# BeagleBone_Blue.net
KiCad netlist of a schematic drawn in EAGLE
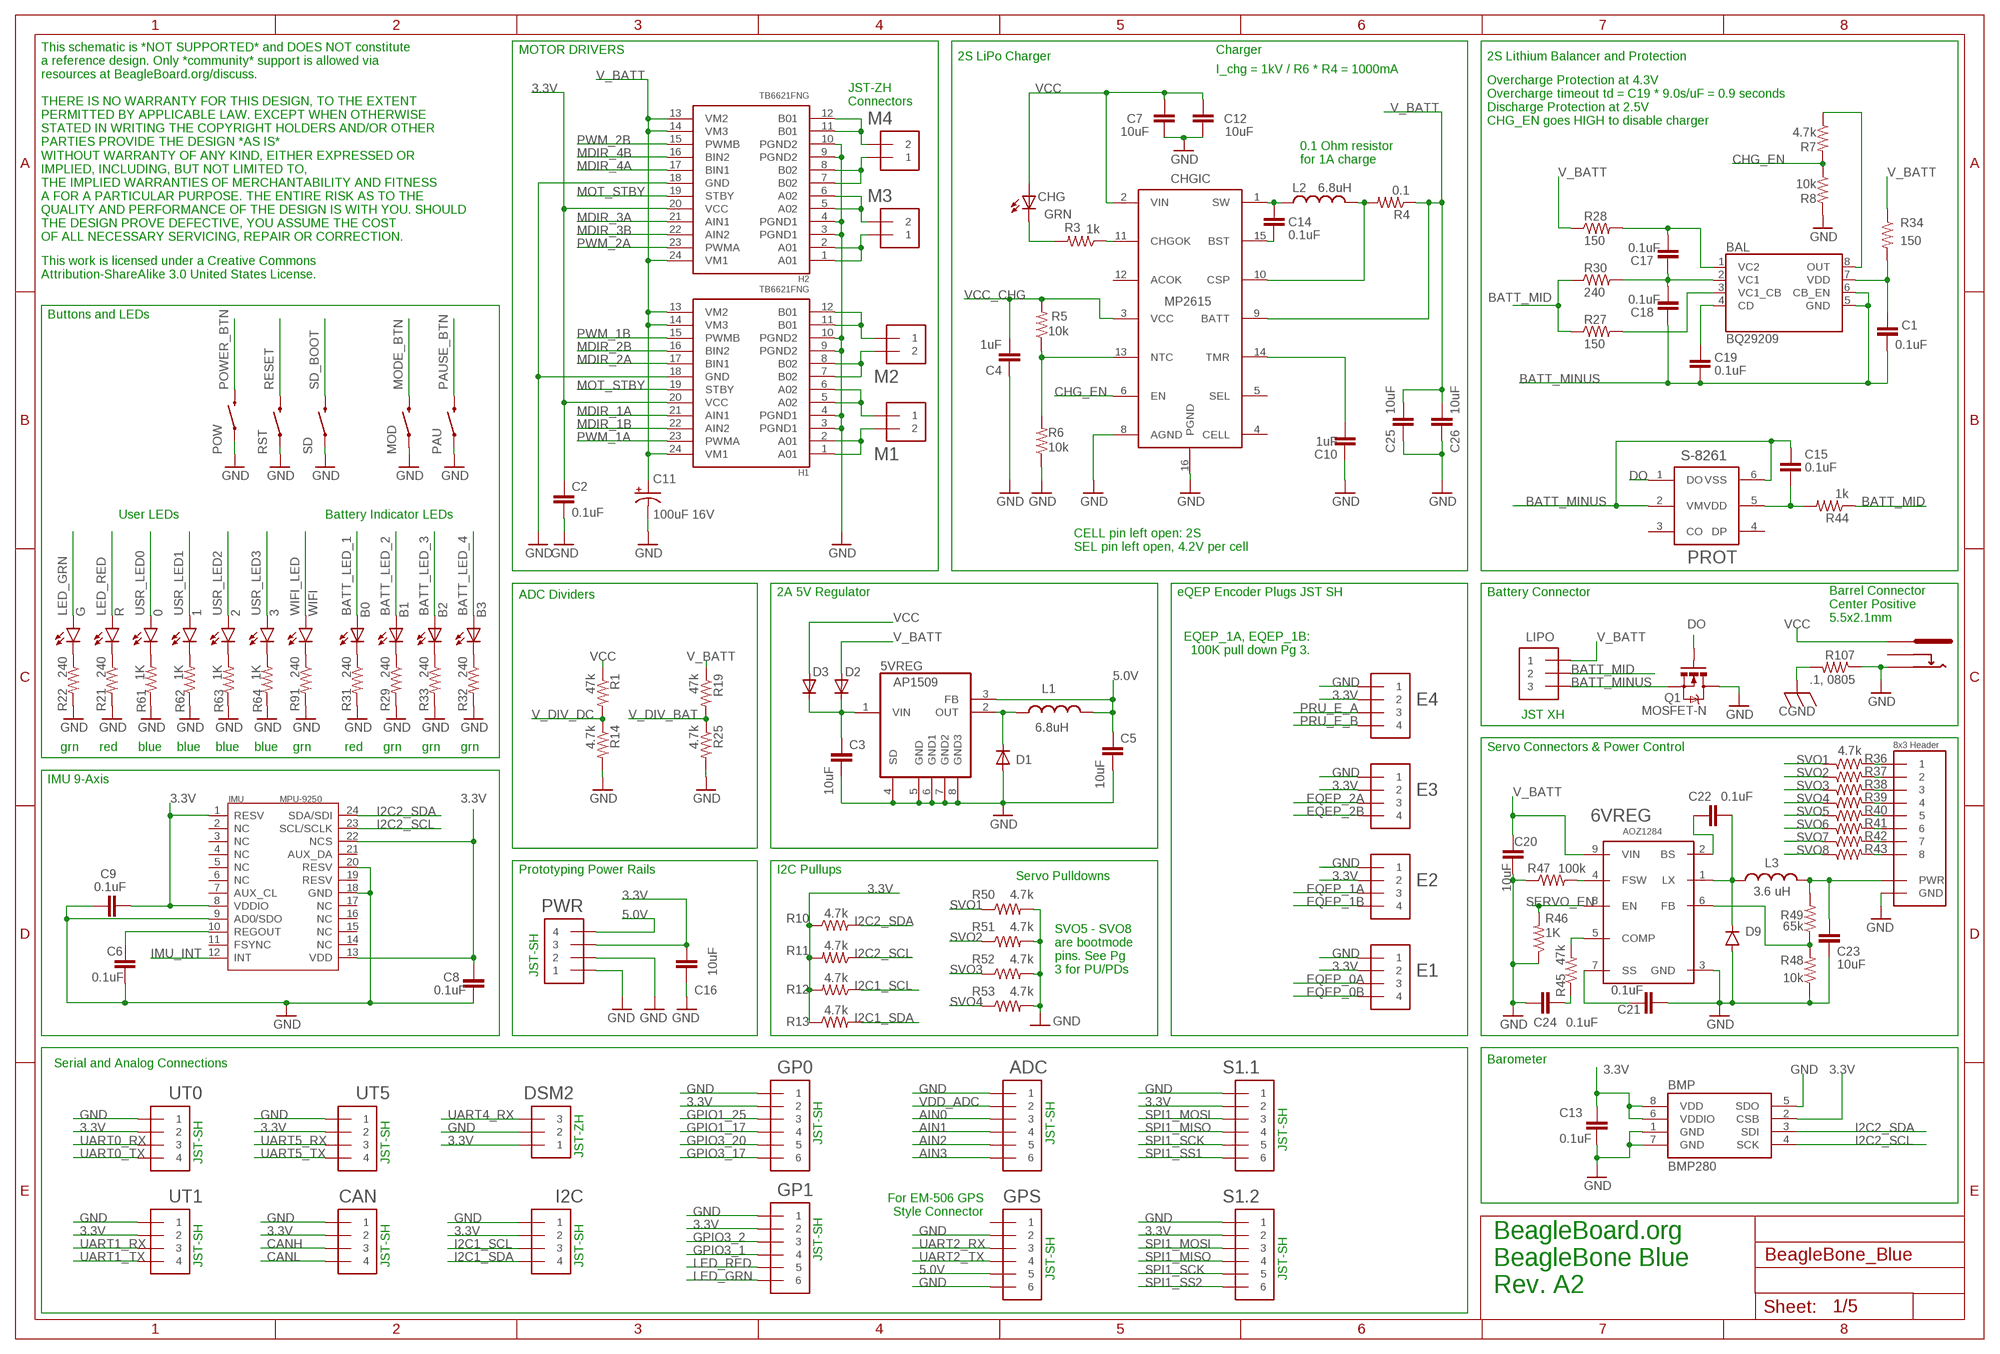
[diagram p0: schematic, sheet 1]
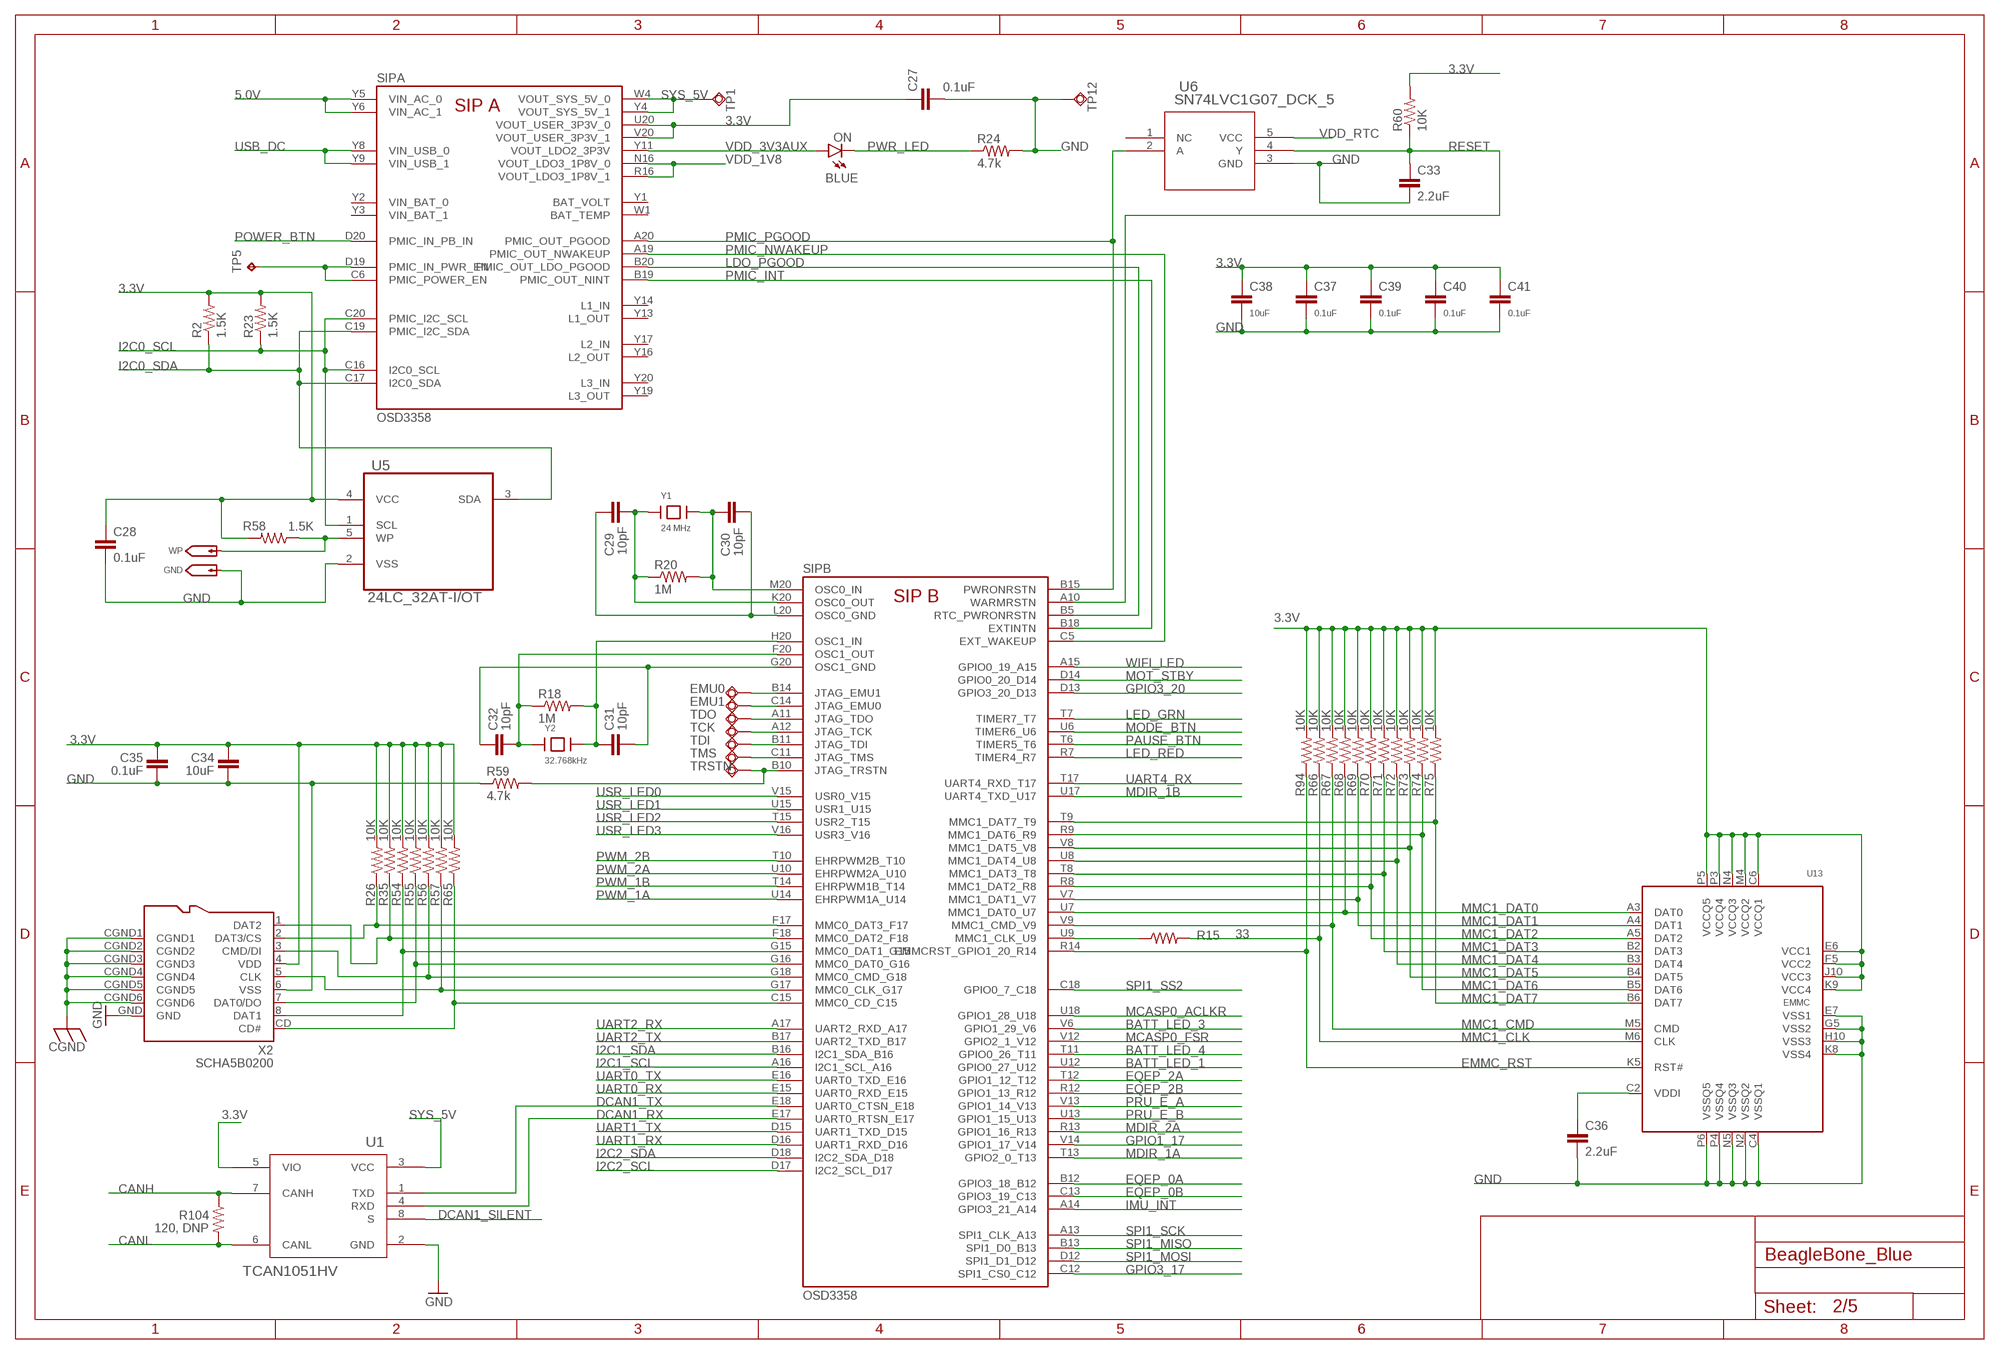
[diagram p1: schematic, sheet 2]
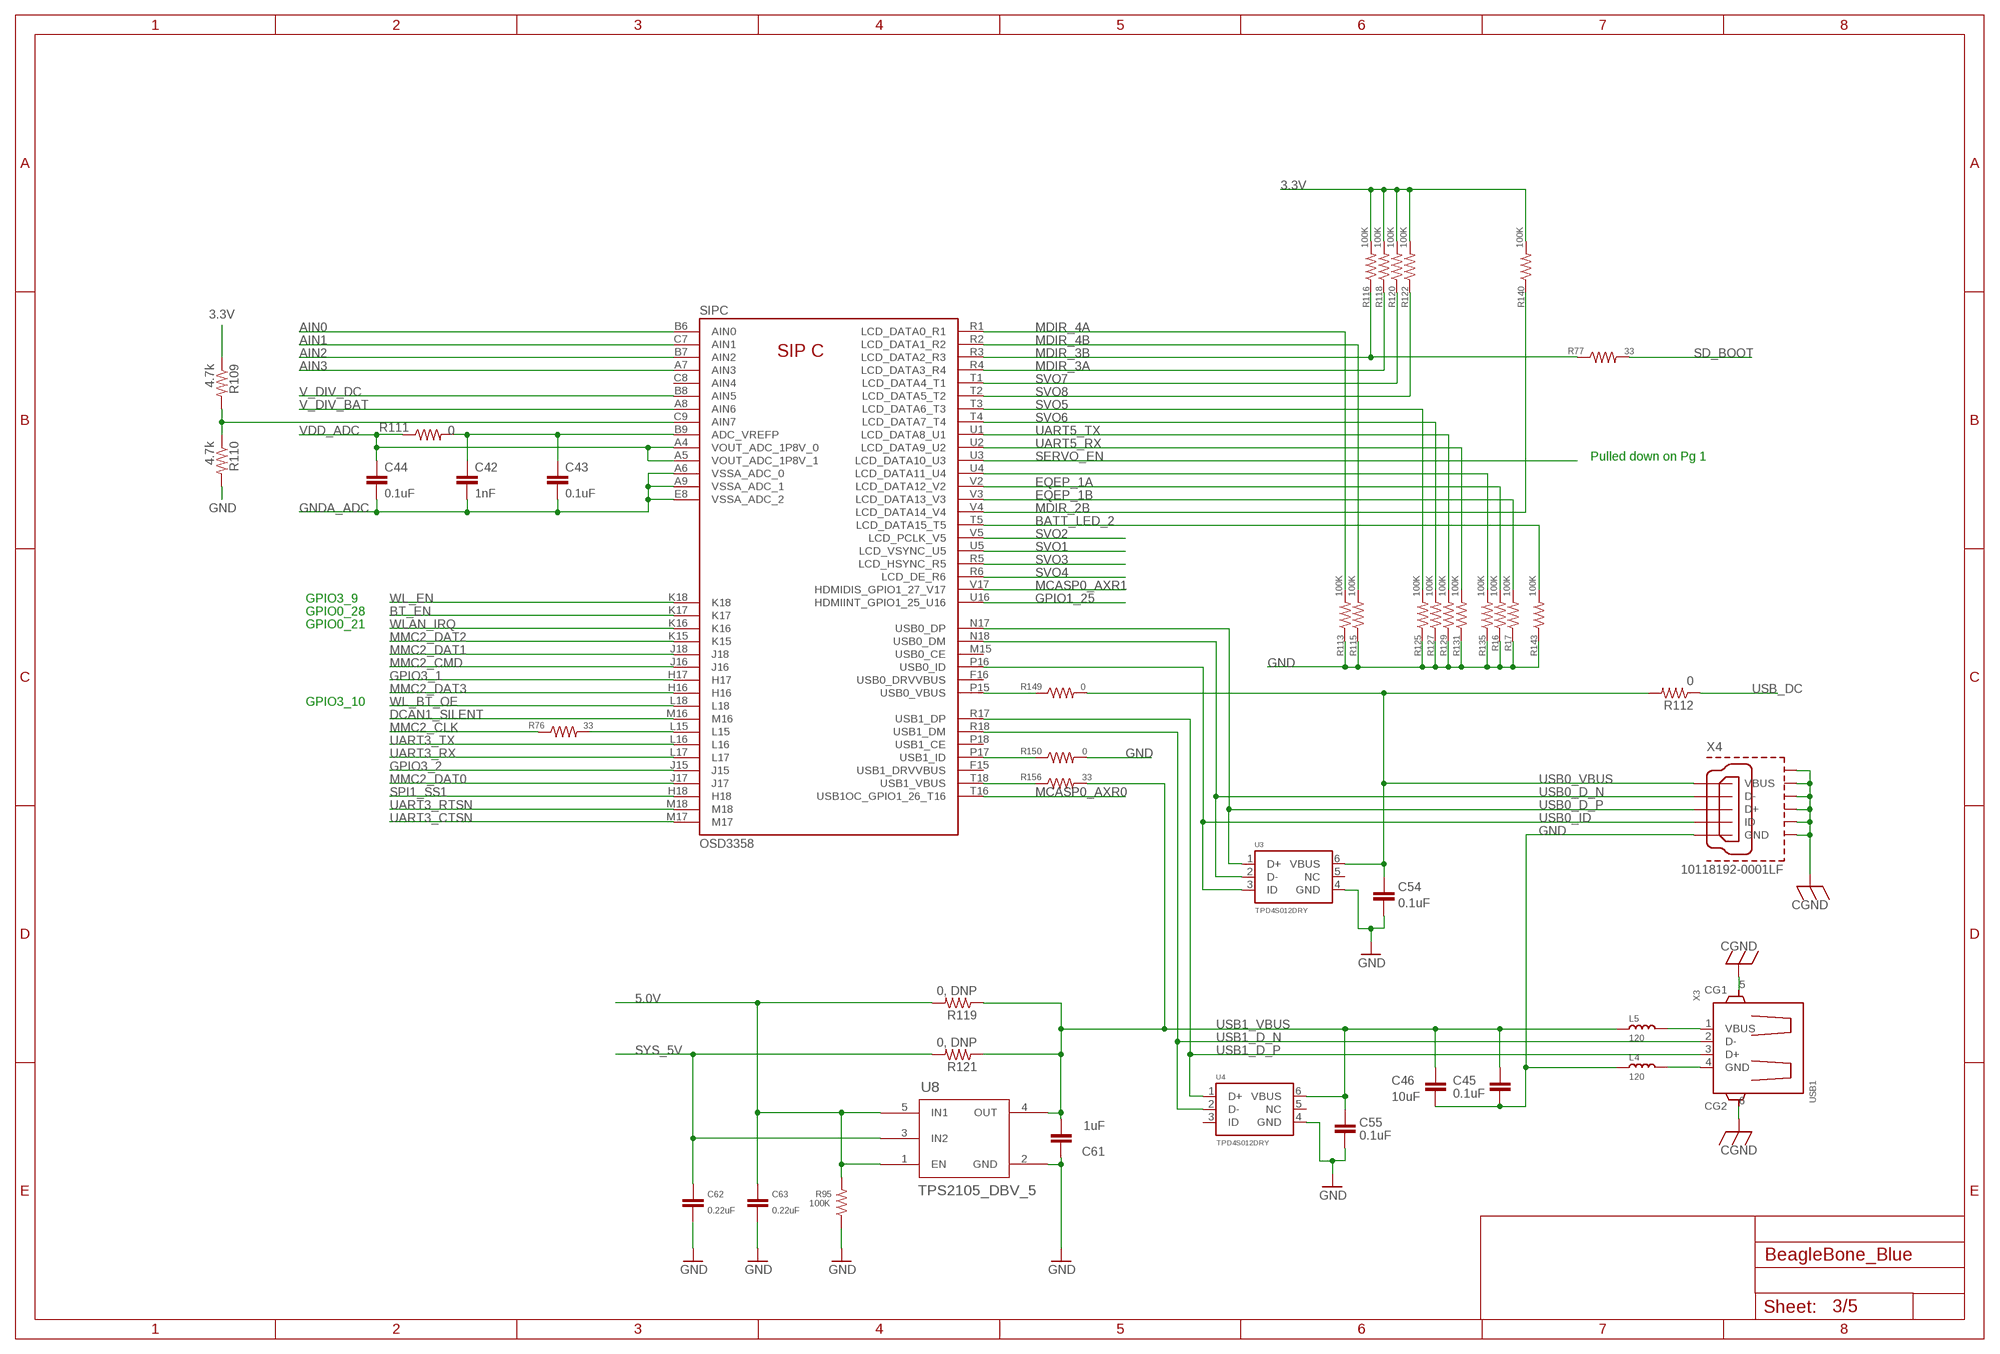
[diagram p2: schematic, sheet 3]
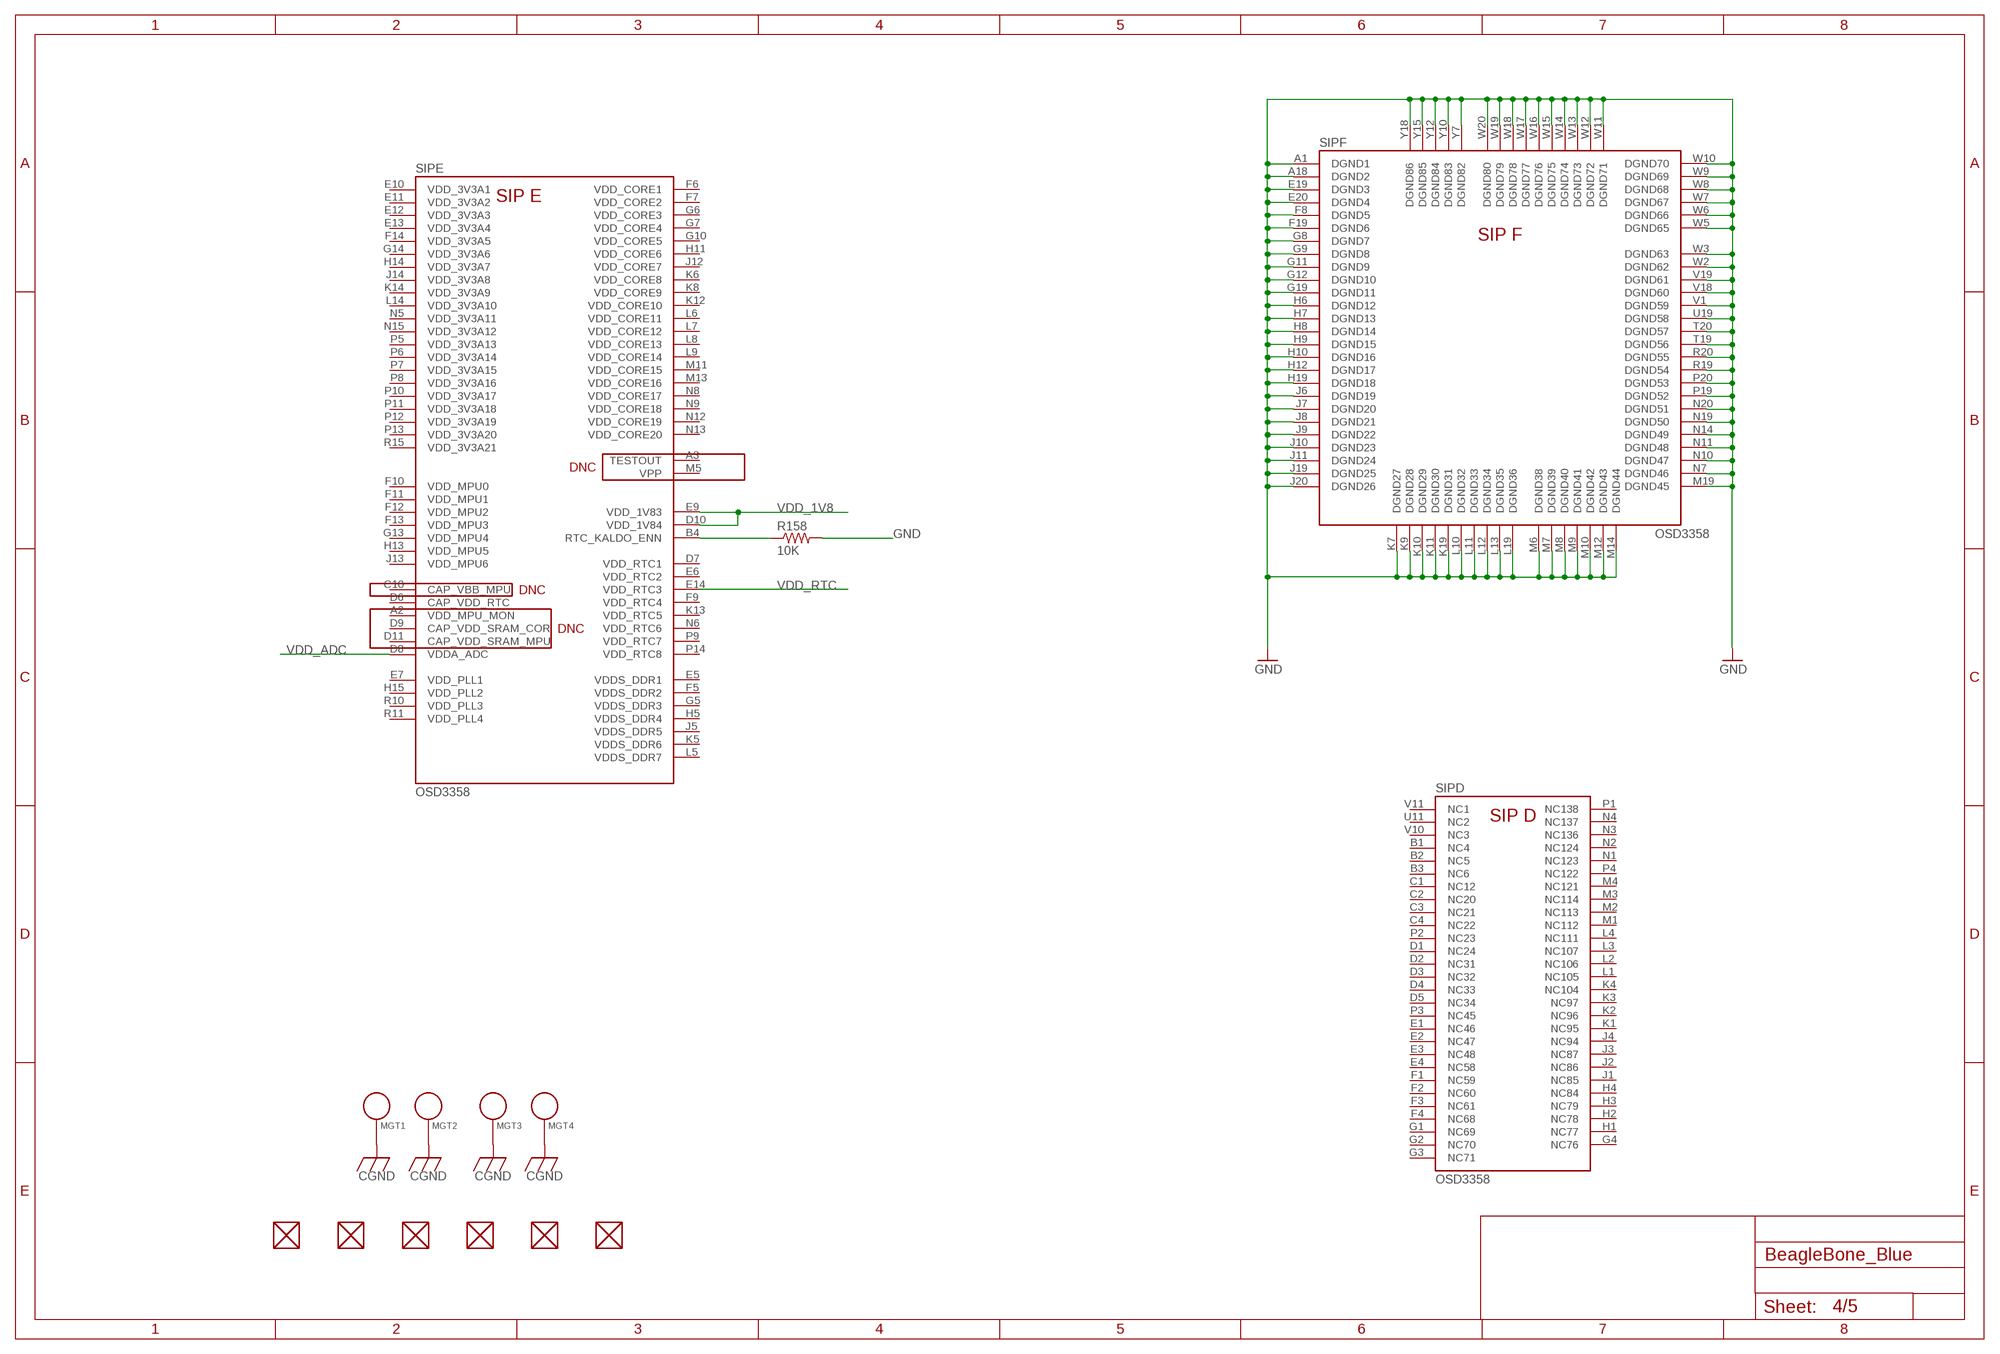
[diagram p3: schematic, sheet 4]
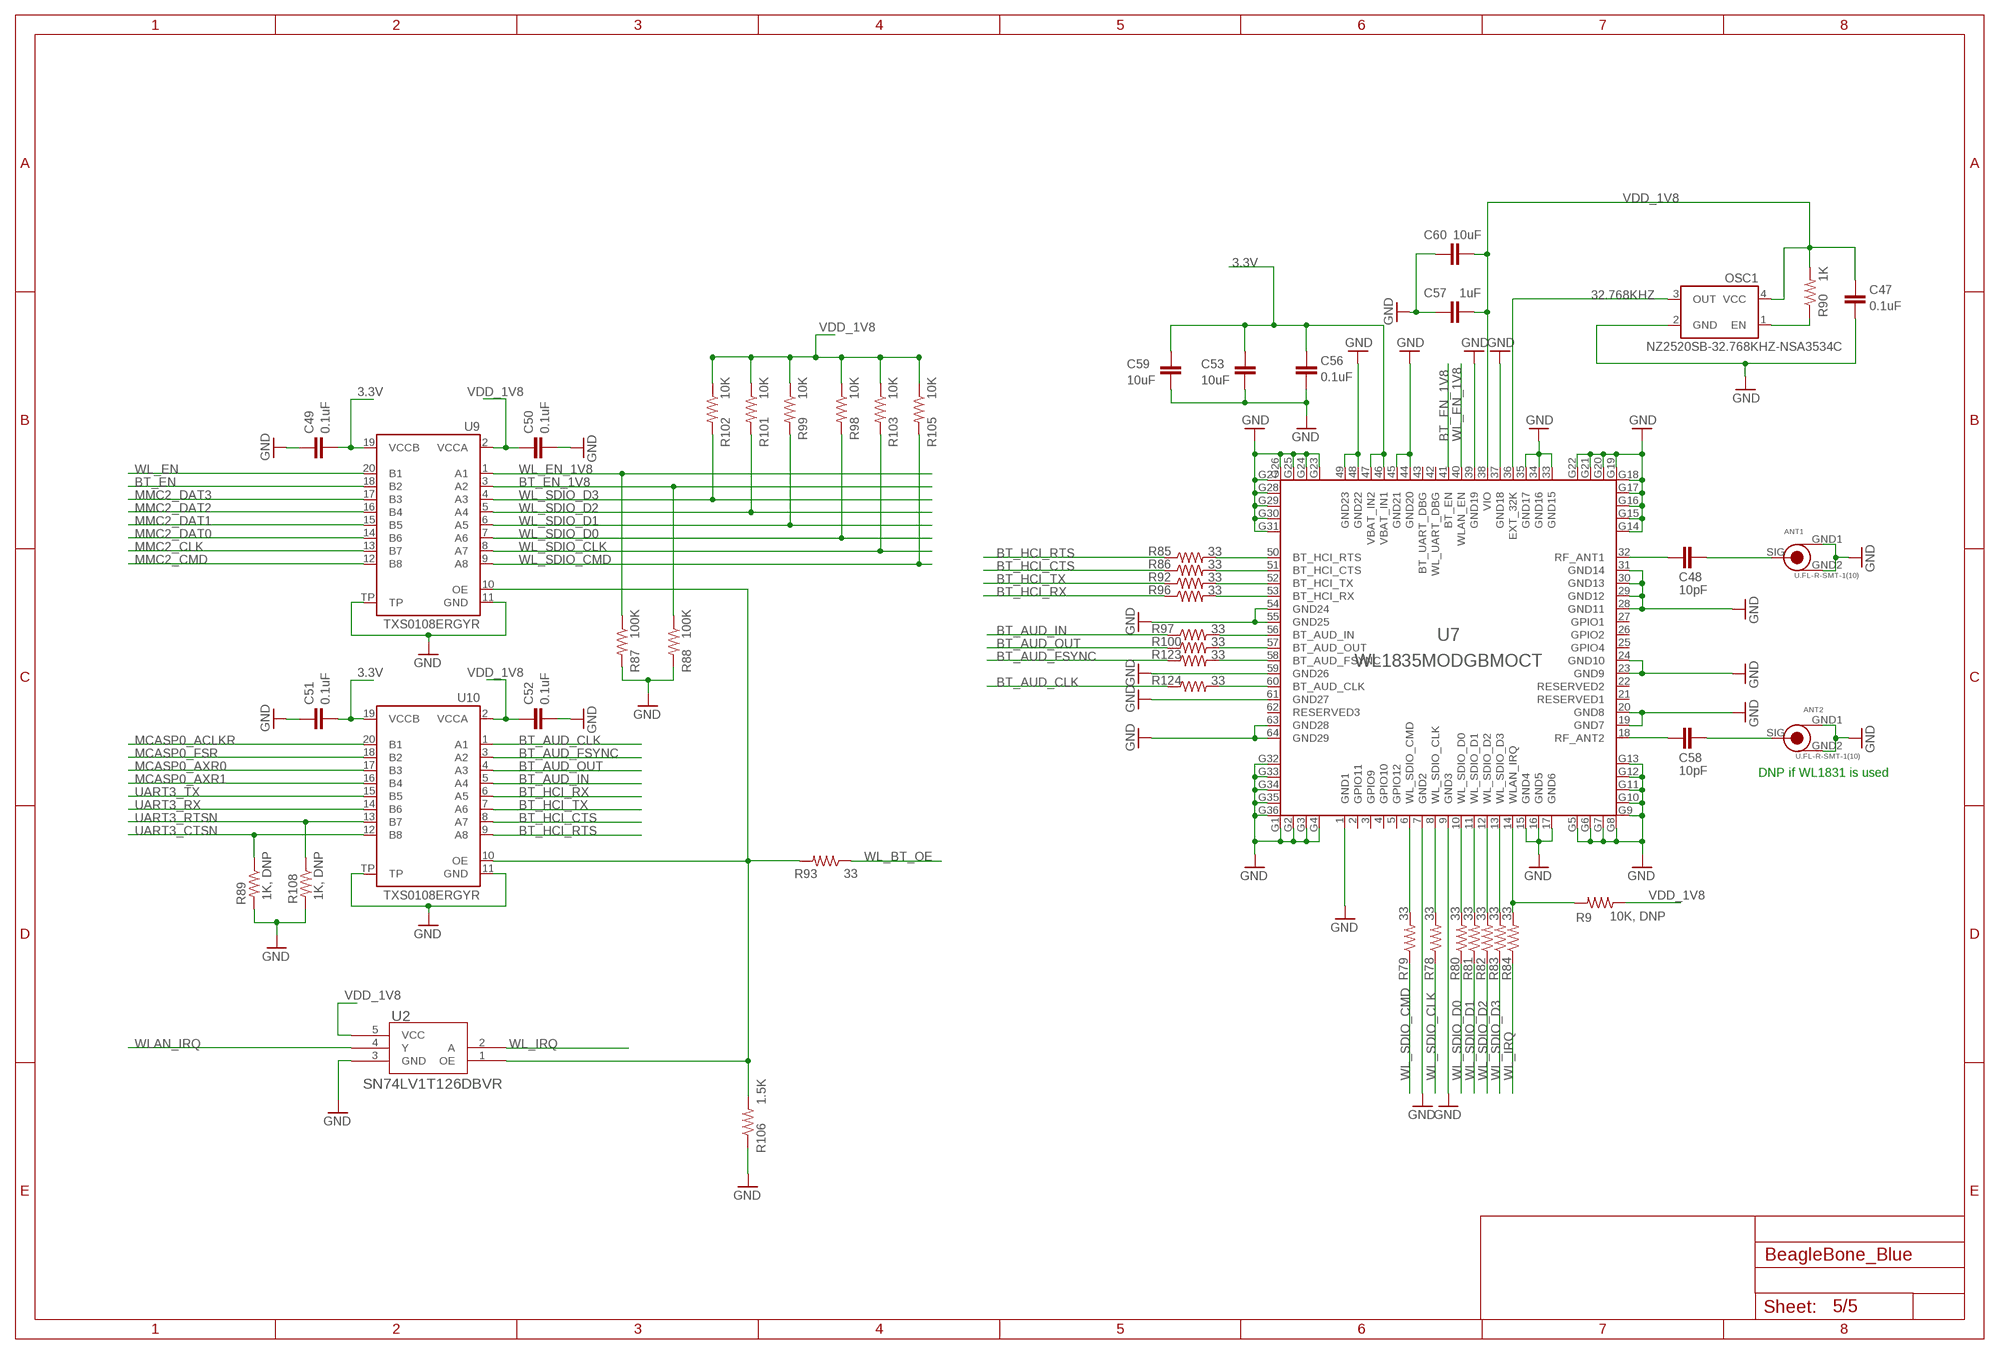
[diagram p4: schematic, sheet 5]

(export (version "E")
  (design (tool "Eeschema 10.0.6"))
  (components
    (comp (ref "0")
      (value "BLUE")
      (footprint "eagle-import:BEAGLEBONE_BLUE_LED-0603")
      (libsource (lib "eagle-import") (part "LED0603"))
    )
    (comp (ref "1")
      (value "BLUE")
      (footprint "eagle-import:BEAGLEBONE_BLUE_LED-0603")
      (libsource (lib "eagle-import") (part "LED0603"))
    )
    (comp (ref "2")
      (value "BLUE")
      (footprint "eagle-import:BEAGLEBONE_BLUE_LED-0603")
      (libsource (lib "eagle-import") (part "LED0603"))
    )
    (comp (ref "3")
      (value "BLUE")
      (footprint "eagle-import:BEAGLEBONE_BLUE_LED-0603")
      (libsource (lib "eagle-import") (part "LED0603"))
    )
    (comp (ref "5VREG")
      (value "AP1509SOIC-8-TIGHT")
      (footprint "eagle-import:BEAGLEBONE_BLUE_SO08-TIGHT")
      (libsource (lib "eagle-import") (part "AP1509SOIC-8-TIGHT"))
    )
    (comp (ref "6VREG")
      (value "AOZ1284")
      (footprint "eagle-import:SO08-EXPOSED")
      (libsource (lib "eagle-import") (part "AOZ1284"))
    )
    (comp (ref "12V")
      (value "PJ-102B_POWER_CON")
      (footprint "eagle-import:PJ-102B_POWER_CON")
      (libsource (lib "eagle-import") (part "PJ-102B_POWER_CON"))
    )
    (comp (ref "ADC")
      (value "JST_SH_6")
      (footprint "eagle-import:JST_SH_6")
      (libsource (lib "eagle-import") (part "JST_SH_6"))
    )
    (comp (ref "B0")
      (value "RED")
      (footprint "eagle-import:LED-0603")
      (libsource (lib "eagle-import") (part "SparkFun-LED_LED0603"))
    )
    (comp (ref "B1")
      (value "GREEN")
      (footprint "eagle-import:LED-0603")
      (libsource (lib "eagle-import") (part "SparkFun-LED_LED0603"))
    )
    (comp (ref "B2")
      (value "GREEN")
      (footprint "eagle-import:LED-0603")
      (libsource (lib "eagle-import") (part "SparkFun-LED_LED0603"))
    )
    (comp (ref "B3")
      (value "GREEN")
      (footprint "eagle-import:LED-0603")
      (libsource (lib "eagle-import") (part "SparkFun-LED_LED0603"))
    )
    (comp (ref "BAL")
      (value "BQ29209")
      (footprint "eagle-import:8-SON_3X3MM")
      (libsource (lib "eagle-import") (part "BQ29209"))
    )
    (comp (ref "BMP")
      (value "BMP280")
      (footprint "eagle-import:BMP280")
      (libsource (lib "eagle-import") (part "BMP280"))
    )
    (comp (ref "C1")
      (value "0.1uF")
      (footprint "eagle-import:0402-CAP")
      (libsource (lib "eagle-import") (part "Strawson_Eagle_Lib_CAP0402-CAP"))
    )
    (comp (ref "C2")
      (value "0.1uF")
      (footprint "eagle-import:0402-CAP")
      (libsource (lib "eagle-import") (part "Strawson_Eagle_Lib_CAP0402-CAP"))
    )
    (comp (ref "C3")
      (value "10uF")
      (footprint "eagle-import:0805")
      (libsource (lib "eagle-import") (part "CAP0805"))
    )
    (comp (ref "C4")
      (value "1uF")
      (footprint "eagle-import:0402-CAP")
      (libsource (lib "eagle-import") (part "Strawson_Eagle_Lib_CAP0402-CAP"))
    )
    (comp (ref "C5")
      (value "10uF")
      (footprint "eagle-import:0805")
      (libsource (lib "eagle-import") (part "CAP0805"))
    )
    (comp (ref "C6")
      (value "0.1uF")
      (footprint "eagle-import:0402-CAP")
      (libsource (lib "eagle-import") (part "Strawson_Eagle_Lib_CAP0402-CAP"))
    )
    (comp (ref "C7")
      (value "10uF")
      (footprint "eagle-import:0805")
      (libsource (lib "eagle-import") (part "CAP0805"))
    )
    (comp (ref "C8")
      (value "0.1uF")
      (footprint "eagle-import:0402-CAP")
      (libsource (lib "eagle-import") (part "Strawson_Eagle_Lib_CAP0402-CAP"))
    )
    (comp (ref "C9")
      (value "0.1uF")
      (footprint "eagle-import:0402-CAP")
      (libsource (lib "eagle-import") (part "Strawson_Eagle_Lib_CAP0402-CAP"))
    )
    (comp (ref "C10")
      (value "1uF")
      (footprint "eagle-import:0402-CAP")
      (libsource (lib "eagle-import") (part "Strawson_Eagle_Lib_CAP0402-CAP"))
    )
    (comp (ref "C11")
      (value "100uF 16V")
      (footprint "eagle-import:PANASONIC_D")
      (libsource (lib "eagle-import") (part "CPOL-USD"))
    )
    (comp (ref "C12")
      (value "10uF")
      (footprint "eagle-import:0805")
      (libsource (lib "eagle-import") (part "CAP0805"))
    )
    (comp (ref "C13")
      (value "0.1uF")
      (footprint "eagle-import:0402-CAP")
      (libsource (lib "eagle-import") (part "Strawson_Eagle_Lib_CAP0402-CAP"))
    )
    (comp (ref "C14")
      (value "0.1uF")
      (footprint "eagle-import:0402-CAP")
      (libsource (lib "eagle-import") (part "Strawson_Eagle_Lib_CAP0402-CAP"))
    )
    (comp (ref "C15")
      (value "0.1uF")
      (footprint "eagle-import:0402-CAP")
      (libsource (lib "eagle-import") (part "Strawson_Eagle_Lib_CAP0402-CAP"))
    )
    (comp (ref "C16")
      (value "10uF")
      (footprint "eagle-import:0805")
      (libsource (lib "eagle-import") (part "CAP0805"))
    )
    (comp (ref "C17")
      (value "0.1uF")
      (footprint "eagle-import:0402-CAP")
      (libsource (lib "eagle-import") (part "Strawson_Eagle_Lib_CAP0402-CAP"))
    )
    (comp (ref "C18")
      (value "0.1uF")
      (footprint "eagle-import:0402-CAP")
      (libsource (lib "eagle-import") (part "Strawson_Eagle_Lib_CAP0402-CAP"))
    )
    (comp (ref "C19")
      (value "0.1uF")
      (footprint "eagle-import:0402-CAP")
      (libsource (lib "eagle-import") (part "Strawson_Eagle_Lib_CAP0402-CAP"))
    )
    (comp (ref "C20")
      (value "10uF")
      (footprint "eagle-import:0805")
      (libsource (lib "eagle-import") (part "CAP0805"))
    )
    (comp (ref "C21")
      (value "0.1uF")
      (footprint "eagle-import:0402-CAP")
      (libsource (lib "eagle-import") (part "Strawson_Eagle_Lib_CAP0402-CAP"))
    )
    (comp (ref "C22")
      (value "0.1uF")
      (footprint "eagle-import:0402-CAP")
      (libsource (lib "eagle-import") (part "Strawson_Eagle_Lib_CAP0402-CAP"))
    )
    (comp (ref "C23")
      (value "10uF")
      (footprint "eagle-import:0805")
      (libsource (lib "eagle-import") (part "CAP0805"))
    )
    (comp (ref "C24")
      (value "0.1uF")
      (footprint "eagle-import:0402-CAP")
      (libsource (lib "eagle-import") (part "Strawson_Eagle_Lib_CAP0402-CAP"))
    )
    (comp (ref "C25")
      (value "10uF")
      (footprint "eagle-import:0805")
      (libsource (lib "eagle-import") (part "CAP0805"))
    )
    (comp (ref "C26")
      (value "10uF")
      (footprint "eagle-import:0805")
      (libsource (lib "eagle-import") (part "CAP0805"))
    )
    (comp (ref "CAN")
      (value "JST_SH_4")
      (footprint "eagle-import:JST_SH_4_SMD")
      (libsource (lib "eagle-import") (part "JST_SH_4"))
    )
    (comp (ref "CHG")
      (value "GRN")
      (footprint "eagle-import:LED-0603")
      (libsource (lib "eagle-import") (part "SparkFun-LED_LED0603"))
    )
    (comp (ref "CHGIC")
      (value "MP2615")
      (footprint "eagle-import:MP2615")
      (libsource (lib "eagle-import") (part "MP2615"))
    )
    (comp (ref "D1")
      (value "DIODE_SOD-123FL")
      (footprint "eagle-import:ADAFRUIT_SOD-123FL")
      (libsource (lib "eagle-import") (part "DIODE_SOD-123FL"))
    )
    (comp (ref "D2")
      (value "DIODE_SOD-123FL")
      (footprint "eagle-import:ADAFRUIT_SOD-123FL")
      (libsource (lib "eagle-import") (part "DIODE_SOD-123FL"))
    )
    (comp (ref "D3")
      (value "DIODE_SOD-123FL")
      (footprint "eagle-import:ADAFRUIT_SOD-123FL")
      (libsource (lib "eagle-import") (part "DIODE_SOD-123FL"))
    )
    (comp (ref "D9")
      (value "DIODEDO214AA")
      (footprint "eagle-import:DO-214AA")
      (libsource (lib "eagle-import") (part "DIODEDO214AA"))
    )
    (comp (ref "DSM2")
      (value "JST_ZH_3")
      (footprint "eagle-import:JST_ZH_3")
      (libsource (lib "eagle-import") (part "JST_ZH_3"))
    )
    (comp (ref "E1")
      (value "JST_SH_4")
      (footprint "eagle-import:JST_SH_4_SMD")
      (libsource (lib "eagle-import") (part "JST_SH_4"))
    )
    (comp (ref "E2")
      (value "JST_SH_4")
      (footprint "eagle-import:JST_SH_4_SMD")
      (libsource (lib "eagle-import") (part "JST_SH_4"))
    )
    (comp (ref "E3")
      (value "JST_SH_4")
      (footprint "eagle-import:JST_SH_4_SMD")
      (libsource (lib "eagle-import") (part "JST_SH_4"))
    )
    (comp (ref "E4")
      (value "JST_SH_4")
      (footprint "eagle-import:JST_SH_4_SMD")
      (libsource (lib "eagle-import") (part "JST_SH_4"))
    )
    (comp (ref "G")
      (value "GREEN")
      (footprint "eagle-import:BEAGLEBONE_BLUE_LED-0603")
      (libsource (lib "eagle-import") (part "LED0603"))
    )
    (comp (ref "GP0")
      (value "JST_SH_6")
      (footprint "eagle-import:JST_SH_6")
      (libsource (lib "eagle-import") (part "JST_SH_6"))
    )
    (comp (ref "GP1")
      (value "JST_SH_6")
      (footprint "eagle-import:JST_SH_6")
      (libsource (lib "eagle-import") (part "JST_SH_6"))
    )
    (comp (ref "GPS")
      (value "JST_SH_6")
      (footprint "eagle-import:JST_SH_6")
      (libsource (lib "eagle-import") (part "JST_SH_6"))
    )
    (comp (ref "H1")
      (value "TB6621FNG")
      (footprint "eagle-import:SSOP24")
      (libsource (lib "eagle-import") (part "TB6621FNG"))
    )
    (comp (ref "H2")
      (value "TB6621FNG")
      (footprint "eagle-import:SSOP24")
      (libsource (lib "eagle-import") (part "TB6621FNG"))
    )
    (comp (ref "I2C")
      (value "JST_SH_4")
      (footprint "eagle-import:JST_SH_4_SMD")
      (libsource (lib "eagle-import") (part "JST_SH_4"))
    )
    (comp (ref "IMU")
      (value "MPU-9250")
      (footprint "eagle-import:QFN24G-0.4-3X3MM")
      (libsource (lib "eagle-import") (part "MPU-9250"))
    )
    (comp (ref "J2")
      (value "STRAWSON_EAGLE_LIB_SERVO_HEADERS_8X")
      (footprint "eagle-import:STRAWSON_EAGLE_LIB_3X8_0.1__HEADER")
      (libsource (lib "eagle-import") (part "STRAWSON_EAGLE_LIB_SERVO_HEADERS_8X"))
    )
    (comp (ref "L1")
      (value "6.8uH")
      (footprint "eagle-import:SRN6045")
      (libsource (lib "eagle-import") (part "INDUCTORBOURNS_SRN6045"))
    )
    (comp (ref "L2")
      (value "6.8uH")
      (footprint "eagle-import:SRN6045")
      (libsource (lib "eagle-import") (part "INDUCTORBOURNS_SRN6045"))
    )
    (comp (ref "L3")
      (value "3.6 uH")
      (footprint "eagle-import:8X8MM_INDUCTOR")
      (libsource (lib "eagle-import") (part "INDUCTOR"))
    )
    (comp (ref "LIPO")
      (value "BATTERY")
      (footprint "eagle-import:JST_XH_3-PIN")
      (libsource (lib "eagle-import") (part "JST_XH_3-PIN"))
    )
    (comp (ref "M1")
      (value "JST_ZH_2")
      (footprint "eagle-import:JST_ZH_2")
      (libsource (lib "eagle-import") (part "JST_ZH_2"))
    )
    (comp (ref "M2")
      (value "JST_ZH_2")
      (footprint "eagle-import:JST_ZH_2")
      (libsource (lib "eagle-import") (part "JST_ZH_2"))
    )
    (comp (ref "M3")
      (value "JST_ZH_2")
      (footprint "eagle-import:JST_ZH_2")
      (libsource (lib "eagle-import") (part "JST_ZH_2"))
    )
    (comp (ref "M4")
      (value "JST_ZH_2")
      (footprint "eagle-import:JST_ZH_2")
      (libsource (lib "eagle-import") (part "JST_ZH_2"))
    )
    (comp (ref "MOD")
      (value "SWITCH-MOMENTARY-2SMD-1101NE")
      (footprint "eagle-import:TACTILE-SWITCH-1101NE")
      (libsource (lib "eagle-import") (part "SWITCH-MOMENTARY-2SMD-1101NE"))
    )
    (comp (ref "PAU")
      (value "SWITCH-MOMENTARY-2SMD-1101NE")
      (footprint "eagle-import:TACTILE-SWITCH-1101NE")
      (libsource (lib "eagle-import") (part "SWITCH-MOMENTARY-2SMD-1101NE"))
    )
    (comp (ref "POW")
      (value "SWITCH-MOMENTARY-2SMD-1101NE")
      (footprint "eagle-import:TACTILE-SWITCH-1101NE")
      (libsource (lib "eagle-import") (part "SWITCH-MOMENTARY-2SMD-1101NE"))
    )
    (comp (ref "PROT")
      (value "S-8261")
      (footprint "eagle-import:SOT-236")
      (libsource (lib "eagle-import") (part "S-8261"))
    )
    (comp (ref "PWR")
      (value "JST_SH_4")
      (footprint "eagle-import:JST_SH_4_SMD")
      (libsource (lib "eagle-import") (part "JST_SH_4"))
    )
    (comp (ref "Q1")
      (value "MOSFET-N")
      (footprint "eagle-import:SO08-TIGHT")
      (libsource (lib "eagle-import") (part "MOSFET-NCHANNEL"))
    )
    (comp (ref "R")
      (value "RED")
      (footprint "eagle-import:BEAGLEBONE_BLUE_LED-0603")
      (libsource (lib "eagle-import") (part "LED0603"))
    )
    (comp (ref "R1")
      (value "47k")
      (footprint "eagle-import:0402-RES")
      (libsource (lib "eagle-import") (part "RESISTOR0402-RES"))
    )
    (comp (ref "R3")
      (value "1k")
      (footprint "eagle-import:0402-RES")
      (libsource (lib "eagle-import") (part "RESISTOR0402-RES"))
    )
    (comp (ref "R4")
      (value "0.1")
      (footprint "eagle-import:0603-RES")
      (libsource (lib "eagle-import") (part "RESISTOR0603"))
    )
    (comp (ref "R5")
      (value "10k")
      (footprint "eagle-import:0402-RES")
      (libsource (lib "eagle-import") (part "RESISTOR0402-RES"))
    )
    (comp (ref "R6")
      (value "10k")
      (footprint "eagle-import:0402-RES")
      (libsource (lib "eagle-import") (part "RESISTOR0402-RES"))
    )
    (comp (ref "R7")
      (value "4.7k")
      (footprint "eagle-import:0402-RES")
      (libsource (lib "eagle-import") (part "RESISTOR0402-RES"))
    )
    (comp (ref "R8")
      (value "10k")
      (footprint "eagle-import:0402-RES")
      (libsource (lib "eagle-import") (part "RESISTOR0402-RES"))
    )
    (comp (ref "R10")
      (value "4.7k")
      (footprint "eagle-import:0402-RES")
      (libsource (lib "eagle-import") (part "RESISTOR0402-RES"))
    )
    (comp (ref "R11")
      (value "4.7k")
      (footprint "eagle-import:0402-RES")
      (libsource (lib "eagle-import") (part "RESISTOR0402-RES"))
    )
    (comp (ref "R12")
      (value "4.7k")
      (footprint "eagle-import:0402-RES")
      (libsource (lib "eagle-import") (part "RESISTOR0402-RES"))
    )
    (comp (ref "R13")
      (value "4.7k")
      (footprint "eagle-import:0402-RES")
      (libsource (lib "eagle-import") (part "RESISTOR0402-RES"))
    )
    (comp (ref "R14")
      (value "4.7k")
      (footprint "eagle-import:0402-RES")
      (libsource (lib "eagle-import") (part "RESISTOR0402-RES"))
    )
    (comp (ref "R19")
      (value "47k")
      (footprint "eagle-import:0402-RES")
      (libsource (lib "eagle-import") (part "RESISTOR0402-RES"))
    )
    (comp (ref "R21")
      (value "240")
      (footprint "eagle-import:0402-RES")
      (libsource (lib "eagle-import") (part "RESISTOR0402-RES"))
    )
    (comp (ref "R22")
      (value "240")
      (footprint "eagle-import:0402-RES")
      (libsource (lib "eagle-import") (part "RESISTOR0402-RES"))
    )
    (comp (ref "R25")
      (value "4.7k")
      (footprint "eagle-import:0402-RES")
      (libsource (lib "eagle-import") (part "RESISTOR0402-RES"))
    )
    (comp (ref "R27")
      (value "150")
      (footprint "eagle-import:0402-RES")
      (libsource (lib "eagle-import") (part "RESISTOR0402-RES"))
    )
    (comp (ref "R28")
      (value "150")
      (footprint "eagle-import:0402-RES")
      (libsource (lib "eagle-import") (part "RESISTOR0402-RES"))
    )
    (comp (ref "R29")
      (value "240")
      (footprint "eagle-import:0402-RES")
      (libsource (lib "eagle-import") (part "RESISTOR0402-RES"))
    )
    (comp (ref "R30")
      (value "240")
      (footprint "eagle-import:0402-RES")
      (libsource (lib "eagle-import") (part "RESISTOR0402-RES"))
    )
    (comp (ref "R31")
      (value "240")
      (footprint "eagle-import:0402-RES")
      (libsource (lib "eagle-import") (part "RESISTOR0402-RES"))
    )
    (comp (ref "R32")
      (value "240")
      (footprint "eagle-import:0402-RES")
      (libsource (lib "eagle-import") (part "RESISTOR0402-RES"))
    )
    (comp (ref "R33")
      (value "240")
      (footprint "eagle-import:0402-RES")
      (libsource (lib "eagle-import") (part "RESISTOR0402-RES"))
    )
    (comp (ref "R34")
      (value "150")
      (footprint "eagle-import:0402-RES")
      (libsource (lib "eagle-import") (part "RESISTOR0402-RES"))
    )
    (comp (ref "R36")
      (value "4.7k")
      (footprint "eagle-import:0402-RES")
      (libsource (lib "eagle-import") (part "RESISTOR0402-RES"))
    )
    (comp (ref "R37")
      (value "4.7k")
      (footprint "eagle-import:0402-RES")
      (libsource (lib "eagle-import") (part "RESISTOR0402-RES"))
    )
    (comp (ref "R38")
      (value "4.7k")
      (footprint "eagle-import:0402-RES")
      (libsource (lib "eagle-import") (part "RESISTOR0402-RES"))
    )
    (comp (ref "R39")
      (value "4.7k")
      (footprint "eagle-import:0402-RES")
      (libsource (lib "eagle-import") (part "RESISTOR0402-RES"))
    )
    (comp (ref "R40")
      (value "4.7k")
      (footprint "eagle-import:0402-RES")
      (libsource (lib "eagle-import") (part "RESISTOR0402-RES"))
    )
    (comp (ref "R41")
      (value "4.7k")
      (footprint "eagle-import:0402-RES")
      (libsource (lib "eagle-import") (part "RESISTOR0402-RES"))
    )
    (comp (ref "R42")
      (value "4.7k")
      (footprint "eagle-import:0402-RES")
      (libsource (lib "eagle-import") (part "RESISTOR0402-RES"))
    )
    (comp (ref "R43")
      (value "4.7k")
      (footprint "eagle-import:0402-RES")
      (libsource (lib "eagle-import") (part "RESISTOR0402-RES"))
    )
    (comp (ref "R44")
      (value "1k")
      (footprint "eagle-import:0402-RES")
      (libsource (lib "eagle-import") (part "RESISTOR0402-RES"))
    )
    (comp (ref "R45")
      (value "47k")
      (footprint "eagle-import:0402-RES")
      (libsource (lib "eagle-import") (part "RESISTOR0402-RES"))
    )
    (comp (ref "R46")
      (value "1K")
      (footprint "eagle-import:0402-RES")
      (libsource (lib "eagle-import") (part "RESISTOR0402-RES"))
    )
    (comp (ref "R47")
      (value "100k")
      (footprint "eagle-import:0402-RES")
      (libsource (lib "eagle-import") (part "RESISTOR0402-RES"))
    )
    (comp (ref "R48")
      (value "10k")
      (footprint "eagle-import:0402-RES")
      (libsource (lib "eagle-import") (part "RESISTOR0402-RES"))
    )
    (comp (ref "R49")
      (value "65k")
      (footprint "eagle-import:0402-RES")
      (libsource (lib "eagle-import") (part "RESISTOR0402-RES"))
    )
    (comp (ref "R50")
      (value "4.7k")
      (footprint "eagle-import:0402-RES")
      (libsource (lib "eagle-import") (part "RESISTOR0402-RES"))
    )
    (comp (ref "R51")
      (value "4.7k")
      (footprint "eagle-import:0402-RES")
      (libsource (lib "eagle-import") (part "RESISTOR0402-RES"))
    )
    (comp (ref "R52")
      (value "4.7k")
      (footprint "eagle-import:0402-RES")
      (libsource (lib "eagle-import") (part "RESISTOR0402-RES"))
    )
    (comp (ref "R53")
      (value "4.7k")
      (footprint "eagle-import:0402-RES")
      (libsource (lib "eagle-import") (part "RESISTOR0402-RES"))
    )
    (comp (ref "R61")
      (value "1K")
      (footprint "eagle-import:0402-RES")
      (libsource (lib "eagle-import") (part "RESISTOR0402-RES"))
    )
    (comp (ref "R62")
      (value "1K")
      (footprint "eagle-import:0402-RES")
      (libsource (lib "eagle-import") (part "RESISTOR0402-RES"))
    )
    (comp (ref "R63")
      (value "1K")
      (footprint "eagle-import:0402-RES")
      (libsource (lib "eagle-import") (part "RESISTOR0402-RES"))
    )
    (comp (ref "R64")
      (value "1K")
      (footprint "eagle-import:0402-RES")
      (libsource (lib "eagle-import") (part "RESISTOR0402-RES"))
    )
    (comp (ref "R91")
      (value "240")
      (footprint "eagle-import:0402-RES")
      (libsource (lib "eagle-import") (part "RESISTOR0402-RES"))
    )
    (comp (ref "R107")
      (value ".1, 0805")
      (footprint "eagle-import:R0805")
      (libsource (lib "eagle-import") (part "R-US_R0805"))
    )
    (comp (ref "RST")
      (value "SWITCH-MOMENTARY-2SMD-1101NE")
      (footprint "eagle-import:TACTILE-SWITCH-1101NE")
      (libsource (lib "eagle-import") (part "SWITCH-MOMENTARY-2SMD-1101NE"))
    )
    (comp (ref "S1.1")
      (value "JST_SH_6")
      (footprint "eagle-import:JST_SH_6")
      (libsource (lib "eagle-import") (part "JST_SH_6"))
    )
    (comp (ref "S1.2")
      (value "JST_SH_6")
      (footprint "eagle-import:JST_SH_6")
      (libsource (lib "eagle-import") (part "JST_SH_6"))
    )
    (comp (ref "SD")
      (value "SWITCH-MOMENTARY-2SMD-1101NE")
      (footprint "eagle-import:TACTILE-SWITCH-1101NE")
      (libsource (lib "eagle-import") (part "SWITCH-MOMENTARY-2SMD-1101NE"))
    )
    (comp (ref "UT0")
      (value "JST_SH_4")
      (footprint "eagle-import:JST_SH_4_SMD")
      (libsource (lib "eagle-import") (part "JST_SH_4"))
    )
    (comp (ref "UT1")
      (value "JST_SH_4")
      (footprint "eagle-import:JST_SH_4_SMD")
      (libsource (lib "eagle-import") (part "JST_SH_4"))
    )
    (comp (ref "UT5")
      (value "JST_SH_4")
      (footprint "eagle-import:JST_SH_4_SMD")
      (libsource (lib "eagle-import") (part "JST_SH_4"))
    )
    (comp (ref "WIFI")
      (value "GREEN")
      (footprint "eagle-import:BEAGLEBONE_BLUE_LED-0603")
      (libsource (lib "eagle-import") (part "LED0603"))
    )
    (comp (ref "FUD1")
      (value "FIDUCIAL")
      (footprint "eagle-import:FIDUCIAL_40MIL")
      (libsource (lib "eagle-import") (part "FIDUCIAL"))
    )
    (comp (ref "FUD2")
      (value "FIDUCIAL")
      (footprint "eagle-import:FIDUCIAL_40MIL")
      (libsource (lib "eagle-import") (part "FIDUCIAL"))
    )
    (comp (ref "FUD3")
      (value "FIDUCIAL")
      (footprint "eagle-import:FIDUCIAL_40MIL")
      (libsource (lib "eagle-import") (part "FIDUCIAL"))
    )
    (comp (ref "FUD4")
      (value "FIDUCIAL")
      (footprint "eagle-import:FIDUCIAL_40MIL")
      (libsource (lib "eagle-import") (part "FIDUCIAL"))
    )
    (comp (ref "FUD5")
      (value "FIDUCIAL")
      (footprint "eagle-import:FIDUCIAL_40MIL")
      (libsource (lib "eagle-import") (part "FIDUCIAL"))
    )
    (comp (ref "FUD6")
      (value "FIDUCIAL")
      (footprint "eagle-import:FIDUCIAL_40MIL")
      (libsource (lib "eagle-import") (part "FIDUCIAL"))
    )
    (comp (ref "MGT1")
      (value "MOUNTING_HOLE")
      (footprint "eagle-import:MOUNTING_HOLE")
      (libsource (lib "eagle-import") (part "MOUNTING_HOLE"))
    )
    (comp (ref "MGT2")
      (value "MOUNTING_HOLE")
      (footprint "eagle-import:MOUNTING_HOLE")
      (libsource (lib "eagle-import") (part "MOUNTING_HOLE"))
    )
    (comp (ref "MGT3")
      (value "MOUNTING_HOLE")
      (footprint "eagle-import:MOUNTING_HOLE")
      (libsource (lib "eagle-import") (part "MOUNTING_HOLE"))
    )
    (comp (ref "MGT4")
      (value "MOUNTING_HOLE")
      (footprint "eagle-import:MOUNTING_HOLE")
      (libsource (lib "eagle-import") (part "MOUNTING_HOLE"))
    )
    (comp (ref "R158")
      (value "10K")
      (footprint "eagle-import:0402-RES")
      (libsource (lib "eagle-import") (part "RESISTOR0402-RES"))
    )
    (comp (ref "SIP")
      (value "OSD3358")
      (footprint "eagle-import:BEAGLEBONE_BLUE_OSD3358")
      (libsource (lib "eagle-import") (part "OSD3358"))
    )
    (comp (ref "C27")
      (value "0.1uF")
      (footprint "eagle-import:0402-CAP")
      (libsource (lib "eagle-import") (part "Strawson_Eagle_Lib_CAP0402-CAP"))
    )
    (comp (ref "C28")
      (value "0.1uF")
      (footprint "eagle-import:0402-CAP")
      (libsource (lib "eagle-import") (part "Strawson_Eagle_Lib_CAP0402-CAP"))
    )
    (comp (ref "C29")
      (value "10pF")
      (footprint "eagle-import:0402-CAP")
      (libsource (lib "eagle-import") (part "Strawson_Eagle_Lib_CAP0402-CAP"))
    )
    (comp (ref "C30")
      (value "10pF")
      (footprint "eagle-import:0402-CAP")
      (libsource (lib "eagle-import") (part "Strawson_Eagle_Lib_CAP0402-CAP"))
    )
    (comp (ref "C31")
      (value "10pF")
      (footprint "eagle-import:0402-CAP")
      (libsource (lib "eagle-import") (part "Strawson_Eagle_Lib_CAP0402-CAP"))
    )
    (comp (ref "C32")
      (value "10pF")
      (footprint "eagle-import:0402-CAP")
      (libsource (lib "eagle-import") (part "Strawson_Eagle_Lib_CAP0402-CAP"))
    )
    (comp (ref "C33")
      (value "2.2uF")
      (footprint "eagle-import:0402-CAP")
      (libsource (lib "eagle-import") (part "Strawson_Eagle_Lib_CAP0402-CAP"))
    )
    (comp (ref "C34")
      (value "10uF")
      (footprint "eagle-import:0805")
      (libsource (lib "eagle-import") (part "Strawson_Eagle_Lib_CAP0805"))
    )
    (comp (ref "C35")
      (value "0.1uF")
      (footprint "eagle-import:0402-CAP")
      (libsource (lib "eagle-import") (part "Strawson_Eagle_Lib_CAP0402-CAP"))
    )
    (comp (ref "C36")
      (value "2.2uF")
      (footprint "eagle-import:0402-CAP")
      (libsource (lib "eagle-import") (part "Strawson_Eagle_Lib_CAP0402-CAP"))
    )
    (comp (ref "C37")
      (value "0.1uF")
      (footprint "eagle-import:0402-CAP")
      (libsource (lib "eagle-import") (part "Strawson_Eagle_Lib_CAP0402-CAP"))
    )
    (comp (ref "C38")
      (value "10uF")
      (footprint "eagle-import:0805")
      (libsource (lib "eagle-import") (part "Strawson_Eagle_Lib_CAP0805"))
    )
    (comp (ref "C39")
      (value "0.1uF")
      (footprint "eagle-import:0402-CAP")
      (libsource (lib "eagle-import") (part "Strawson_Eagle_Lib_CAP0402-CAP"))
    )
    (comp (ref "C40")
      (value "0.1uF")
      (footprint "eagle-import:0402-CAP")
      (libsource (lib "eagle-import") (part "Strawson_Eagle_Lib_CAP0402-CAP"))
    )
    (comp (ref "C41")
      (value "0.1uF")
      (footprint "eagle-import:0402-CAP")
      (libsource (lib "eagle-import") (part "Strawson_Eagle_Lib_CAP0402-CAP"))
    )
    (comp (ref "EMU0")
      (value "TPSQB1,27")
      (footprint "eagle-import:B1,27")
      (libsource (lib "eagle-import") (part "TPSQB1,27"))
    )
    (comp (ref "EMU1")
      (value "TPSQB1,27")
      (footprint "eagle-import:B1,27")
      (libsource (lib "eagle-import") (part "TPSQB1,27"))
    )
    (comp (ref "GND")
      (value "GHI2_TESTPAD/W_HOLE_1X1")
      (footprint "eagle-import:GHI2_TESTPAD_W_HOLE_1X1")
      (libsource (lib "eagle-import") (part "GHI2_TESTPAD/W_HOLE_1X1"))
    )
    (comp (ref "ON")
      (value "BLUE")
      (footprint "eagle-import:BEAGLEBONE_BLUE_LED-0603")
      (libsource (lib "eagle-import") (part "LED0603"))
    )
    (comp (ref "R2")
      (value "1.5K")
      (footprint "eagle-import:0402-RES")
      (libsource (lib "eagle-import") (part "RESISTOR0402-RES"))
    )
    (comp (ref "R15")
      (value "33")
      (footprint "eagle-import:0402-RES")
      (libsource (lib "eagle-import") (part "RESISTOR0402-RES"))
    )
    (comp (ref "R18")
      (value "1M")
      (footprint "eagle-import:0402-RES")
      (libsource (lib "eagle-import") (part "RESISTOR0402-RES"))
    )
    (comp (ref "R20")
      (value "1M")
      (footprint "eagle-import:0402-RES")
      (libsource (lib "eagle-import") (part "RESISTOR0402-RES"))
    )
    (comp (ref "R23")
      (value "1.5K")
      (footprint "eagle-import:0402-RES")
      (libsource (lib "eagle-import") (part "RESISTOR0402-RES"))
    )
    (comp (ref "R24")
      (value "4.7k")
      (footprint "eagle-import:0402-RES")
      (libsource (lib "eagle-import") (part "RESISTOR0402-RES"))
    )
    (comp (ref "R26")
      (value "10K")
      (footprint "eagle-import:0402-RES")
      (libsource (lib "eagle-import") (part "RESISTOR0402-RES"))
    )
    (comp (ref "R35")
      (value "10K")
      (footprint "eagle-import:0402-RES")
      (libsource (lib "eagle-import") (part "RESISTOR0402-RES"))
    )
    (comp (ref "R54")
      (value "10K")
      (footprint "eagle-import:0402-RES")
      (libsource (lib "eagle-import") (part "RESISTOR0402-RES"))
    )
    (comp (ref "R55")
      (value "10K")
      (footprint "eagle-import:0402-RES")
      (libsource (lib "eagle-import") (part "RESISTOR0402-RES"))
    )
    (comp (ref "R56")
      (value "10K")
      (footprint "eagle-import:0402-RES")
      (libsource (lib "eagle-import") (part "RESISTOR0402-RES"))
    )
    (comp (ref "R57")
      (value "10K")
      (footprint "eagle-import:0402-RES")
      (libsource (lib "eagle-import") (part "RESISTOR0402-RES"))
    )
    (comp (ref "R58")
      (value "1.5K")
      (footprint "eagle-import:0402-RES")
      (libsource (lib "eagle-import") (part "RESISTOR0402-RES"))
    )
    (comp (ref "R59")
      (value "4.7k")
      (footprint "eagle-import:0402-RES")
      (libsource (lib "eagle-import") (part "RESISTOR0402-RES"))
    )
    (comp (ref "R60")
      (value "10K")
      (footprint "eagle-import:0402-RES")
      (libsource (lib "eagle-import") (part "RESISTOR0402-RES"))
    )
    (comp (ref "R65")
      (value "10K")
      (footprint "eagle-import:0402-RES")
      (libsource (lib "eagle-import") (part "RESISTOR0402-RES"))
    )
    (comp (ref "R66")
      (value "10K")
      (footprint "eagle-import:0402-RES")
      (libsource (lib "eagle-import") (part "RESISTOR0402-RES"))
    )
    (comp (ref "R67")
      (value "10K")
      (footprint "eagle-import:0402-RES")
      (libsource (lib "eagle-import") (part "RESISTOR0402-RES"))
    )
    (comp (ref "R68")
      (value "10K")
      (footprint "eagle-import:0402-RES")
      (libsource (lib "eagle-import") (part "RESISTOR0402-RES"))
    )
    (comp (ref "R69")
      (value "10K")
      (footprint "eagle-import:0402-RES")
      (libsource (lib "eagle-import") (part "RESISTOR0402-RES"))
    )
    (comp (ref "R70")
      (value "10K")
      (footprint "eagle-import:0402-RES")
      (libsource (lib "eagle-import") (part "RESISTOR0402-RES"))
    )
    (comp (ref "R71")
      (value "10K")
      (footprint "eagle-import:0402-RES")
      (libsource (lib "eagle-import") (part "RESISTOR0402-RES"))
    )
    (comp (ref "R72")
      (value "10K")
      (footprint "eagle-import:0402-RES")
      (libsource (lib "eagle-import") (part "RESISTOR0402-RES"))
    )
    (comp (ref "R73")
      (value "10K")
      (footprint "eagle-import:0402-RES")
      (libsource (lib "eagle-import") (part "RESISTOR0402-RES"))
    )
    (comp (ref "R74")
      (value "10K")
      (footprint "eagle-import:0402-RES")
      (libsource (lib "eagle-import") (part "RESISTOR0402-RES"))
    )
    (comp (ref "R75")
      (value "10K")
      (footprint "eagle-import:0402-RES")
      (libsource (lib "eagle-import") (part "RESISTOR0402-RES"))
    )
    (comp (ref "R94")
      (value "10K")
      (footprint "eagle-import:0402-RES")
      (libsource (lib "eagle-import") (part "RESISTOR0402-RES"))
    )
    (comp (ref "R104")
      (value "120, DNP")
      (footprint "eagle-import:0603-RES")
      (libsource (lib "eagle-import") (part "RESISTOR0603"))
    )
    (comp (ref "TCK")
      (value "TPSQB1,27")
      (footprint "eagle-import:B1,27")
      (libsource (lib "eagle-import") (part "TPSQB1,27"))
    )
    (comp (ref "TDI")
      (value "TPSQB1,27")
      (footprint "eagle-import:B1,27")
      (libsource (lib "eagle-import") (part "TPSQB1,27"))
    )
    (comp (ref "TDO")
      (value "TPSQB1,27")
      (footprint "eagle-import:B1,27")
      (libsource (lib "eagle-import") (part "TPSQB1,27"))
    )
    (comp (ref "TMS")
      (value "TPSQB1,27")
      (footprint "eagle-import:B1,27")
      (libsource (lib "eagle-import") (part "TPSQB1,27"))
    )
    (comp (ref "TP1")
      (value "TPSQB1,27")
      (footprint "eagle-import:B1,27")
      (libsource (lib "eagle-import") (part "TPSQB1,27"))
    )
    (comp (ref "TP5")
      (value "TPB0,65")
      (footprint "eagle-import:BEAGLEBONE_BLUE_B0,65")
      (libsource (lib "eagle-import") (part "TPB0,65"))
    )
    (comp (ref "TP12")
      (value "TPSQB1,27")
      (footprint "eagle-import:B1,27")
      (libsource (lib "eagle-import") (part "TPSQB1,27"))
    )
    (comp (ref "TRSTN")
      (value "TPSQB1,27")
      (footprint "eagle-import:B1,27")
      (libsource (lib "eagle-import") (part "TPSQB1,27"))
    )
    (comp (ref "U1")
      (value "TCAN1051HV")
      (footprint "eagle-import:BEAGLEBONE_BLUE_D8")
      (fields
        (field (name "MANUFACTURER") "Texas Instruments")
        (field (name "MANUFACTURER_PART_NUMBER") "TCAN1051HVD")
      )
      (libsource (lib "eagle-import") (part "TCAN1051HV"))
    )
    (comp (ref "U5")
      (value "24LC_32AT-I/OT")
      (footprint "eagle-import:SOT95P290X145-5N")
      (fields (field (name "MPN") "24LC32AT-I/OT"))
      (libsource (lib "eagle-import") (part "24LC_32AT-I/OT"))
    )
    (comp (ref "U6")
      (value "SN74LVC1G07_DCK_5")
      (footprint "eagle-import:BEAGLEBONE_BLUE_DCK5")
      (fields
        (field (name "GENERIC_PART_NUMBER") "SN74LVC1G07")
        (field (name "MANUFACTURER") "Texas Instruments")
        (field (name "MANUFACTURER_PART_NUMBER") "sn74lvc1g07_dck_5")
      )
      (libsource (lib "eagle-import") (part "SN74LVC1G07_DCK_5"))
    )
    (comp (ref "U13")
      (value "EMMC")
      (footprint "eagle-import:MICRON_EMMC_153")
      (libsource (lib "eagle-import") (part "EMMC04G-S100-B08U"))
    )
    (comp (ref "WP")
      (value "GHI2_TESTPAD/W_HOLE_1X1")
      (footprint "eagle-import:GHI2_TESTPAD_W_HOLE_1X1")
      (libsource (lib "eagle-import") (part "GHI2_TESTPAD/W_HOLE_1X1"))
    )
    (comp (ref "X2")
      (value "SCHA5B0200")
      (footprint "eagle-import:SCHA5B0200")
      (libsource (lib "eagle-import") (part "SCHA5B0200(ALPS_USD)"))
    )
    (comp (ref "Y1")
      (value "24 MHz")
      (footprint "eagle-import:CRYSTAL_5X3.2MM")
      (libsource (lib "eagle-import") (part "CRYSTAL_5X3.2MM"))
    )
    (comp (ref "Y2")
      (value "32.768kHz")
      (footprint "eagle-import:CRYSTAL_3.2X1.5")
      (libsource (lib "eagle-import") (part "CRYSTAL_3.2X1.5"))
    )
    (comp (ref "C42")
      (value "1nF")
      (footprint "eagle-import:0402-CAP")
      (libsource (lib "eagle-import") (part "Strawson_Eagle_Lib_CAP0402-CAP"))
    )
    (comp (ref "C43")
      (value "0.1uF")
      (footprint "eagle-import:0402-CAP")
      (libsource (lib "eagle-import") (part "Strawson_Eagle_Lib_CAP0402-CAP"))
    )
    (comp (ref "C44")
      (value "0.1uF")
      (footprint "eagle-import:0402-CAP")
      (libsource (lib "eagle-import") (part "Strawson_Eagle_Lib_CAP0402-CAP"))
    )
    (comp (ref "C45")
      (value "0.1uF")
      (footprint "eagle-import:0402-CAP")
      (libsource (lib "eagle-import") (part "Strawson_Eagle_Lib_CAP0402-CAP"))
    )
    (comp (ref "C46")
      (value "10uF")
      (footprint "eagle-import:0805")
      (libsource (lib "eagle-import") (part "Strawson_Eagle_Lib_CAP0805"))
    )
    (comp (ref "C54")
      (value "0.1uF")
      (footprint "eagle-import:0402-CAP")
      (libsource (lib "eagle-import") (part "Strawson_Eagle_Lib_CAP0402-CAP"))
    )
    (comp (ref "C55")
      (value "0.1uF")
      (footprint "eagle-import:0402-CAP")
      (libsource (lib "eagle-import") (part "Strawson_Eagle_Lib_CAP0402-CAP"))
    )
    (comp (ref "C61")
      (value "1uF")
      (footprint "eagle-import:0402-CAP")
      (libsource (lib "eagle-import") (part "Strawson_Eagle_Lib_CAP0402-CAP"))
    )
    (comp (ref "C62")
      (value "0.22uF")
      (footprint "eagle-import:0402-CAP")
      (libsource (lib "eagle-import") (part "Strawson_Eagle_Lib_CAP0402-CAP"))
    )
    (comp (ref "C63")
      (value "0.22uF")
      (footprint "eagle-import:0402-CAP")
      (libsource (lib "eagle-import") (part "Strawson_Eagle_Lib_CAP0402-CAP"))
    )
    (comp (ref "L4")
      (value "120")
      (footprint "eagle-import:L0603")
      (libsource (lib "eagle-import") (part "INDUCTOR/FERRITE-BEAD'0603'"))
    )
    (comp (ref "L5")
      (value "120")
      (footprint "eagle-import:L0603")
      (libsource (lib "eagle-import") (part "INDUCTOR/FERRITE-BEAD'0603'"))
    )
    (comp (ref "R16")
      (value "100K")
      (footprint "eagle-import:0402-RES")
      (libsource (lib "eagle-import") (part "RESISTOR0402-RES"))
    )
    (comp (ref "R17")
      (value "100K")
      (footprint "eagle-import:0402-RES")
      (libsource (lib "eagle-import") (part "RESISTOR0402-RES"))
    )
    (comp (ref "R76")
      (value "33")
      (footprint "eagle-import:0402-RES")
      (libsource (lib "eagle-import") (part "RESISTOR0402-RES"))
    )
    (comp (ref "R77")
      (value "33")
      (footprint "eagle-import:0402-RES")
      (libsource (lib "eagle-import") (part "RESISTOR0402-RES"))
    )
    (comp (ref "R95")
      (value "100K")
      (footprint "eagle-import:0402-RES")
      (libsource (lib "eagle-import") (part "RESISTOR0402-RES"))
    )
    (comp (ref "R109")
      (value "4.7k")
      (footprint "eagle-import:0402-RES")
      (libsource (lib "eagle-import") (part "RESISTOR0402-RES"))
    )
    (comp (ref "R110")
      (value "4.7k")
      (footprint "eagle-import:0402-RES")
      (libsource (lib "eagle-import") (part "RESISTOR0402-RES"))
    )
    (comp (ref "R111")
      (value "0")
      (footprint "eagle-import:0402-RES")
      (libsource (lib "eagle-import") (part "RESISTOR0402-RES"))
    )
    (comp (ref "R112")
      (value "0")
      (footprint "eagle-import:0603-RES")
      (libsource (lib "eagle-import") (part "RESISTOR0603"))
    )
    (comp (ref "R113")
      (value "100K")
      (footprint "eagle-import:0402-RES")
      (libsource (lib "eagle-import") (part "RESISTOR0402-RES"))
    )
    (comp (ref "R115")
      (value "100K")
      (footprint "eagle-import:0402-RES")
      (libsource (lib "eagle-import") (part "RESISTOR0402-RES"))
    )
    (comp (ref "R116")
      (value "100K")
      (footprint "eagle-import:0402-RES")
      (libsource (lib "eagle-import") (part "RESISTOR0402-RES"))
    )
    (comp (ref "R118")
      (value "100K")
      (footprint "eagle-import:0402-RES")
      (libsource (lib "eagle-import") (part "RESISTOR0402-RES"))
    )
    (comp (ref "R119")
      (value "0, DNP")
      (footprint "eagle-import:0603-RES")
      (libsource (lib "eagle-import") (part "RESISTOR0603"))
    )
    (comp (ref "R120")
      (value "100K")
      (footprint "eagle-import:0402-RES")
      (libsource (lib "eagle-import") (part "RESISTOR0402-RES"))
    )
    (comp (ref "R121")
      (value "0, DNP")
      (footprint "eagle-import:0603-RES")
      (libsource (lib "eagle-import") (part "RESISTOR0603"))
    )
    (comp (ref "R122")
      (value "100K")
      (footprint "eagle-import:0402-RES")
      (libsource (lib "eagle-import") (part "RESISTOR0402-RES"))
    )
    (comp (ref "R125")
      (value "100K")
      (footprint "eagle-import:0402-RES")
      (libsource (lib "eagle-import") (part "RESISTOR0402-RES"))
    )
    (comp (ref "R127")
      (value "100K")
      (footprint "eagle-import:0402-RES")
      (libsource (lib "eagle-import") (part "RESISTOR0402-RES"))
    )
    (comp (ref "R129")
      (value "100K")
      (footprint "eagle-import:0402-RES")
      (libsource (lib "eagle-import") (part "RESISTOR0402-RES"))
    )
    (comp (ref "R131")
      (value "100K")
      (footprint "eagle-import:0402-RES")
      (libsource (lib "eagle-import") (part "RESISTOR0402-RES"))
    )
    (comp (ref "R135")
      (value "100K")
      (footprint "eagle-import:0402-RES")
      (libsource (lib "eagle-import") (part "RESISTOR0402-RES"))
    )
    (comp (ref "R140")
      (value "100K")
      (footprint "eagle-import:0402-RES")
      (libsource (lib "eagle-import") (part "RESISTOR0402-RES"))
    )
    (comp (ref "R143")
      (value "100K")
      (footprint "eagle-import:0402-RES")
      (libsource (lib "eagle-import") (part "RESISTOR0402-RES"))
    )
    (comp (ref "R149")
      (value "0")
      (footprint "eagle-import:0402-RES")
      (libsource (lib "eagle-import") (part "RESISTOR0402-RES"))
    )
    (comp (ref "R150")
      (value "0")
      (footprint "eagle-import:0402-RES")
      (libsource (lib "eagle-import") (part "RESISTOR0402-RES"))
    )
    (comp (ref "R156")
      (value "33")
      (footprint "eagle-import:0402-RES")
      (libsource (lib "eagle-import") (part "RESISTOR0402-RES"))
    )
    (comp (ref "U3")
      (value "TPD4S012DRY")
      (footprint "eagle-import:SON-6(TI)-DRY")
      (libsource (lib "eagle-import") (part "TPD4S012DRYR"))
    )
    (comp (ref "U4")
      (value "TPD4S012DRY")
      (footprint "eagle-import:SON-6(TI)-DRY")
      (libsource (lib "eagle-import") (part "TPD4S012DRYR"))
    )
    (comp (ref "U8")
      (value "TPS2105_DBV_5")
      (footprint "eagle-import:DBV5")
      (fields
        (field (name "GENERIC_PART_NUMBER") "TPS2105")
        (field (name "MANUFACTURER") "Texas Instruments")
        (field (name "MANUFACTURER_PART_NUMBER") "tps2105_dbv_5")
      )
      (libsource (lib "eagle-import") (part "TPS2105_DBV_5"))
    )
    (comp (ref "X3")
      (value "USB1")
      (footprint "eagle-import:USB_HOST_HORIZONTAL_W_CHASSIS_GND")
      (libsource (lib "eagle-import") (part "USB_HOST_W/CHASSIS_GND"))
    )
    (comp (ref "X4")
      (value "10118192-0001LF")
      (footprint "eagle-import:10118192-0001LF(MICRO-USB-B-AMPHENOL-FCI)")
      (libsource (lib "eagle-import") (part "10118192-0001LF"))
    )
    (comp (ref "ANT1")
      (value "U.FL-R-SMT-1(10)")
      (footprint "eagle-import:U.FL-R-SMT-1")
      (libsource (lib "eagle-import") (part "U.FL-R-SMT-1"))
    )
    (comp (ref "ANT2")
      (value "U.FL-R-SMT-1(10)")
      (footprint "eagle-import:U.FL-R-SMT-1")
      (libsource (lib "eagle-import") (part "U.FL-R-SMT-1"))
    )
    (comp (ref "C47")
      (value "0.1uF")
      (footprint "eagle-import:0402-CAP")
      (libsource (lib "eagle-import") (part "Strawson_Eagle_Lib_CAP0402-CAP"))
    )
    (comp (ref "C48")
      (value "10pF")
      (footprint "eagle-import:0402-CAP")
      (libsource (lib "eagle-import") (part "Strawson_Eagle_Lib_CAP0402-CAP"))
    )
    (comp (ref "C49")
      (value "0.1uF")
      (footprint "eagle-import:0402-CAP")
      (libsource (lib "eagle-import") (part "Strawson_Eagle_Lib_CAP0402-CAP"))
    )
    (comp (ref "C50")
      (value "0.1uF")
      (footprint "eagle-import:0402-CAP")
      (libsource (lib "eagle-import") (part "Strawson_Eagle_Lib_CAP0402-CAP"))
    )
    (comp (ref "C51")
      (value "0.1uF")
      (footprint "eagle-import:0402-CAP")
      (libsource (lib "eagle-import") (part "Strawson_Eagle_Lib_CAP0402-CAP"))
    )
    (comp (ref "C52")
      (value "0.1uF")
      (footprint "eagle-import:0402-CAP")
      (libsource (lib "eagle-import") (part "Strawson_Eagle_Lib_CAP0402-CAP"))
    )
    (comp (ref "C53")
      (value "10uF")
      (footprint "eagle-import:0805")
      (libsource (lib "eagle-import") (part "CAP0805"))
    )
    (comp (ref "C56")
      (value "0.1uF")
      (footprint "eagle-import:0402-CAP")
      (libsource (lib "eagle-import") (part "Strawson_Eagle_Lib_CAP0402-CAP"))
    )
    (comp (ref "C57")
      (value "1uF")
      (footprint "eagle-import:0402-CAP")
      (libsource (lib "eagle-import") (part "Strawson_Eagle_Lib_CAP0402-CAP"))
    )
    (comp (ref "C58")
      (value "10pF")
      (footprint "eagle-import:0402-CAP")
      (libsource (lib "eagle-import") (part "Strawson_Eagle_Lib_CAP0402-CAP"))
    )
    (comp (ref "C59")
      (value "10uF")
      (footprint "eagle-import:0805")
      (libsource (lib "eagle-import") (part "CAP0805"))
    )
    (comp (ref "C60")
      (value "10uF")
      (footprint "eagle-import:0805")
      (libsource (lib "eagle-import") (part "CAP0805"))
    )
    (comp (ref "OSC1")
      (value "NZ2520SB-32.768KHZ-NSA3534C")
      (footprint "eagle-import:NZ2520S")
      (libsource (lib "eagle-import") (part "OSCILLATOR"))
    )
    (comp (ref "R9")
      (value "10K, DNP")
      (footprint "eagle-import:0402-RES")
      (libsource (lib "eagle-import") (part "RESISTOR0402-RES"))
    )
    (comp (ref "R78")
      (value "33")
      (footprint "eagle-import:0402-RES")
      (libsource (lib "eagle-import") (part "RESISTOR0402-RES"))
    )
    (comp (ref "R79")
      (value "33")
      (footprint "eagle-import:0402-RES")
      (libsource (lib "eagle-import") (part "RESISTOR0402-RES"))
    )
    (comp (ref "R80")
      (value "33")
      (footprint "eagle-import:0402-RES")
      (libsource (lib "eagle-import") (part "RESISTOR0402-RES"))
    )
    (comp (ref "R81")
      (value "33")
      (footprint "eagle-import:0402-RES")
      (libsource (lib "eagle-import") (part "RESISTOR0402-RES"))
    )
    (comp (ref "R82")
      (value "33")
      (footprint "eagle-import:0402-RES")
      (libsource (lib "eagle-import") (part "RESISTOR0402-RES"))
    )
    (comp (ref "R83")
      (value "33")
      (footprint "eagle-import:0402-RES")
      (libsource (lib "eagle-import") (part "RESISTOR0402-RES"))
    )
    (comp (ref "R84")
      (value "33")
      (footprint "eagle-import:0402-RES")
      (libsource (lib "eagle-import") (part "RESISTOR0402-RES"))
    )
    (comp (ref "R85")
      (value "33")
      (footprint "eagle-import:0402-RES")
      (libsource (lib "eagle-import") (part "RESISTOR0402-RES"))
    )
    (comp (ref "R86")
      (value "33")
      (footprint "eagle-import:0402-RES")
      (libsource (lib "eagle-import") (part "RESISTOR0402-RES"))
    )
    (comp (ref "R87")
      (value "100K")
      (footprint "eagle-import:0402-RES")
      (libsource (lib "eagle-import") (part "RESISTOR0402-RES"))
    )
    (comp (ref "R88")
      (value "100K")
      (footprint "eagle-import:0402-RES")
      (libsource (lib "eagle-import") (part "RESISTOR0402-RES"))
    )
    (comp (ref "R89")
      (value "1K, DNP")
      (footprint "eagle-import:0402-RES")
      (libsource (lib "eagle-import") (part "RESISTOR0402-RES"))
    )
    (comp (ref "R90")
      (value "1K")
      (footprint "eagle-import:0402-RES")
      (libsource (lib "eagle-import") (part "RESISTOR0402-RES"))
    )
    (comp (ref "R92")
      (value "33")
      (footprint "eagle-import:0402-RES")
      (libsource (lib "eagle-import") (part "RESISTOR0402-RES"))
    )
    (comp (ref "R93")
      (value "33")
      (footprint "eagle-import:0402-RES")
      (libsource (lib "eagle-import") (part "RESISTOR0402-RES"))
    )
    (comp (ref "R96")
      (value "33")
      (footprint "eagle-import:0402-RES")
      (libsource (lib "eagle-import") (part "RESISTOR0402-RES"))
    )
    (comp (ref "R97")
      (value "33")
      (footprint "eagle-import:0402-RES")
      (libsource (lib "eagle-import") (part "RESISTOR0402-RES"))
    )
    (comp (ref "R98")
      (value "10K")
      (footprint "eagle-import:0402-RES")
      (libsource (lib "eagle-import") (part "RESISTOR0402-RES"))
    )
    (comp (ref "R99")
      (value "10K")
      (footprint "eagle-import:0402-RES")
      (libsource (lib "eagle-import") (part "RESISTOR0402-RES"))
    )
    (comp (ref "R100")
      (value "33")
      (footprint "eagle-import:0402-RES")
      (libsource (lib "eagle-import") (part "RESISTOR0402-RES"))
    )
    (comp (ref "R101")
      (value "10K")
      (footprint "eagle-import:0402-RES")
      (libsource (lib "eagle-import") (part "RESISTOR0402-RES"))
    )
    (comp (ref "R102")
      (value "10K")
      (footprint "eagle-import:0402-RES")
      (libsource (lib "eagle-import") (part "RESISTOR0402-RES"))
    )
    (comp (ref "R103")
      (value "10K")
      (footprint "eagle-import:0402-RES")
      (libsource (lib "eagle-import") (part "RESISTOR0402-RES"))
    )
    (comp (ref "R105")
      (value "10K")
      (footprint "eagle-import:0402-RES")
      (libsource (lib "eagle-import") (part "RESISTOR0402-RES"))
    )
    (comp (ref "R106")
      (value "1.5K")
      (footprint "eagle-import:0402-RES")
      (libsource (lib "eagle-import") (part "RESISTOR0402-RES"))
    )
    (comp (ref "R108")
      (value "1K, DNP")
      (footprint "eagle-import:0402-RES")
      (libsource (lib "eagle-import") (part "RESISTOR0402-RES"))
    )
    (comp (ref "R123")
      (value "33")
      (footprint "eagle-import:0402-RES")
      (libsource (lib "eagle-import") (part "RESISTOR0402-RES"))
    )
    (comp (ref "R124")
      (value "33")
      (footprint "eagle-import:0402-RES")
      (libsource (lib "eagle-import") (part "RESISTOR0402-RES"))
    )
    (comp (ref "U2")
      (value "SN74LV1T126DBVR")
      (footprint "eagle-import:BEAGLEBONE_BLUE_SOT23-5")
      (libsource (lib "eagle-import") (part "SN74LV1T126DBVR"))
    )
    (comp (ref "U7")
      (value "WL1835MODGBMOCT")
      (footprint "eagle-import:MOC-100(TI)")
      (libsource (lib "eagle-import") (part "WL1835MOD"))
    )
    (comp (ref "U9")
      (value "TXS0108ERGYR")
      (footprint "eagle-import:R-PVQFN-N20(TI)")
      (libsource (lib "eagle-import") (part "TXS0108ERGYR"))
    )
    (comp (ref "U10")
      (value "TXS0108ERGYR")
      (footprint "eagle-import:R-PVQFN-N20(TI)")
      (libsource (lib "eagle-import") (part "TXS0108ERGYR"))
    )
  )
  (nets
    (net (code "1") (name "3.3V") (class "Default")
      (node (ref "BMP") (pin "2") (pinfunction "CSB_2") (pintype "input"))
      (node (ref "BMP") (pin "6") (pinfunction "VDDIO_6") (pintype "input"))
      (node (ref "BMP") (pin "8") (pinfunction "VDD_8") (pintype "power_in"))
      (node (ref "C13") (pin "1") (pinfunction "1_1") (pintype "passive"))
      (node (ref "C16") (pin "1") (pinfunction "1_1") (pintype "passive"))
      (node (ref "C2") (pin "2") (pinfunction "2_2") (pintype "passive"))
      (node (ref "C27") (pin "1") (pinfunction "1_1") (pintype "passive"))
      (node (ref "C28") (pin "1") (pinfunction "1_1") (pintype "passive"))
      (node (ref "C34") (pin "2") (pinfunction "2_2") (pintype "passive"))
      (node (ref "C35") (pin "2") (pinfunction "2_2") (pintype "passive"))
      (node (ref "C37") (pin "1") (pinfunction "1_1") (pintype "passive"))
      (node (ref "C38") (pin "1") (pinfunction "1_1") (pintype "passive"))
      (node (ref "C39") (pin "1") (pinfunction "1_1") (pintype "passive"))
      (node (ref "C40") (pin "1") (pinfunction "1_1") (pintype "passive"))
      (node (ref "C41") (pin "1") (pinfunction "1_1") (pintype "passive"))
      (node (ref "C49") (pin "2") (pinfunction "2_2") (pintype "passive"))
      (node (ref "C51") (pin "2") (pinfunction "2_2") (pintype "passive"))
      (node (ref "C53") (pin "1") (pinfunction "1_1") (pintype "passive"))
      (node (ref "C56") (pin "1") (pinfunction "1_1") (pintype "passive"))
      (node (ref "C59") (pin "1") (pinfunction "1_1") (pintype "passive"))
      (node (ref "C8") (pin "1") (pinfunction "1_1") (pintype "passive"))
      (node (ref "C9") (pin "2") (pinfunction "2_2") (pintype "passive"))
      (node (ref "CAN") (pin "2") (pinfunction "2_2") (pintype "bidirectional"))
      (node (ref "DSM2") (pin "P$1") (pinfunction "1_P$1") (pintype "bidirectional"))
      (node (ref "E1") (pin "2") (pinfunction "2_2") (pintype "bidirectional"))
      (node (ref "E2") (pin "2") (pinfunction "2_2") (pintype "bidirectional"))
      (node (ref "E3") (pin "2") (pinfunction "2_2") (pintype "bidirectional"))
      (node (ref "E4") (pin "2") (pinfunction "2_2") (pintype "bidirectional"))
      (node (ref "GP0") (pin "2") (pinfunction "2_2") (pintype "bidirectional"))
      (node (ref "GP1") (pin "2") (pinfunction "2_2") (pintype "bidirectional"))
      (node (ref "H1") (pin "20") (pinfunction "VCC_20") (pintype "bidirectional"))
      (node (ref "H2") (pin "20") (pinfunction "VCC_20") (pintype "bidirectional"))
      (node (ref "I2C") (pin "2") (pinfunction "2_2") (pintype "bidirectional"))
      (node (ref "IMU") (pin "1") (pinfunction "RESV_1") (pintype "bidirectional"))
      (node (ref "IMU") (pin "13") (pinfunction "VDD_13") (pintype "bidirectional"))
      (node (ref "IMU") (pin "22") (pinfunction "NCS_22") (pintype "bidirectional"))
      (node (ref "IMU") (pin "8") (pinfunction "VDDIO_8") (pintype "bidirectional"))
      (node (ref "PWR") (pin "3") (pinfunction "3_3") (pintype "bidirectional"))
      (node (ref "R10") (pin "1") (pinfunction "1_1") (pintype "passive"))
      (node (ref "R109") (pin "1") (pinfunction "1_1") (pintype "passive"))
      (node (ref "R11") (pin "2") (pinfunction "2_2") (pintype "passive"))
      (node (ref "R116") (pin "2") (pinfunction "2_2") (pintype "passive"))
      (node (ref "R118") (pin "2") (pinfunction "2_2") (pintype "passive"))
      (node (ref "R12") (pin "2") (pinfunction "2_2") (pintype "passive"))
      (node (ref "R120") (pin "2") (pinfunction "2_2") (pintype "passive"))
      (node (ref "R122") (pin "2") (pinfunction "2_2") (pintype "passive"))
      (node (ref "R13") (pin "1") (pinfunction "1_1") (pintype "passive"))
      (node (ref "R140") (pin "2") (pinfunction "2_2") (pintype "passive"))
      (node (ref "R2") (pin "2") (pinfunction "2_2") (pintype "passive"))
      (node (ref "R23") (pin "2") (pinfunction "2_2") (pintype "passive"))
      (node (ref "R26") (pin "2") (pinfunction "2_2") (pintype "passive"))
      (node (ref "R35") (pin "2") (pinfunction "2_2") (pintype "passive"))
      (node (ref "R54") (pin "2") (pinfunction "2_2") (pintype "passive"))
      (node (ref "R55") (pin "2") (pinfunction "2_2") (pintype "passive"))
      (node (ref "R56") (pin "2") (pinfunction "2_2") (pintype "passive"))
      (node (ref "R57") (pin "2") (pinfunction "2_2") (pintype "passive"))
      (node (ref "R58") (pin "2") (pinfunction "2_2") (pintype "passive"))
      (node (ref "R60") (pin "2") (pinfunction "2_2") (pintype "passive"))
      (node (ref "R65") (pin "2") (pinfunction "2_2") (pintype "passive"))
      (node (ref "R66") (pin "2") (pinfunction "2_2") (pintype "passive"))
      (node (ref "R67") (pin "2") (pinfunction "2_2") (pintype "passive"))
      (node (ref "R68") (pin "2") (pinfunction "2_2") (pintype "passive"))
      (node (ref "R69") (pin "2") (pinfunction "2_2") (pintype "passive"))
      (node (ref "R70") (pin "2") (pinfunction "2_2") (pintype "passive"))
      (node (ref "R71") (pin "2") (pinfunction "2_2") (pintype "passive"))
      (node (ref "R72") (pin "2") (pinfunction "2_2") (pintype "passive"))
      (node (ref "R73") (pin "2") (pinfunction "2_2") (pintype "passive"))
      (node (ref "R74") (pin "2") (pinfunction "2_2") (pintype "passive"))
      (node (ref "R75") (pin "2") (pinfunction "2_2") (pintype "passive"))
      (node (ref "R94") (pin "2") (pinfunction "2_2") (pintype "passive"))
      (node (ref "S1.1") (pin "2") (pinfunction "2_2") (pintype "bidirectional"))
      (node (ref "S1.2") (pin "2") (pinfunction "2_2") (pintype "bidirectional"))
      (node (ref "SIP") (pin "U20") (pinfunction "VOUT_USER_3P3V_0_U20") (pintype "power_in"))
      (node (ref "SIP") (pin "V20") (pinfunction "VOUT_USER_3P3V_1_V20") (pintype "power_in"))
      (node (ref "U1") (pin "5") (pinfunction "VIO_5") (pintype "power_in"))
      (node (ref "U10") (pin "19") (pinfunction "VCCB_19") (pintype "bidirectional"))
      (node (ref "U13") (pin "C6") (pinfunction "VCCQ1_C6") (pintype "bidirectional"))
      (node (ref "U13") (pin "E6") (pinfunction "VCC1_E6") (pintype "bidirectional"))
      (node (ref "U13") (pin "F5") (pinfunction "VCC2_F5") (pintype "bidirectional"))
      (node (ref "U13") (pin "J10") (pinfunction "VCC3_J10") (pintype "bidirectional"))
      (node (ref "U13") (pin "K9") (pinfunction "VCC4_K9") (pintype "bidirectional"))
      (node (ref "U13") (pin "M4") (pinfunction "VCCQ2_M4") (pintype "bidirectional"))
      (node (ref "U13") (pin "N4") (pinfunction "VCCQ3_N4") (pintype "bidirectional"))
      (node (ref "U13") (pin "P3") (pinfunction "VCCQ4_P3") (pintype "bidirectional"))
      (node (ref "U13") (pin "P5") (pinfunction "VCCQ5_P5") (pintype "bidirectional"))
      (node (ref "U5") (pin "4") (pinfunction "VCC_4") (pintype "power_in"))
      (node (ref "U7") (pin "46") (pinfunction "VBAT_IN1_46") (pintype "bidirectional"))
      (node (ref "U7") (pin "47") (pinfunction "VBAT_IN2_47") (pintype "bidirectional"))
      (node (ref "U9") (pin "19") (pinfunction "VCCB_19") (pintype "bidirectional"))
      (node (ref "UT0") (pin "2") (pinfunction "2_2") (pintype "bidirectional"))
      (node (ref "UT1") (pin "2") (pinfunction "2_2") (pintype "bidirectional"))
      (node (ref "UT5") (pin "2") (pinfunction "2_2") (pintype "bidirectional"))
      (node (ref "X2") (pin "4") (pinfunction "VDD_4") (pintype "bidirectional"))
    )
    (net (code "2") (name "5.0V") (class "Default")
      (node (ref "5VREG") (pin "3") (pinfunction "FB_3") (pintype "power_in"))
      (node (ref "C5") (pin "1") (pinfunction "1_1") (pintype "passive"))
      (node (ref "C63") (pin "1") (pinfunction "1_1") (pintype "passive"))
      (node (ref "GPS") (pin "5") (pinfunction "5_5") (pintype "bidirectional"))
      (node (ref "L1") (pin "2") (pinfunction "2_2") (pintype "passive"))
      (node (ref "PWR") (pin "4") (pinfunction "4_4") (pintype "bidirectional"))
      (node (ref "R119") (pin "2") (pinfunction "2_2") (pintype "passive"))
      (node (ref "R95") (pin "2") (pinfunction "2_2") (pintype "passive"))
      (node (ref "SIP") (pin "Y5") (pinfunction "VIN_AC_0_Y5") (pintype "power_in"))
      (node (ref "SIP") (pin "Y6") (pinfunction "VIN_AC_1_Y6") (pintype "power_in"))
      (node (ref "U8") (pin "1") (pinfunction "EN_1") (pintype "input"))
      (node (ref "U8") (pin "5") (pinfunction "IN1_5") (pintype "input"))
    )
    (net (code "3") (name "32.768KHZ") (class "Default")
      (node (ref "OSC1") (pin "3") (pinfunction "OUT_3") (pintype "bidirectional"))
      (node (ref "U7") (pin "36") (pinfunction "EXT_32K_36") (pintype "bidirectional"))
    )
    (net (code "4") (name "AIN0") (class "Default")
      (node (ref "ADC") (pin "3") (pinfunction "3_3") (pintype "bidirectional"))
      (node (ref "SIP") (pin "B6") (pinfunction "AIN0_B6") (pintype "bidirectional"))
    )
    (net (code "5") (name "AIN1") (class "Default")
      (node (ref "ADC") (pin "4") (pinfunction "4_4") (pintype "bidirectional"))
      (node (ref "SIP") (pin "C7") (pinfunction "AIN1_C7") (pintype "bidirectional"))
    )
    (net (code "6") (name "AIN2") (class "Default")
      (node (ref "ADC") (pin "5") (pinfunction "5_5") (pintype "bidirectional"))
      (node (ref "SIP") (pin "B7") (pinfunction "AIN2_B7") (pintype "bidirectional"))
    )
    (net (code "7") (name "AIN3") (class "Default")
      (node (ref "ADC") (pin "6") (pinfunction "6_6") (pintype "bidirectional"))
      (node (ref "SIP") (pin "A7") (pinfunction "AIN3_A7") (pintype "bidirectional"))
    )
    (net (code "8") (name "BATT_LED_1") (class "Default")
      (node (ref "B0") (pin "A") (pinfunction "A_A") (pintype "passive"))
      (node (ref "SIP") (pin "U12") (pinfunction "GPIO0_27_U12_U12") (pintype "bidirectional"))
    )
    (net (code "9") (name "BATT_LED_2") (class "Default")
      (node (ref "B1") (pin "A") (pinfunction "A_A") (pintype "passive"))
      (node (ref "R143") (pin "2") (pinfunction "2_2") (pintype "passive"))
      (node (ref "SIP") (pin "T5") (pinfunction "LCD_DATA15_T5_T5") (pintype "bidirectional"))
    )
    (net (code "10") (name "BATT_LED_3") (class "Default")
      (node (ref "B2") (pin "A") (pinfunction "A_A") (pintype "passive"))
      (node (ref "SIP") (pin "V6") (pinfunction "GPIO1_29_V6_V6") (pintype "bidirectional"))
    )
    (net (code "11") (name "BATT_LED_4") (class "Default")
      (node (ref "B3") (pin "A") (pinfunction "A_A") (pintype "passive"))
      (node (ref "SIP") (pin "T11") (pinfunction "GPIO0_26_T11_T11") (pintype "bidirectional"))
    )
    (net (code "12") (name "BATT_MID") (class "Default")
      (node (ref "LIPO") (pin "P$2") (pinfunction "2_P$2") (pintype "passive"))
      (node (ref "R27") (pin "1") (pinfunction "1_1") (pintype "passive"))
      (node (ref "R30") (pin "1") (pinfunction "1_1") (pintype "passive"))
      (node (ref "R44") (pin "1") (pinfunction "1_1") (pintype "passive"))
    )
    (net (code "13") (name "BATT_MINUS") (class "Default")
      (node (ref "BAL") (pin "5") (pinfunction "GND_5") (pintype "bidirectional"))
      (node (ref "BAL") (pin "6") (pinfunction "CB_EN_6") (pintype "bidirectional"))
      (node (ref "C1") (pin "2") (pinfunction "2_2") (pintype "passive"))
      (node (ref "C15") (pin "1") (pinfunction "1_1") (pintype "passive"))
      (node (ref "C18") (pin "1") (pinfunction "1_1") (pintype "passive"))
      (node (ref "C19") (pin "2") (pinfunction "2_2") (pintype "passive"))
      (node (ref "LIPO") (pin "P$3") (pinfunction "3_P$3") (pintype "passive"))
      (node (ref "PROT") (pin "2") (pinfunction "VM_2") (pintype "bidirectional"))
      (node (ref "PROT") (pin "6") (pinfunction "VSS_6") (pintype "bidirectional"))
      (node (ref "Q1") (pin "1") (pinfunction "S_1") (pintype "passive"))
      (node (ref "Q1") (pin "2") (pinfunction "S_2") (pintype "passive"))
      (node (ref "Q1") (pin "3") (pinfunction "S_3") (pintype "passive"))
    )
    (net (code "14") (name "BT_AUD_CLK") (class "Default")
      (node (ref "R124") (pin "1") (pinfunction "1_1") (pintype "passive"))
      (node (ref "U10") (pin "1") (pinfunction "A1_1") (pintype "bidirectional"))
    )
    (net (code "15") (name "BT_AUD_FSYNC") (class "Default")
      (node (ref "R123") (pin "1") (pinfunction "1_1") (pintype "passive"))
      (node (ref "U10") (pin "3") (pinfunction "A2_3") (pintype "bidirectional"))
    )
    (net (code "16") (name "BT_AUD_IN") (class "Default")
      (node (ref "R97") (pin "1") (pinfunction "1_1") (pintype "passive"))
      (node (ref "U10") (pin "5") (pinfunction "A4_5") (pintype "bidirectional"))
    )
    (net (code "17") (name "BT_AUD_OUT") (class "Default")
      (node (ref "R100") (pin "1") (pinfunction "1_1") (pintype "passive"))
      (node (ref "U10") (pin "4") (pinfunction "A3_4") (pintype "bidirectional"))
    )
    (net (code "18") (name "BT_EN") (class "Default")
      (node (ref "SIP") (pin "K17") (pinfunction "K17_K17") (pintype "bidirectional"))
      (node (ref "U9") (pin "18") (pinfunction "B2_18") (pintype "bidirectional"))
    )
    (net (code "19") (name "BT_EN_1V8") (class "Default")
      (node (ref "R88") (pin "1") (pinfunction "1_1") (pintype "passive"))
      (node (ref "U7") (pin "41") (pinfunction "BT_EN_41") (pintype "bidirectional"))
      (node (ref "U9") (pin "3") (pinfunction "A2_3") (pintype "bidirectional"))
    )
    (net (code "20") (name "BT_HCI_CTS") (class "Default")
      (node (ref "R86") (pin "1") (pinfunction "1_1") (pintype "passive"))
      (node (ref "U10") (pin "8") (pinfunction "A7_8") (pintype "bidirectional"))
    )
    (net (code "21") (name "BT_HCI_RTS") (class "Default")
      (node (ref "R85") (pin "1") (pinfunction "1_1") (pintype "passive"))
      (node (ref "U10") (pin "9") (pinfunction "A8_9") (pintype "bidirectional"))
    )
    (net (code "22") (name "BT_HCI_RX") (class "Default")
      (node (ref "R96") (pin "1") (pinfunction "1_1") (pintype "passive"))
      (node (ref "U10") (pin "6") (pinfunction "A5_6") (pintype "bidirectional"))
    )
    (net (code "23") (name "BT_HCI_TX") (class "Default")
      (node (ref "R92") (pin "1") (pinfunction "1_1") (pintype "passive"))
      (node (ref "U10") (pin "7") (pinfunction "A6_7") (pintype "bidirectional"))
    )
    (net (code "24") (name "CANH") (class "Default")
      (node (ref "CAN") (pin "3") (pinfunction "3_3") (pintype "bidirectional"))
      (node (ref "R104") (pin "1") (pinfunction "1_1") (pintype "passive"))
      (node (ref "U1") (pin "7") (pinfunction "CANH_7") (pintype "bidirectional"))
    )
    (net (code "25") (name "CANL") (class "Default")
      (node (ref "CAN") (pin "4") (pinfunction "4_4") (pintype "bidirectional"))
      (node (ref "R104") (pin "2") (pinfunction "2_2") (pintype "passive"))
      (node (ref "U1") (pin "6") (pinfunction "CANL_6") (pintype "bidirectional"))
    )
    (net (code "26") (name "CGND") (class "Default")
      (node (ref "MGT1") (pin "P$1") (pinfunction "P$1_P$1") (pintype "bidirectional"))
      (node (ref "MGT2") (pin "P$1") (pinfunction "P$1_P$1") (pintype "bidirectional"))
      (node (ref "MGT3") (pin "P$1") (pinfunction "P$1_P$1") (pintype "bidirectional"))
      (node (ref "MGT4") (pin "P$1") (pinfunction "P$1_P$1") (pintype "bidirectional"))
      (node (ref "R107") (pin "2") (pinfunction "2_2") (pintype "passive"))
      (node (ref "X2") (pin "CGND1") (pinfunction "CGND1_CGND1") (pintype "bidirectional"))
      (node (ref "X2") (pin "CGND2") (pinfunction "CGND2_CGND2") (pintype "bidirectional"))
      (node (ref "X2") (pin "CGND3") (pinfunction "CGND3_CGND3") (pintype "bidirectional"))
      (node (ref "X2") (pin "CGND4") (pinfunction "CGND4_CGND4") (pintype "bidirectional"))
      (node (ref "X2") (pin "CGND5") (pinfunction "CGND5_CGND5") (pintype "bidirectional"))
      (node (ref "X2") (pin "CGND6") (pinfunction "CGND6_CGND6") (pintype "bidirectional"))
      (node (ref "X3") (pin "5") (pinfunction "CG1_5") (pintype "bidirectional"))
      (node (ref "X3") (pin "6") (pinfunction "CG2_6") (pintype "bidirectional"))
      (node (ref "X4") (pin "CGND1") (pinfunction "SGND1_CGND1") (pintype "bidirectional"))
      (node (ref "X4") (pin "CGND2") (pinfunction "SGND2_CGND2") (pintype "bidirectional"))
      (node (ref "X4") (pin "CGND3") (pinfunction "SGND3_CGND3") (pintype "bidirectional"))
      (node (ref "X4") (pin "CGND4") (pinfunction "SGND4_CGND4") (pintype "bidirectional"))
      (node (ref "X4") (pin "CGND5") (pinfunction "SGND5_CGND5") (pintype "bidirectional"))
      (node (ref "X4") (pin "CGND6") (pinfunction "SGND6_CGND6") (pintype "bidirectional"))
    )
    (net (code "27") (name "CHG_EN") (class "Default")
      (node (ref "CHGIC") (pin "6") (pinfunction "EN_6") (pintype "bidirectional"))
      (node (ref "R7") (pin "2") (pinfunction "2_2") (pintype "passive"))
      (node (ref "R8") (pin "1") (pinfunction "1_1") (pintype "passive"))
    )
    (net (code "28") (name "DCAN1_RX") (class "Default")
      (node (ref "SIP") (pin "E17") (pinfunction "UART0_RTSN_E17_E17") (pintype "bidirectional"))
      (node (ref "U1") (pin "4") (pinfunction "RXD_4") (pintype "output"))
    )
    (net (code "29") (name "DCAN1_SILENT") (class "Default")
      (node (ref "SIP") (pin "M16") (pinfunction "M16_M16") (pintype "bidirectional"))
      (node (ref "U1") (pin "8") (pinfunction "S_8") (pintype "input"))
    )
    (net (code "30") (name "DCAN1_TX") (class "Default")
      (node (ref "SIP") (pin "E18") (pinfunction "UART0_CTSN_E18_E18") (pintype "bidirectional"))
      (node (ref "U1") (pin "1") (pinfunction "TXD_1") (pintype "input"))
    )
    (net (code "31") (name "DO") (class "Default")
      (node (ref "PROT") (pin "1") (pinfunction "DO_1") (pintype "bidirectional"))
      (node (ref "Q1") (pin "4") (pinfunction "G_4") (pintype "passive"))
    )
    (net (code "32") (name "EMMC_RST") (class "Default")
      (node (ref "R94") (pin "1") (pinfunction "1_1") (pintype "passive"))
      (node (ref "SIP") (pin "R14") (pinfunction "EMMCRST_GPIO1_20_R14_R14") (pintype "bidirectional"))
      (node (ref "U13") (pin "K5") (pinfunction "RST#_K5") (pintype "bidirectional"))
    )
    (net (code "33") (name "EQEP_0A") (class "Default")
      (node (ref "E1") (pin "3") (pinfunction "3_3") (pintype "bidirectional"))
      (node (ref "SIP") (pin "B12") (pinfunction "GPIO3_18_B12_B12") (pintype "bidirectional"))
    )
    (net (code "34") (name "EQEP_0B") (class "Default")
      (node (ref "E1") (pin "4") (pinfunction "4_4") (pintype "bidirectional"))
      (node (ref "SIP") (pin "C13") (pinfunction "GPIO3_19_C13_C13") (pintype "bidirectional"))
    )
    (net (code "35") (name "EQEP_1A") (class "Default")
      (node (ref "E2") (pin "3") (pinfunction "3_3") (pintype "bidirectional"))
      (node (ref "R16") (pin "2") (pinfunction "2_2") (pintype "passive"))
      (node (ref "SIP") (pin "V2") (pinfunction "LCD_DATA12_V2_V2") (pintype "bidirectional"))
    )
    (net (code "36") (name "EQEP_1B") (class "Default")
      (node (ref "E2") (pin "4") (pinfunction "4_4") (pintype "bidirectional"))
      (node (ref "R17") (pin "2") (pinfunction "2_2") (pintype "passive"))
      (node (ref "SIP") (pin "V3") (pinfunction "LCD_DATA13_V3_V3") (pintype "bidirectional"))
    )
    (net (code "37") (name "EQEP_2A") (class "Default")
      (node (ref "E3") (pin "3") (pinfunction "3_3") (pintype "bidirectional"))
      (node (ref "SIP") (pin "T12") (pinfunction "GPIO1_12_T12_T12") (pintype "bidirectional"))
    )
    (net (code "38") (name "EQEP_2B") (class "Default")
      (node (ref "E3") (pin "4") (pinfunction "4_4") (pintype "bidirectional"))
      (node (ref "SIP") (pin "R12") (pinfunction "GPIO1_13_R12_R12") (pintype "bidirectional"))
    )
    (net (code "39") (name "GND") (class "Default")
      (node (ref "12V") (pin "OUT") (pinfunction "OUT_OUT") (pintype "bidirectional"))
      (node (ref "5VREG") (pin "4") (pinfunction "SD_4") (pintype "input"))
      (node (ref "5VREG") (pin "5") (pinfunction "GND_5") (pintype "power_in"))
      (node (ref "5VREG") (pin "6") (pinfunction "GND1_6") (pintype "input"))
      (node (ref "5VREG") (pin "7") (pinfunction "GND2_7") (pintype "passive"))
      (node (ref "5VREG") (pin "8") (pinfunction "GND3_8") (pintype "power_in"))
      (node (ref "6VREG") (pin "3") (pinfunction "GND_3") (pintype "bidirectional"))
      (node (ref "ADC") (pin "1") (pinfunction "1_1") (pintype "bidirectional"))
      (node (ref "ANT1") (pin "GND1") (pinfunction "GND1_GND1") (pintype "bidirectional"))
      (node (ref "ANT1") (pin "GND2") (pinfunction "GND2_GND2") (pintype "bidirectional"))
      (node (ref "ANT2") (pin "GND1") (pinfunction "GND1_GND1") (pintype "bidirectional"))
      (node (ref "ANT2") (pin "GND2") (pinfunction "GND2_GND2") (pintype "bidirectional"))
      (node (ref "BMP") (pin "1") (pinfunction "GND_1") (pintype "power_in"))
      (node (ref "BMP") (pin "5") (pinfunction "SDO_5") (pintype "bidirectional"))
      (node (ref "BMP") (pin "7") (pinfunction "GND_7") (pintype "power_in"))
      (node (ref "C10") (pin "1") (pinfunction "1_1") (pintype "passive"))
      (node (ref "C11") (pin "-") (pinfunction "-_-") (pintype "passive"))
      (node (ref "C12") (pin "2") (pinfunction "2_2") (pintype "passive"))
      (node (ref "C13") (pin "2") (pinfunction "2_2") (pintype "passive"))
      (node (ref "C16") (pin "2") (pinfunction "2_2") (pintype "passive"))
      (node (ref "C2") (pin "1") (pinfunction "1_1") (pintype "passive"))
      (node (ref "C20") (pin "1") (pinfunction "1_1") (pintype "passive"))
      (node (ref "C21") (pin "1") (pinfunction "1_1") (pintype "passive"))
      (node (ref "C23") (pin "1") (pinfunction "1_1") (pintype "passive"))
      (node (ref "C24") (pin "1") (pinfunction "1_1") (pintype "passive"))
      (node (ref "C25") (pin "2") (pinfunction "2_2") (pintype "passive"))
      (node (ref "C26") (pin "2") (pinfunction "2_2") (pintype "passive"))
      (node (ref "C27") (pin "2") (pinfunction "2_2") (pintype "passive"))
      (node (ref "C28") (pin "2") (pinfunction "2_2") (pintype "passive"))
      (node (ref "C3") (pin "2") (pinfunction "2_2") (pintype "passive"))
      (node (ref "C33") (pin "2") (pinfunction "2_2") (pintype "passive"))
      (node (ref "C34") (pin "1") (pinfunction "1_1") (pintype "passive"))
      (node (ref "C35") (pin "1") (pinfunction "1_1") (pintype "passive"))
      (node (ref "C36") (pin "2") (pinfunction "2_2") (pintype "passive"))
      (node (ref "C37") (pin "2") (pinfunction "2_2") (pintype "passive"))
      (node (ref "C38") (pin "2") (pinfunction "2_2") (pintype "passive"))
      (node (ref "C39") (pin "2") (pinfunction "2_2") (pintype "passive"))
      (node (ref "C4") (pin "1") (pinfunction "1_1") (pintype "passive"))
      (node (ref "C40") (pin "2") (pinfunction "2_2") (pintype "passive"))
      (node (ref "C41") (pin "2") (pinfunction "2_2") (pintype "passive"))
      (node (ref "C45") (pin "2") (pinfunction "2_2") (pintype "passive"))
      (node (ref "C46") (pin "2") (pinfunction "2_2") (pintype "passive"))
      (node (ref "C47") (pin "2") (pinfunction "2_2") (pintype "passive"))
      (node (ref "C49") (pin "1") (pinfunction "1_1") (pintype "passive"))
      (node (ref "C5") (pin "2") (pinfunction "2_2") (pintype "passive"))
      (node (ref "C50") (pin "2") (pinfunction "2_2") (pintype "passive"))
      (node (ref "C51") (pin "1") (pinfunction "1_1") (pintype "passive"))
      (node (ref "C52") (pin "2") (pinfunction "2_2") (pintype "passive"))
      (node (ref "C53") (pin "2") (pinfunction "2_2") (pintype "passive"))
      (node (ref "C54") (pin "2") (pinfunction "2_2") (pintype "passive"))
      (node (ref "C55") (pin "2") (pinfunction "2_2") (pintype "passive"))
      (node (ref "C56") (pin "2") (pinfunction "2_2") (pintype "passive"))
      (node (ref "C57") (pin "1") (pinfunction "1_1") (pintype "passive"))
      (node (ref "C59") (pin "2") (pinfunction "2_2") (pintype "passive"))
      (node (ref "C6") (pin "2") (pinfunction "2_2") (pintype "passive"))
      (node (ref "C60") (pin "1") (pinfunction "1_1") (pintype "passive"))
      (node (ref "C61") (pin "1") (pinfunction "1_1") (pintype "passive"))
      (node (ref "C62") (pin "2") (pinfunction "2_2") (pintype "passive"))
      (node (ref "C63") (pin "2") (pinfunction "2_2") (pintype "passive"))
      (node (ref "C7") (pin "2") (pinfunction "2_2") (pintype "passive"))
      (node (ref "C8") (pin "2") (pinfunction "2_2") (pintype "passive"))
      (node (ref "C9") (pin "1") (pinfunction "1_1") (pintype "passive"))
      (node (ref "CAN") (pin "1") (pinfunction "1_1") (pintype "bidirectional"))
      (node (ref "CHGIC") (pin "16") (pinfunction "PGND_16") (pintype "bidirectional"))
      (node (ref "CHGIC") (pin "8") (pinfunction "AGND_8") (pintype "bidirectional"))
      (node (ref "D1") (pin "A") (pinfunction "A_A") (pintype "passive"))
      (node (ref "D9") (pin "A") (pinfunction "A_A") (pintype "passive"))
      (node (ref "DSM2") (pin "P$2") (pinfunction "2_P$2") (pintype "bidirectional"))
      (node (ref "E1") (pin "1") (pinfunction "1_1") (pintype "bidirectional"))
      (node (ref "E2") (pin "1") (pinfunction "1_1") (pintype "bidirectional"))
      (node (ref "E3") (pin "1") (pinfunction "1_1") (pintype "bidirectional"))
      (node (ref "E4") (pin "1") (pinfunction "1_1") (pintype "bidirectional"))
      (node (ref "GND") (pin "P$1") (pinfunction "TP_P$1") (pintype "bidirectional"))
      (node (ref "GP0") (pin "1") (pinfunction "1_1") (pintype "bidirectional"))
      (node (ref "GP1") (pin "1") (pinfunction "1_1") (pintype "bidirectional"))
      (node (ref "GPS") (pin "2") (pinfunction "2_2") (pintype "bidirectional"))
      (node (ref "GPS") (pin "6") (pinfunction "6_6") (pintype "bidirectional"))
      (node (ref "H1") (pin "10") (pinfunction "PGND2_10") (pintype "bidirectional"))
      (node (ref "H1") (pin "18") (pinfunction "GND_18") (pintype "bidirectional"))
      (node (ref "H1") (pin "3") (pinfunction "PGND1_3") (pintype "bidirectional"))
      (node (ref "H1") (pin "4") (pinfunction "PGND1_4") (pintype "bidirectional"))
      (node (ref "H1") (pin "9") (pinfunction "PGND2_9") (pintype "bidirectional"))
      (node (ref "H2") (pin "10") (pinfunction "PGND2_10") (pintype "bidirectional"))
      (node (ref "H2") (pin "18") (pinfunction "GND_18") (pintype "bidirectional"))
      (node (ref "H2") (pin "3") (pinfunction "PGND1_3") (pintype "bidirectional"))
      (node (ref "H2") (pin "4") (pinfunction "PGND1_4") (pintype "bidirectional"))
      (node (ref "H2") (pin "9") (pinfunction "PGND2_9") (pintype "bidirectional"))
      (node (ref "I2C") (pin "1") (pinfunction "1_1") (pintype "bidirectional"))
      (node (ref "IMU") (pin "18") (pinfunction "GND_18") (pintype "bidirectional"))
      (node (ref "IMU") (pin "20") (pinfunction "RESV_20") (pintype "bidirectional"))
      (node (ref "IMU") (pin "9") (pinfunction "AD0/SDO_9") (pintype "bidirectional"))
      (node (ref "J2") (pin "P$13") (pinfunction "GND_P$13") (pintype "bidirectional"))
      (node (ref "J2") (pin "P$14") (pinfunction "GND_P$14") (pintype "bidirectional"))
      (node (ref "J2") (pin "P$15") (pinfunction "GND_P$15") (pintype "bidirectional"))
      (node (ref "J2") (pin "P$16") (pinfunction "GND_P$16") (pintype "bidirectional"))
      (node (ref "J2") (pin "P$17") (pinfunction "GND_P$17") (pintype "bidirectional"))
      (node (ref "J2") (pin "P$18") (pinfunction "GND_P$18") (pintype "bidirectional"))
      (node (ref "J2") (pin "P$23") (pinfunction "GND_P$23") (pintype "bidirectional"))
      (node (ref "J2") (pin "P$24") (pinfunction "GND_P$24") (pintype "bidirectional"))
      (node (ref "L4") (pin "1") (pinfunction "1_1") (pintype "passive"))
      (node (ref "MOD") (pin "1") (pinfunction "1_1") (pintype "passive"))
      (node (ref "OSC1") (pin "2") (pinfunction "GND_2") (pintype "bidirectional"))
      (node (ref "PAU") (pin "1") (pinfunction "1_1") (pintype "passive"))
      (node (ref "POW") (pin "1") (pinfunction "1_1") (pintype "passive"))
      (node (ref "PWR") (pin "1") (pinfunction "1_1") (pintype "bidirectional"))
      (node (ref "PWR") (pin "2") (pinfunction "2_2") (pintype "bidirectional"))
      (node (ref "Q1") (pin "5") (pinfunction "D_5") (pintype "passive"))
      (node (ref "Q1") (pin "6") (pinfunction "D_6") (pintype "passive"))
      (node (ref "Q1") (pin "7") (pinfunction "D_7") (pintype "passive"))
      (node (ref "Q1") (pin "8") (pinfunction "D_8") (pintype "passive"))
      (node (ref "R106") (pin "1") (pinfunction "1_1") (pintype "passive"))
      (node (ref "R107") (pin "1") (pinfunction "1_1") (pintype "passive"))
      (node (ref "R108") (pin "2") (pinfunction "2_2") (pintype "passive"))
      (node (ref "R110") (pin "2") (pinfunction "2_2") (pintype "passive"))
      (node (ref "R113") (pin "1") (pinfunction "1_1") (pintype "passive"))
      (node (ref "R115") (pin "1") (pinfunction "1_1") (pintype "passive"))
      (node (ref "R125") (pin "1") (pinfunction "1_1") (pintype "passive"))
      (node (ref "R127") (pin "1") (pinfunction "1_1") (pintype "passive"))
      (node (ref "R129") (pin "1") (pinfunction "1_1") (pintype "passive"))
      (node (ref "R131") (pin "1") (pinfunction "1_1") (pintype "passive"))
      (node (ref "R135") (pin "1") (pinfunction "1_1") (pintype "passive"))
      (node (ref "R14") (pin "2") (pinfunction "2_2") (pintype "passive"))
      (node (ref "R143") (pin "1") (pinfunction "1_1") (pintype "passive"))
      (node (ref "R150") (pin "2") (pinfunction "2_2") (pintype "passive"))
      (node (ref "R158") (pin "2") (pinfunction "2_2") (pintype "passive"))
      (node (ref "R16") (pin "1") (pinfunction "1_1") (pintype "passive"))
      (node (ref "R17") (pin "1") (pinfunction "1_1") (pintype "passive"))
      (node (ref "R21") (pin "2") (pinfunction "2_2") (pintype "passive"))
      (node (ref "R22") (pin "2") (pinfunction "2_2") (pintype "passive"))
      (node (ref "R24") (pin "2") (pinfunction "2_2") (pintype "passive"))
      (node (ref "R25") (pin "2") (pinfunction "2_2") (pintype "passive"))
      (node (ref "R29") (pin "2") (pinfunction "2_2") (pintype "passive"))
      (node (ref "R31") (pin "2") (pinfunction "2_2") (pintype "passive"))
      (node (ref "R32") (pin "2") (pinfunction "2_2") (pintype "passive"))
      (node (ref "R33") (pin "2") (pinfunction "2_2") (pintype "passive"))
      (node (ref "R46") (pin "1") (pinfunction "1_1") (pintype "passive"))
      (node (ref "R47") (pin "1") (pinfunction "1_1") (pintype "passive"))
      (node (ref "R48") (pin "1") (pinfunction "1_1") (pintype "passive"))
      (node (ref "R50") (pin "2") (pinfunction "2_2") (pintype "passive"))
      (node (ref "R51") (pin "2") (pinfunction "2_2") (pintype "passive"))
      (node (ref "R52") (pin "2") (pinfunction "2_2") (pintype "passive"))
      (node (ref "R53") (pin "2") (pinfunction "2_2") (pintype "passive"))
      (node (ref "R59") (pin "1") (pinfunction "1_1") (pintype "passive"))
      (node (ref "R6") (pin "1") (pinfunction "1_1") (pintype "passive"))
      (node (ref "R61") (pin "1") (pinfunction "1_1") (pintype "passive"))
      (node (ref "R62") (pin "1") (pinfunction "1_1") (pintype "passive"))
      (node (ref "R63") (pin "1") (pinfunction "1_1") (pintype "passive"))
      (node (ref "R64") (pin "1") (pinfunction "1_1") (pintype "passive"))
      (node (ref "R8") (pin "2") (pinfunction "2_2") (pintype "passive"))
      (node (ref "R87") (pin "2") (pinfunction "2_2") (pintype "passive"))
      (node (ref "R88") (pin "2") (pinfunction "2_2") (pintype "passive"))
      (node (ref "R89") (pin "2") (pinfunction "2_2") (pintype "passive"))
      (node (ref "R91") (pin "2") (pinfunction "2_2") (pintype "passive"))
      (node (ref "R95") (pin "1") (pinfunction "1_1") (pintype "passive"))
      (node (ref "RST") (pin "1") (pinfunction "1_1") (pintype "passive"))
      (node (ref "S1.1") (pin "1") (pinfunction "1_1") (pintype "bidirectional"))
      (node (ref "S1.2") (pin "1") (pinfunction "1_1") (pintype "bidirectional"))
      (node (ref "SD") (pin "1") (pinfunction "1_1") (pintype "passive"))
      (node (ref "SIP") (pin "A1") (pinfunction "DGND1_A1") (pintype "bidirectional"))
      (node (ref "SIP") (pin "A18") (pinfunction "DGND2_A18") (pintype "bidirectional"))
      (node (ref "SIP") (pin "E19") (pinfunction "DGND3_E19") (pintype "bidirectional"))
      (node (ref "SIP") (pin "E20") (pinfunction "DGND4_E20") (pintype "bidirectional"))
      (node (ref "SIP") (pin "F19") (pinfunction "DGND6_F19") (pintype "bidirectional"))
      (node (ref "SIP") (pin "F8") (pinfunction "DGND5_F8") (pintype "bidirectional"))
      (node (ref "SIP") (pin "G11") (pinfunction "DGND9_G11") (pintype "bidirectional"))
      (node (ref "SIP") (pin "G12") (pinfunction "DGND10_G12") (pintype "bidirectional"))
      (node (ref "SIP") (pin "G19") (pinfunction "DGND11_G19") (pintype "bidirectional"))
      (node (ref "SIP") (pin "G8") (pinfunction "DGND7_G8") (pintype "bidirectional"))
      (node (ref "SIP") (pin "G9") (pinfunction "DGND8_G9") (pintype "bidirectional"))
      (node (ref "SIP") (pin "H10") (pinfunction "DGND16_H10") (pintype "bidirectional"))
      (node (ref "SIP") (pin "H12") (pinfunction "DGND17_H12") (pintype "bidirectional"))
      (node (ref "SIP") (pin "H19") (pinfunction "DGND18_H19") (pintype "bidirectional"))
      (node (ref "SIP") (pin "H6") (pinfunction "DGND12_H6") (pintype "bidirectional"))
      (node (ref "SIP") (pin "H7") (pinfunction "DGND13_H7") (pintype "bidirectional"))
      (node (ref "SIP") (pin "H8") (pinfunction "DGND14_H8") (pintype "bidirectional"))
      (node (ref "SIP") (pin "H9") (pinfunction "DGND15_H9") (pintype "bidirectional"))
      (node (ref "SIP") (pin "J10") (pinfunction "DGND23_J10") (pintype "bidirectional"))
      (node (ref "SIP") (pin "J11") (pinfunction "DGND24_J11") (pintype "bidirectional"))
      (node (ref "SIP") (pin "J19") (pinfunction "DGND25_J19") (pintype "bidirectional"))
      (node (ref "SIP") (pin "J20") (pinfunction "DGND26_J20") (pintype "bidirectional"))
      (node (ref "SIP") (pin "J6") (pinfunction "DGND19_J6") (pintype "bidirectional"))
      (node (ref "SIP") (pin "J7") (pinfunction "DGND20_J7") (pintype "bidirectional"))
      (node (ref "SIP") (pin "J8") (pinfunction "DGND21_J8") (pintype "bidirectional"))
      (node (ref "SIP") (pin "J9") (pinfunction "DGND22_J9") (pintype "bidirectional"))
      (node (ref "SIP") (pin "K10") (pinfunction "DGND29_K10") (pintype "bidirectional"))
      (node (ref "SIP") (pin "K11") (pinfunction "DGND30_K11") (pintype "bidirectional"))
      (node (ref "SIP") (pin "K19") (pinfunction "DGND31_K19") (pintype "bidirectional"))
      (node (ref "SIP") (pin "K7") (pinfunction "DGND27_K7") (pintype "bidirectional"))
      (node (ref "SIP") (pin "K9") (pinfunction "DGND28_K9") (pintype "bidirectional"))
      (node (ref "SIP") (pin "L10") (pinfunction "DGND32_L10") (pintype "bidirectional"))
      (node (ref "SIP") (pin "L11") (pinfunction "DGND33_L11") (pintype "bidirectional"))
      (node (ref "SIP") (pin "L12") (pinfunction "DGND34_L12") (pintype "bidirectional"))
      (node (ref "SIP") (pin "L13") (pinfunction "DGND35_L13") (pintype "bidirectional"))
      (node (ref "SIP") (pin "L19") (pinfunction "DGND36_L19") (pintype "bidirectional"))
      (node (ref "SIP") (pin "M10") (pinfunction "DGND42_M10") (pintype "bidirectional"))
      (node (ref "SIP") (pin "M12") (pinfunction "DGND43_M12") (pintype "bidirectional"))
      (node (ref "SIP") (pin "M14") (pinfunction "DGND44_M14") (pintype "bidirectional"))
      (node (ref "SIP") (pin "M19") (pinfunction "DGND45_M19") (pintype "bidirectional"))
      (node (ref "SIP") (pin "M6") (pinfunction "DGND38_M6") (pintype "bidirectional"))
      (node (ref "SIP") (pin "M7") (pinfunction "DGND39_M7") (pintype "bidirectional"))
      (node (ref "SIP") (pin "M8") (pinfunction "DGND40_M8") (pintype "bidirectional"))
      (node (ref "SIP") (pin "M9") (pinfunction "DGND41_M9") (pintype "bidirectional"))
      (node (ref "SIP") (pin "N10") (pinfunction "DGND47_N10") (pintype "bidirectional"))
      (node (ref "SIP") (pin "N11") (pinfunction "DGND48_N11") (pintype "bidirectional"))
      (node (ref "SIP") (pin "N14") (pinfunction "DGND49_N14") (pintype "bidirectional"))
      (node (ref "SIP") (pin "N19") (pinfunction "DGND50_N19") (pintype "bidirectional"))
      (node (ref "SIP") (pin "N20") (pinfunction "DGND51_N20") (pintype "bidirectional"))
      (node (ref "SIP") (pin "N7") (pinfunction "DGND46_N7") (pintype "bidirectional"))
      (node (ref "SIP") (pin "P19") (pinfunction "DGND52_P19") (pintype "bidirectional"))
      (node (ref "SIP") (pin "P20") (pinfunction "DGND53_P20") (pintype "bidirectional"))
      (node (ref "SIP") (pin "R19") (pinfunction "DGND54_R19") (pintype "bidirectional"))
      (node (ref "SIP") (pin "R20") (pinfunction "DGND55_R20") (pintype "bidirectional"))
      (node (ref "SIP") (pin "T19") (pinfunction "DGND56_T19") (pintype "bidirectional"))
      (node (ref "SIP") (pin "T20") (pinfunction "DGND57_T20") (pintype "bidirectional"))
      (node (ref "SIP") (pin "U19") (pinfunction "DGND58_U19") (pintype "bidirectional"))
      (node (ref "SIP") (pin "V1") (pinfunction "DGND59_V1") (pintype "bidirectional"))
      (node (ref "SIP") (pin "V18") (pinfunction "DGND60_V18") (pintype "bidirectional"))
      (node (ref "SIP") (pin "V19") (pinfunction "DGND61_V19") (pintype "bidirectional"))
      (node (ref "SIP") (pin "W10") (pinfunction "DGND70_W10") (pintype "bidirectional"))
      (node (ref "SIP") (pin "W11") (pinfunction "DGND71_W11") (pintype "bidirectional"))
      (node (ref "SIP") (pin "W12") (pinfunction "DGND72_W12") (pintype "bidirectional"))
      (node (ref "SIP") (pin "W13") (pinfunction "DGND73_W13") (pintype "bidirectional"))
      (node (ref "SIP") (pin "W14") (pinfunction "DGND74_W14") (pintype "bidirectional"))
      (node (ref "SIP") (pin "W15") (pinfunction "DGND75_W15") (pintype "bidirectional"))
      (node (ref "SIP") (pin "W16") (pinfunction "DGND76_W16") (pintype "bidirectional"))
      (node (ref "SIP") (pin "W17") (pinfunction "DGND77_W17") (pintype "bidirectional"))
      (node (ref "SIP") (pin "W18") (pinfunction "DGND78_W18") (pintype "bidirectional"))
      (node (ref "SIP") (pin "W19") (pinfunction "DGND79_W19") (pintype "bidirectional"))
      (node (ref "SIP") (pin "W2") (pinfunction "DGND62_W2") (pintype "bidirectional"))
      (node (ref "SIP") (pin "W20") (pinfunction "DGND80_W20") (pintype "bidirectional"))
      (node (ref "SIP") (pin "W3") (pinfunction "DGND63_W3") (pintype "bidirectional"))
      (node (ref "SIP") (pin "W5") (pinfunction "DGND65_W5") (pintype "bidirectional"))
      (node (ref "SIP") (pin "W6") (pinfunction "DGND66_W6") (pintype "bidirectional"))
      (node (ref "SIP") (pin "W7") (pinfunction "DGND67_W7") (pintype "bidirectional"))
      (node (ref "SIP") (pin "W8") (pinfunction "DGND68_W8") (pintype "bidirectional"))
      (node (ref "SIP") (pin "W9") (pinfunction "DGND69_W9") (pintype "bidirectional"))
      (node (ref "SIP") (pin "Y10") (pinfunction "DGND83_Y10") (pintype "bidirectional"))
      (node (ref "SIP") (pin "Y12") (pinfunction "DGND84_Y12") (pintype "bidirectional"))
      (node (ref "SIP") (pin "Y15") (pinfunction "DGND85_Y15") (pintype "bidirectional"))
      (node (ref "SIP") (pin "Y18") (pinfunction "DGND86_Y18") (pintype "bidirectional"))
      (node (ref "SIP") (pin "Y7") (pinfunction "DGND82_Y7") (pintype "bidirectional"))
      (node (ref "TP12") (pin "TP") (pinfunction "TP_TP") (pintype "input"))
      (node (ref "U1") (pin "2") (pinfunction "GND_2") (pintype "power_in"))
      (node (ref "U10") (pin "11") (pinfunction "GND_11") (pintype "bidirectional"))
      (node (ref "U10") (pin "TP") (pinfunction "TP_TP") (pintype "bidirectional"))
      (node (ref "U13") (pin "C4") (pinfunction "VSSQ1_C4") (pintype "bidirectional"))
      (node (ref "U13") (pin "E7") (pinfunction "VSS1_E7") (pintype "bidirectional"))
      (node (ref "U13") (pin "G5") (pinfunction "VSS2_G5") (pintype "bidirectional"))
      (node (ref "U13") (pin "H10") (pinfunction "VSS3_H10") (pintype "bidirectional"))
      (node (ref "U13") (pin "K8") (pinfunction "VSS4_K8") (pintype "bidirectional"))
      (node (ref "U13") (pin "N2") (pinfunction "VSSQ2_N2") (pintype "bidirectional"))
      (node (ref "U13") (pin "N5") (pinfunction "VSSQ3_N5") (pintype "bidirectional"))
      (node (ref "U13") (pin "P4") (pinfunction "VSSQ4_P4") (pintype "bidirectional"))
      (node (ref "U13") (pin "P6") (pinfunction "VSSQ5_P6") (pintype "bidirectional"))
      (node (ref "U2") (pin "3") (pinfunction "GND_3") (pintype "power_in"))
      (node (ref "U3") (pin "4") (pinfunction "GND_4") (pintype "bidirectional"))
      (node (ref "U4") (pin "4") (pinfunction "GND_4") (pintype "bidirectional"))
      (node (ref "U5") (pin "2") (pinfunction "VSS_2") (pintype "passive"))
      (node (ref "U6") (pin "3") (pinfunction "GND_3") (pintype "power_in"))
      (node (ref "U7") (pin "1") (pinfunction "GND1_1") (pintype "bidirectional"))
      (node (ref "U7") (pin "15") (pinfunction "GND4_15") (pintype "bidirectional"))
      (node (ref "U7") (pin "16") (pinfunction "GND5_16") (pintype "bidirectional"))
      (node (ref "U7") (pin "17") (pinfunction "GND6_17") (pintype "bidirectional"))
      (node (ref "U7") (pin "19") (pinfunction "GND7_19") (pintype "bidirectional"))
      (node (ref "U7") (pin "20") (pinfunction "GND8_20") (pintype "bidirectional"))
      (node (ref "U7") (pin "23") (pinfunction "GND9_23") (pintype "bidirectional"))
      (node (ref "U7") (pin "24") (pinfunction "GND10_24") (pintype "bidirectional"))
      (node (ref "U7") (pin "28") (pinfunction "GND11_28") (pintype "bidirectional"))
      (node (ref "U7") (pin "29") (pinfunction "GND12_29") (pintype "bidirectional"))
      (node (ref "U7") (pin "30") (pinfunction "GND13_30") (pintype "bidirectional"))
      (node (ref "U7") (pin "31") (pinfunction "GND14_31") (pintype "bidirectional"))
      (node (ref "U7") (pin "33") (pinfunction "GND15_33") (pintype "bidirectional"))
      (node (ref "U7") (pin "34") (pinfunction "GND16_34") (pintype "bidirectional"))
      (node (ref "U7") (pin "35") (pinfunction "GND17_35") (pintype "bidirectional"))
      (node (ref "U7") (pin "37") (pinfunction "GND18_37") (pintype "bidirectional"))
      (node (ref "U7") (pin "39") (pinfunction "GND19_39") (pintype "bidirectional"))
      (node (ref "U7") (pin "44") (pinfunction "GND20_44") (pintype "bidirectional"))
      (node (ref "U7") (pin "45") (pinfunction "GND21_45") (pintype "bidirectional"))
      (node (ref "U7") (pin "48") (pinfunction "GND22_48") (pintype "bidirectional"))
      (node (ref "U7") (pin "49") (pinfunction "GND23_49") (pintype "bidirectional"))
      (node (ref "U7") (pin "54") (pinfunction "GND24_54") (pintype "bidirectional"))
      (node (ref "U7") (pin "55") (pinfunction "GND25_55") (pintype "bidirectional"))
      (node (ref "U7") (pin "59") (pinfunction "GND26_59") (pintype "bidirectional"))
      (node (ref "U7") (pin "61") (pinfunction "GND27_61") (pintype "bidirectional"))
      (node (ref "U7") (pin "63") (pinfunction "GND28_63") (pintype "bidirectional"))
      (node (ref "U7") (pin "64") (pinfunction "GND29_64") (pintype "bidirectional"))
      (node (ref "U7") (pin "7") (pinfunction "GND2_7") (pintype "bidirectional"))
      (node (ref "U7") (pin "9") (pinfunction "GND3_9") (pintype "bidirectional"))
      (node (ref "U7") (pin "G1") (pinfunction "G1_G1") (pintype "bidirectional"))
      (node (ref "U7") (pin "G10") (pinfunction "G10_G10") (pintype "bidirectional"))
      (node (ref "U7") (pin "G11") (pinfunction "G11_G11") (pintype "bidirectional"))
      (node (ref "U7") (pin "G12") (pinfunction "G12_G12") (pintype "bidirectional"))
      (node (ref "U7") (pin "G13") (pinfunction "G13_G13") (pintype "bidirectional"))
      (node (ref "U7") (pin "G14") (pinfunction "G14_G14") (pintype "bidirectional"))
      (node (ref "U7") (pin "G15") (pinfunction "G15_G15") (pintype "bidirectional"))
      (node (ref "U7") (pin "G16") (pinfunction "G16_G16") (pintype "bidirectional"))
      (node (ref "U7") (pin "G17") (pinfunction "G17_G17") (pintype "bidirectional"))
      (node (ref "U7") (pin "G18") (pinfunction "G18_G18") (pintype "bidirectional"))
      (node (ref "U7") (pin "G19") (pinfunction "G19_G19") (pintype "bidirectional"))
      (node (ref "U7") (pin "G2") (pinfunction "G2_G2") (pintype "bidirectional"))
      (node (ref "U7") (pin "G20") (pinfunction "G20_G20") (pintype "bidirectional"))
      (node (ref "U7") (pin "G21") (pinfunction "G21_G21") (pintype "bidirectional"))
      (node (ref "U7") (pin "G22") (pinfunction "G22_G22") (pintype "bidirectional"))
      (node (ref "U7") (pin "G23") (pinfunction "G23_G23") (pintype "bidirectional"))
      (node (ref "U7") (pin "G24") (pinfunction "G24_G24") (pintype "bidirectional"))
      (node (ref "U7") (pin "G25") (pinfunction "G25_G25") (pintype "bidirectional"))
      (node (ref "U7") (pin "G26") (pinfunction "G26_G26") (pintype "bidirectional"))
      (node (ref "U7") (pin "G27") (pinfunction "G27_G27") (pintype "bidirectional"))
      (node (ref "U7") (pin "G28") (pinfunction "G28_G28") (pintype "bidirectional"))
      (node (ref "U7") (pin "G29") (pinfunction "G29_G29") (pintype "bidirectional"))
      (node (ref "U7") (pin "G3") (pinfunction "G3_G3") (pintype "bidirectional"))
      (node (ref "U7") (pin "G30") (pinfunction "G30_G30") (pintype "bidirectional"))
      (node (ref "U7") (pin "G31") (pinfunction "G31_G31") (pintype "bidirectional"))
      (node (ref "U7") (pin "G32") (pinfunction "G32_G32") (pintype "bidirectional"))
      (node (ref "U7") (pin "G33") (pinfunction "G33_G33") (pintype "bidirectional"))
      (node (ref "U7") (pin "G34") (pinfunction "G34_G34") (pintype "bidirectional"))
      (node (ref "U7") (pin "G35") (pinfunction "G35_G35") (pintype "bidirectional"))
      (node (ref "U7") (pin "G36") (pinfunction "G36_G36") (pintype "bidirectional"))
      (node (ref "U7") (pin "G4") (pinfunction "G4_G4") (pintype "bidirectional"))
      (node (ref "U7") (pin "G5") (pinfunction "G5_G5") (pintype "bidirectional"))
      (node (ref "U7") (pin "G6") (pinfunction "G6_G6") (pintype "bidirectional"))
      (node (ref "U7") (pin "G7") (pinfunction "G7_G7") (pintype "bidirectional"))
      (node (ref "U7") (pin "G8") (pinfunction "G8_G8") (pintype "bidirectional"))
      (node (ref "U7") (pin "G9") (pinfunction "G9_G9") (pintype "bidirectional"))
      (node (ref "U8") (pin "2") (pinfunction "GND_2") (pintype "power_in"))
      (node (ref "U9") (pin "11") (pinfunction "GND_11") (pintype "bidirectional"))
      (node (ref "U9") (pin "TP") (pinfunction "TP_TP") (pintype "bidirectional"))
      (node (ref "UT0") (pin "1") (pinfunction "1_1") (pintype "bidirectional"))
      (node (ref "UT1") (pin "1") (pinfunction "1_1") (pintype "bidirectional"))
      (node (ref "UT5") (pin "1") (pinfunction "1_1") (pintype "bidirectional"))
      (node (ref "X2") (pin "6") (pinfunction "VSS_6") (pintype "bidirectional"))
      (node (ref "X2") (pin "GND") (pinfunction "GND_GND") (pintype "bidirectional"))
      (node (ref "X4") (pin "GND") (pinfunction "GND_GND") (pintype "input"))
    )
    (net (code "40") (name "GNDA_ADC") (class "Default")
      (node (ref "C42") (pin "2") (pinfunction "2_2") (pintype "passive"))
      (node (ref "C43") (pin "2") (pinfunction "2_2") (pintype "passive"))
      (node (ref "C44") (pin "2") (pinfunction "2_2") (pintype "passive"))
      (node (ref "SIP") (pin "A6") (pinfunction "VSSA_ADC_0_A6") (pintype "bidirectional"))
      (node (ref "SIP") (pin "A9") (pinfunction "VSSA_ADC_1_A9") (pintype "bidirectional"))
      (node (ref "SIP") (pin "E8") (pinfunction "VSSA_ADC_2_E8") (pintype "bidirectional"))
    )
    (net (code "41") (name "GPIO1_17") (class "Default")
      (node (ref "GP0") (pin "4") (pinfunction "4_4") (pintype "bidirectional"))
      (node (ref "SIP") (pin "V14") (pinfunction "GPIO1_17_V14_V14") (pintype "bidirectional"))
    )
    (net (code "42") (name "GPIO1_25") (class "Default")
      (node (ref "GP0") (pin "3") (pinfunction "3_3") (pintype "bidirectional"))
      (node (ref "SIP") (pin "U16") (pinfunction "HDMIINT_GPIO1_25_U16_U16") (pintype "bidirectional"))
    )
    (net (code "43") (name "GPIO3_1") (class "Default")
      (node (ref "GP1") (pin "4") (pinfunction "4_4") (pintype "bidirectional"))
      (node (ref "SIP") (pin "H17") (pinfunction "H17_H17") (pintype "bidirectional"))
    )
    (net (code "44") (name "GPIO3_2") (class "Default")
      (node (ref "GP1") (pin "3") (pinfunction "3_3") (pintype "bidirectional"))
      (node (ref "SIP") (pin "J15") (pinfunction "J15_J15") (pintype "bidirectional"))
    )
    (net (code "45") (name "GPIO3_17") (class "Default")
      (node (ref "GP0") (pin "6") (pinfunction "6_6") (pintype "bidirectional"))
      (node (ref "SIP") (pin "C12") (pinfunction "SPI1_CS0_C12_C12") (pintype "bidirectional"))
    )
    (net (code "46") (name "GPIO3_20") (class "Default")
      (node (ref "GP0") (pin "5") (pinfunction "5_5") (pintype "bidirectional"))
      (node (ref "SIP") (pin "D13") (pinfunction "GPIO3_20_D13_D13") (pintype "bidirectional"))
    )
    (net (code "47") (name "I2C0_SCL") (class "Default")
      (node (ref "R23") (pin "1") (pinfunction "1_1") (pintype "passive"))
      (node (ref "SIP") (pin "C16") (pinfunction "I2C0_SCL_C16") (pintype "bidirectional"))
      (node (ref "SIP") (pin "C20") (pinfunction "PMIC_I2C_SCL_C20") (pintype "bidirectional"))
      (node (ref "U5") (pin "1") (pinfunction "SCL_1") (pintype "input"))
    )
    (net (code "48") (name "I2C0_SDA") (class "Default")
      (node (ref "R2") (pin "1") (pinfunction "1_1") (pintype "passive"))
      (node (ref "SIP") (pin "C17") (pinfunction "I2C0_SDA_C17") (pintype "bidirectional"))
      (node (ref "SIP") (pin "C19") (pinfunction "PMIC_I2C_SDA_C19") (pintype "bidirectional"))
      (node (ref "U5") (pin "3") (pinfunction "SDA_3") (pintype "bidirectional"))
    )
    (net (code "49") (name "I2C1_SCL") (class "Default")
      (node (ref "I2C") (pin "3") (pinfunction "3_3") (pintype "bidirectional"))
      (node (ref "R12") (pin "1") (pinfunction "1_1") (pintype "passive"))
      (node (ref "SIP") (pin "A16") (pinfunction "I2C1_SCL_A16_A16") (pintype "bidirectional"))
    )
    (net (code "50") (name "I2C1_SDA") (class "Default")
      (node (ref "I2C") (pin "4") (pinfunction "4_4") (pintype "bidirectional"))
      (node (ref "R13") (pin "2") (pinfunction "2_2") (pintype "passive"))
      (node (ref "SIP") (pin "B16") (pinfunction "I2C1_SDA_B16_B16") (pintype "bidirectional"))
    )
    (net (code "51") (name "I2C2_SCL") (class "Default")
      (node (ref "BMP") (pin "4") (pinfunction "SCK_4") (pintype "input"))
      (node (ref "IMU") (pin "23") (pinfunction "SCL/SCLK_23") (pintype "bidirectional"))
      (node (ref "R11") (pin "1") (pinfunction "1_1") (pintype "passive"))
      (node (ref "SIP") (pin "D17") (pinfunction "I2C2_SCL_D17_D17") (pintype "bidirectional"))
    )
    (net (code "52") (name "I2C2_SDA") (class "Default")
      (node (ref "BMP") (pin "3") (pinfunction "SDI_3") (pintype "bidirectional"))
      (node (ref "IMU") (pin "24") (pinfunction "SDA/SDI_24") (pintype "bidirectional"))
      (node (ref "R10") (pin "2") (pinfunction "2_2") (pintype "passive"))
      (node (ref "SIP") (pin "D18") (pinfunction "I2C2_SDA_D18_D18") (pintype "bidirectional"))
    )
    (net (code "53") (name "IMU_INT") (class "Default")
      (node (ref "IMU") (pin "12") (pinfunction "INT_12") (pintype "bidirectional"))
      (node (ref "SIP") (pin "A14") (pinfunction "GPIO3_21_A14_A14") (pintype "bidirectional"))
    )
    (net (code "54") (name "LDO_PGOOD") (class "Default")
      (node (ref "SIP") (pin "B20") (pinfunction "PMIC_OUT_LDO_PGOOD_B20") (pintype "output"))
      (node (ref "SIP") (pin "B5") (pinfunction "RTC_PWRONRSTN_B5") (pintype "bidirectional"))
    )
    (net (code "55") (name "LED_GRN") (class "Default")
      (node (ref "G") (pin "A") (pinfunction "A_A") (pintype "passive"))
      (node (ref "GP1") (pin "6") (pinfunction "6_6") (pintype "bidirectional"))
      (node (ref "SIP") (pin "T7") (pinfunction "TIMER7_T7_T7") (pintype "bidirectional"))
    )
    (net (code "56") (name "LED_RED") (class "Default")
      (node (ref "GP1") (pin "5") (pinfunction "5_5") (pintype "bidirectional"))
      (node (ref "R") (pin "A") (pinfunction "A_A") (pintype "passive"))
      (node (ref "SIP") (pin "R7") (pinfunction "TIMER4_R7_R7") (pintype "bidirectional"))
    )
    (net (code "57") (name "MCASP0_ACLKR") (class "Default")
      (node (ref "SIP") (pin "U18") (pinfunction "GPIO1_28_U18_U18") (pintype "bidirectional"))
      (node (ref "U10") (pin "20") (pinfunction "B1_20") (pintype "bidirectional"))
    )
    (net (code "58") (name "MCASP0_AXR0") (class "Default")
      (node (ref "SIP") (pin "T16") (pinfunction "USB1OC_GPIO1_26_T16_T16") (pintype "bidirectional"))
      (node (ref "U10") (pin "17") (pinfunction "B3_17") (pintype "bidirectional"))
    )
    (net (code "59") (name "MCASP0_AXR1") (class "Default")
      (node (ref "SIP") (pin "V17") (pinfunction "HDMIDIS_GPIO1_27_V17_V17") (pintype "bidirectional"))
      (node (ref "U10") (pin "16") (pinfunction "B4_16") (pintype "bidirectional"))
    )
    (net (code "60") (name "MCASP0_FSR") (class "Default")
      (node (ref "SIP") (pin "V12") (pinfunction "GPIO2_1_V12_V12") (pintype "bidirectional"))
      (node (ref "U10") (pin "18") (pinfunction "B2_18") (pintype "bidirectional"))
    )
    (net (code "61") (name "MDIR_1A") (class "Default")
      (node (ref "H1") (pin "21") (pinfunction "AIN1_21") (pintype "bidirectional"))
      (node (ref "SIP") (pin "T13") (pinfunction "GPIO2_0_T13_T13") (pintype "bidirectional"))
    )
    (net (code "62") (name "MDIR_1B") (class "Default")
      (node (ref "H1") (pin "22") (pinfunction "AIN2_22") (pintype "bidirectional"))
      (node (ref "SIP") (pin "U17") (pinfunction "UART4_TXD_U17_U17") (pintype "bidirectional"))
    )
    (net (code "63") (name "MDIR_2A") (class "Default")
      (node (ref "H1") (pin "17") (pinfunction "BIN1_17") (pintype "bidirectional"))
      (node (ref "SIP") (pin "R13") (pinfunction "GPIO1_16_R13_R13") (pintype "bidirectional"))
    )
    (net (code "64") (name "MDIR_2B") (class "Default")
      (node (ref "H1") (pin "16") (pinfunction "BIN2_16") (pintype "bidirectional"))
      (node (ref "R140") (pin "1") (pinfunction "1_1") (pintype "passive"))
      (node (ref "SIP") (pin "V4") (pinfunction "LCD_DATA14_V4_V4") (pintype "bidirectional"))
    )
    (net (code "65") (name "MDIR_3A") (class "Default")
      (node (ref "H2") (pin "21") (pinfunction "AIN1_21") (pintype "bidirectional"))
      (node (ref "R118") (pin "1") (pinfunction "1_1") (pintype "passive"))
      (node (ref "SIP") (pin "R4") (pinfunction "LCD_DATA3_R4_R4") (pintype "bidirectional"))
    )
    (net (code "66") (name "MDIR_3B") (class "Default")
      (node (ref "H2") (pin "22") (pinfunction "AIN2_22") (pintype "bidirectional"))
      (node (ref "R116") (pin "1") (pinfunction "1_1") (pintype "passive"))
      (node (ref "R77") (pin "1") (pinfunction "1_1") (pintype "passive"))
      (node (ref "SIP") (pin "R3") (pinfunction "LCD_DATA2_R3_R3") (pintype "bidirectional"))
    )
    (net (code "67") (name "MDIR_4A") (class "Default")
      (node (ref "H2") (pin "17") (pinfunction "BIN1_17") (pintype "bidirectional"))
      (node (ref "R113") (pin "2") (pinfunction "2_2") (pintype "passive"))
      (node (ref "SIP") (pin "R1") (pinfunction "LCD_DATA0_R1_R1") (pintype "bidirectional"))
    )
    (net (code "68") (name "MDIR_4B") (class "Default")
      (node (ref "H2") (pin "16") (pinfunction "BIN2_16") (pintype "bidirectional"))
      (node (ref "R115") (pin "2") (pinfunction "2_2") (pintype "passive"))
      (node (ref "SIP") (pin "R2") (pinfunction "LCD_DATA1_R2_R2") (pintype "bidirectional"))
    )
    (net (code "69") (name "MMC1_CLK") (class "Default")
      (node (ref "R15") (pin "2") (pinfunction "2_2") (pintype "passive"))
      (node (ref "R66") (pin "1") (pinfunction "1_1") (pintype "passive"))
      (node (ref "U13") (pin "M6") (pinfunction "CLK_M6") (pintype "bidirectional"))
    )
    (net (code "70") (name "MMC1_CMD") (class "Default")
      (node (ref "R67") (pin "1") (pinfunction "1_1") (pintype "passive"))
      (node (ref "SIP") (pin "V9") (pinfunction "MMC1_CMD_V9_V9") (pintype "bidirectional"))
      (node (ref "U13") (pin "M5") (pinfunction "CMD_M5") (pintype "bidirectional"))
    )
    (net (code "71") (name "MMC1_DAT0") (class "Default")
      (node (ref "R68") (pin "1") (pinfunction "1_1") (pintype "passive"))
      (node (ref "SIP") (pin "U7") (pinfunction "MMC1_DAT0_U7_U7") (pintype "bidirectional"))
      (node (ref "U13") (pin "A3") (pinfunction "DAT0_A3") (pintype "bidirectional"))
    )
    (net (code "72") (name "MMC1_DAT1") (class "Default")
      (node (ref "R69") (pin "1") (pinfunction "1_1") (pintype "passive"))
      (node (ref "SIP") (pin "V7") (pinfunction "MMC1_DAT1_V7_V7") (pintype "bidirectional"))
      (node (ref "U13") (pin "A4") (pinfunction "DAT1_A4") (pintype "bidirectional"))
    )
    (net (code "73") (name "MMC1_DAT2") (class "Default")
      (node (ref "R70") (pin "1") (pinfunction "1_1") (pintype "passive"))
      (node (ref "SIP") (pin "R8") (pinfunction "MMC1_DAT2_R8_R8") (pintype "bidirectional"))
      (node (ref "U13") (pin "A5") (pinfunction "DAT2_A5") (pintype "bidirectional"))
    )
    (net (code "74") (name "MMC1_DAT3") (class "Default")
      (node (ref "R71") (pin "1") (pinfunction "1_1") (pintype "passive"))
      (node (ref "SIP") (pin "T8") (pinfunction "MMC1_DAT3_T8_T8") (pintype "bidirectional"))
      (node (ref "U13") (pin "B2") (pinfunction "DAT3_B2") (pintype "bidirectional"))
    )
    (net (code "75") (name "MMC1_DAT4") (class "Default")
      (node (ref "R72") (pin "1") (pinfunction "1_1") (pintype "passive"))
      (node (ref "SIP") (pin "U8") (pinfunction "MMC1_DAT4_U8_U8") (pintype "bidirectional"))
      (node (ref "U13") (pin "B3") (pinfunction "DAT4_B3") (pintype "bidirectional"))
    )
    (net (code "76") (name "MMC1_DAT5") (class "Default")
      (node (ref "R73") (pin "1") (pinfunction "1_1") (pintype "passive"))
      (node (ref "SIP") (pin "V8") (pinfunction "MMC1_DAT5_V8_V8") (pintype "bidirectional"))
      (node (ref "U13") (pin "B4") (pinfunction "DAT5_B4") (pintype "bidirectional"))
    )
    (net (code "77") (name "MMC1_DAT6") (class "Default")
      (node (ref "R74") (pin "1") (pinfunction "1_1") (pintype "passive"))
      (node (ref "SIP") (pin "R9") (pinfunction "MMC1_DAT6_R9_R9") (pintype "bidirectional"))
      (node (ref "U13") (pin "B5") (pinfunction "DAT6_B5") (pintype "bidirectional"))
    )
    (net (code "78") (name "MMC1_DAT7") (class "Default")
      (node (ref "R75") (pin "1") (pinfunction "1_1") (pintype "passive"))
      (node (ref "SIP") (pin "T9") (pinfunction "MMC1_DAT7_T9_T9") (pintype "bidirectional"))
      (node (ref "U13") (pin "B6") (pinfunction "DAT7_B6") (pintype "bidirectional"))
    )
    (net (code "79") (name "MMC2_CLK") (class "Default")
      (node (ref "R76") (pin "1") (pinfunction "1_1") (pintype "passive"))
      (node (ref "U9") (pin "13") (pinfunction "B7_13") (pintype "bidirectional"))
    )
    (net (code "80") (name "MMC2_CMD") (class "Default")
      (node (ref "SIP") (pin "J16") (pinfunction "J16_J16") (pintype "bidirectional"))
      (node (ref "U9") (pin "12") (pinfunction "B8_12") (pintype "bidirectional"))
    )
    (net (code "81") (name "MMC2_DAT0") (class "Default")
      (node (ref "SIP") (pin "J17") (pinfunction "J17_J17") (pintype "bidirectional"))
      (node (ref "U9") (pin "14") (pinfunction "B6_14") (pintype "bidirectional"))
    )
    (net (code "82") (name "MMC2_DAT1") (class "Default")
      (node (ref "SIP") (pin "J18") (pinfunction "J18_J18") (pintype "bidirectional"))
      (node (ref "U9") (pin "15") (pinfunction "B5_15") (pintype "bidirectional"))
    )
    (net (code "83") (name "MMC2_DAT2") (class "Default")
      (node (ref "SIP") (pin "K15") (pinfunction "K15_K15") (pintype "bidirectional"))
      (node (ref "U9") (pin "16") (pinfunction "B4_16") (pintype "bidirectional"))
    )
    (net (code "84") (name "MMC2_DAT3") (class "Default")
      (node (ref "SIP") (pin "H16") (pinfunction "H16_H16") (pintype "bidirectional"))
      (node (ref "U9") (pin "17") (pinfunction "B3_17") (pintype "bidirectional"))
    )
    (net (code "85") (name "MODE_BTN") (class "Default")
      (node (ref "MOD") (pin "2") (pinfunction "2_2") (pintype "passive"))
      (node (ref "SIP") (pin "U6") (pinfunction "TIMER6_U6_U6") (pintype "bidirectional"))
    )
    (net (code "86") (name "MOT_STBY") (class "Default")
      (node (ref "H1") (pin "19") (pinfunction "STBY_19") (pintype "bidirectional"))
      (node (ref "H2") (pin "19") (pinfunction "STBY_19") (pintype "bidirectional"))
      (node (ref "SIP") (pin "D14") (pinfunction "GPIO0_20_D14_D14") (pintype "bidirectional"))
    )
    (net (code "87") (name "Net-(0-PadC)") (class "Default")
      (node (ref "0") (pin "C") (pinfunction "C_C") (pintype "passive"))
      (node (ref "R61") (pin "2") (pinfunction "2_2") (pintype "passive"))
    )
    (net (code "88") (name "Net-(1-PadC)") (class "Default")
      (node (ref "1") (pin "C") (pinfunction "C_C") (pintype "passive"))
      (node (ref "R62") (pin "2") (pinfunction "2_2") (pintype "passive"))
    )
    (net (code "89") (name "Net-(2-PadC)") (class "Default")
      (node (ref "2") (pin "C") (pinfunction "C_C") (pintype "passive"))
      (node (ref "R63") (pin "2") (pinfunction "2_2") (pintype "passive"))
    )
    (net (code "90") (name "Net-(3-PadC)") (class "Default")
      (node (ref "3") (pin "C") (pinfunction "C_C") (pintype "passive"))
      (node (ref "R64") (pin "2") (pinfunction "2_2") (pintype "passive"))
    )
    (net (code "91") (name "Net-(5VREG-OUT)") (class "Default")
      (node (ref "5VREG") (pin "2") (pinfunction "OUT_2") (pintype "power_in"))
      (node (ref "D1") (pin "C") (pinfunction "C_C") (pintype "passive"))
      (node (ref "L1") (pin "1") (pinfunction "1_1") (pintype "passive"))
    )
    (net (code "92") (name "Net-(5VREG-VIN)") (class "Default")
      (node (ref "5VREG") (pin "1") (pinfunction "VIN_1") (pintype "input"))
      (node (ref "C3") (pin "1") (pinfunction "1_1") (pintype "passive"))
      (node (ref "D2") (pin "C") (pinfunction "C_C") (pintype "passive"))
      (node (ref "D3") (pin "C") (pinfunction "C_C") (pintype "passive"))
    )
    (net (code "93") (name "Net-(6VREG-BS)") (class "Default")
      (node (ref "6VREG") (pin "2") (pinfunction "BS_2") (pintype "bidirectional"))
      (node (ref "C22") (pin "1") (pinfunction "1_1") (pintype "passive"))
    )
    (net (code "94") (name "Net-(6VREG-COMP)") (class "Default")
      (node (ref "6VREG") (pin "5") (pinfunction "COMP_5") (pintype "bidirectional"))
      (node (ref "R45") (pin "2") (pinfunction "2_2") (pintype "passive"))
    )
    (net (code "95") (name "Net-(6VREG-FB)") (class "Default")
      (node (ref "6VREG") (pin "6") (pinfunction "FB_6") (pintype "bidirectional"))
      (node (ref "R48") (pin "2") (pinfunction "2_2") (pintype "passive"))
      (node (ref "R49") (pin "1") (pinfunction "1_1") (pintype "passive"))
    )
    (net (code "96") (name "Net-(6VREG-FSW)") (class "Default")
      (node (ref "6VREG") (pin "4") (pinfunction "FSW_4") (pintype "bidirectional"))
      (node (ref "R47") (pin "2") (pinfunction "2_2") (pintype "passive"))
    )
    (net (code "97") (name "Net-(6VREG-LX)") (class "Default")
      (node (ref "6VREG") (pin "1") (pinfunction "LX_1") (pintype "bidirectional"))
      (node (ref "C22") (pin "2") (pinfunction "2_2") (pintype "passive"))
      (node (ref "D9") (pin "C") (pinfunction "C_C") (pintype "passive"))
      (node (ref "L3") (pin "1") (pinfunction "1_1") (pintype "passive"))
    )
    (net (code "98") (name "Net-(6VREG-SS)") (class "Default")
      (node (ref "6VREG") (pin "7") (pinfunction "SS_7") (pintype "bidirectional"))
      (node (ref "C21") (pin "2") (pinfunction "2_2") (pintype "passive"))
    )
    (net (code "99") (name "Net-(ANT1-PadSIG)") (class "Default")
      (node (ref "ANT1") (pin "SIG") (pinfunction "SIG_SIG") (pintype "bidirectional"))
      (node (ref "C48") (pin "1") (pinfunction "1_1") (pintype "passive"))
    )
    (net (code "100") (name "Net-(ANT2-PadSIG)") (class "Default")
      (node (ref "ANT2") (pin "SIG") (pinfunction "SIG_SIG") (pintype "bidirectional"))
      (node (ref "C58") (pin "1") (pinfunction "1_1") (pintype "passive"))
    )
    (net (code "101") (name "Net-(B0-PadC)") (class "Default")
      (node (ref "B0") (pin "C") (pinfunction "C_C") (pintype "passive"))
      (node (ref "R31") (pin "1") (pinfunction "1_1") (pintype "passive"))
    )
    (net (code "102") (name "Net-(B1-PadC)") (class "Default")
      (node (ref "B1") (pin "C") (pinfunction "C_C") (pintype "passive"))
      (node (ref "R29") (pin "1") (pinfunction "1_1") (pintype "passive"))
    )
    (net (code "103") (name "Net-(B2-PadC)") (class "Default")
      (node (ref "B2") (pin "C") (pinfunction "C_C") (pintype "passive"))
      (node (ref "R33") (pin "1") (pinfunction "1_1") (pintype "passive"))
    )
    (net (code "104") (name "Net-(B3-PadC)") (class "Default")
      (node (ref "B3") (pin "C") (pinfunction "C_C") (pintype "passive"))
      (node (ref "R32") (pin "1") (pinfunction "1_1") (pintype "passive"))
    )
    (net (code "105") (name "Net-(BAL-CD)") (class "Default")
      (node (ref "BAL") (pin "4") (pinfunction "CD_4") (pintype "bidirectional"))
      (node (ref "C19") (pin "1") (pinfunction "1_1") (pintype "passive"))
    )
    (net (code "106") (name "Net-(BAL-OUT)") (class "Default")
      (node (ref "BAL") (pin "8") (pinfunction "OUT_8") (pintype "bidirectional"))
      (node (ref "R7") (pin "1") (pinfunction "1_1") (pintype "passive"))
    )
    (net (code "107") (name "Net-(BAL-VC1)") (class "Default")
      (node (ref "BAL") (pin "2") (pinfunction "VC1_2") (pintype "bidirectional"))
      (node (ref "C17") (pin "1") (pinfunction "1_1") (pintype "passive"))
      (node (ref "C18") (pin "2") (pinfunction "2_2") (pintype "passive"))
      (node (ref "R30") (pin "2") (pinfunction "2_2") (pintype "passive"))
    )
    (net (code "108") (name "Net-(BAL-VC1_CB)") (class "Default")
      (node (ref "BAL") (pin "3") (pinfunction "VC1_CB_3") (pintype "bidirectional"))
      (node (ref "R27") (pin "2") (pinfunction "2_2") (pintype "passive"))
    )
    (net (code "109") (name "Net-(BAL-VC2)") (class "Default")
      (node (ref "BAL") (pin "1") (pinfunction "VC2_1") (pintype "bidirectional"))
      (node (ref "C17") (pin "2") (pinfunction "2_2") (pintype "passive"))
      (node (ref "R28") (pin "2") (pinfunction "2_2") (pintype "passive"))
    )
    (net (code "110") (name "Net-(BAL-VDD)") (class "Default")
      (node (ref "BAL") (pin "7") (pinfunction "VDD_7") (pintype "bidirectional"))
      (node (ref "C1") (pin "1") (pinfunction "1_1") (pintype "passive"))
      (node (ref "R34") (pin "2") (pinfunction "2_2") (pintype "passive"))
    )
    (net (code "111") (name "Net-(C23-Pad2)") (class "Default")
      (node (ref "C23") (pin "2") (pinfunction "2_2") (pintype "passive"))
      (node (ref "J2") (pin "P$10") (pinfunction "PWR_P$10") (pintype "bidirectional"))
      (node (ref "J2") (pin "P$11") (pinfunction "PWR_P$11") (pintype "bidirectional"))
      (node (ref "J2") (pin "P$12") (pinfunction "PWR_P$12") (pintype "bidirectional"))
      (node (ref "J2") (pin "P$21") (pinfunction "PWR_P$21") (pintype "bidirectional"))
      (node (ref "J2") (pin "P$22") (pinfunction "PWR_P$22") (pintype "bidirectional"))
      (node (ref "J2") (pin "P$7") (pinfunction "PWR_P$7") (pintype "bidirectional"))
      (node (ref "J2") (pin "P$8") (pinfunction "PWR_P$8") (pintype "bidirectional"))
      (node (ref "J2") (pin "P$9") (pinfunction "PWR_P$9") (pintype "bidirectional"))
      (node (ref "L3") (pin "2") (pinfunction "2_2") (pintype "passive"))
      (node (ref "R49") (pin "2") (pinfunction "2_2") (pintype "passive"))
    )
    (net (code "112") (name "Net-(C24-Pad2)") (class "Default")
      (node (ref "C24") (pin "2") (pinfunction "2_2") (pintype "passive"))
      (node (ref "R45") (pin "1") (pinfunction "1_1") (pintype "passive"))
    )
    (net (code "113") (name "Net-(CHG-PadC)") (class "Default")
      (node (ref "CHG") (pin "C") (pinfunction "C_C") (pintype "passive"))
      (node (ref "R3") (pin "2") (pinfunction "2_2") (pintype "passive"))
    )
    (net (code "114") (name "Net-(CHGIC-BST)") (class "Default")
      (node (ref "C14") (pin "1") (pinfunction "1_1") (pintype "passive"))
      (node (ref "CHGIC") (pin "15") (pinfunction "BST_15") (pintype "bidirectional"))
    )
    (net (code "115") (name "Net-(CHGIC-CHGOK)") (class "Default")
      (node (ref "CHGIC") (pin "11") (pinfunction "CHGOK_11") (pintype "bidirectional"))
      (node (ref "R3") (pin "1") (pinfunction "1_1") (pintype "passive"))
    )
    (net (code "116") (name "Net-(CHGIC-CSP)") (class "Default")
      (node (ref "CHGIC") (pin "10") (pinfunction "CSP_10") (pintype "bidirectional"))
      (node (ref "L2") (pin "2") (pinfunction "2_2") (pintype "passive"))
      (node (ref "R4") (pin "2") (pinfunction "2_2") (pintype "passive"))
    )
    (net (code "117") (name "Net-(CHGIC-NTC)") (class "Default")
      (node (ref "CHGIC") (pin "13") (pinfunction "NTC_13") (pintype "bidirectional"))
      (node (ref "R5") (pin "1") (pinfunction "1_1") (pintype "passive"))
      (node (ref "R6") (pin "2") (pinfunction "2_2") (pintype "passive"))
    )
    (net (code "118") (name "Net-(CHGIC-SW)") (class "Default")
      (node (ref "C14") (pin "2") (pinfunction "2_2") (pintype "passive"))
      (node (ref "CHGIC") (pin "1") (pinfunction "SW_1") (pintype "bidirectional"))
      (node (ref "L2") (pin "1") (pinfunction "1_1") (pintype "passive"))
    )
    (net (code "119") (name "Net-(CHGIC-TMR)") (class "Default")
      (node (ref "C10") (pin "2") (pinfunction "2_2") (pintype "passive"))
      (node (ref "CHGIC") (pin "14") (pinfunction "TMR_14") (pintype "bidirectional"))
    )
    (net (code "120") (name "Net-(G-PadC)") (class "Default")
      (node (ref "G") (pin "C") (pinfunction "C_C") (pintype "passive"))
      (node (ref "R22") (pin "1") (pinfunction "1_1") (pintype "passive"))
    )
    (net (code "121") (name "Net-(IMU-REGOUT)") (class "Default")
      (node (ref "C6") (pin "1") (pinfunction "1_1") (pintype "passive"))
      (node (ref "IMU") (pin "10") (pinfunction "REGOUT_10") (pintype "bidirectional"))
    )
    (net (code "122") (name "Net-(J2-1)") (class "Default")
      (node (ref "J2") (pin "P$1") (pinfunction "1_P$1") (pintype "bidirectional"))
      (node (ref "R36") (pin "2") (pinfunction "2_2") (pintype "passive"))
    )
    (net (code "123") (name "Net-(J2-2)") (class "Default")
      (node (ref "J2") (pin "P$2") (pinfunction "2_P$2") (pintype "bidirectional"))
      (node (ref "R37") (pin "2") (pinfunction "2_2") (pintype "passive"))
    )
    (net (code "124") (name "Net-(J2-3)") (class "Default")
      (node (ref "J2") (pin "P$3") (pinfunction "3_P$3") (pintype "bidirectional"))
      (node (ref "R38") (pin "2") (pinfunction "2_2") (pintype "passive"))
    )
    (net (code "125") (name "Net-(J2-4)") (class "Default")
      (node (ref "J2") (pin "P$4") (pinfunction "4_P$4") (pintype "bidirectional"))
      (node (ref "R39") (pin "2") (pinfunction "2_2") (pintype "passive"))
    )
    (net (code "126") (name "Net-(J2-5)") (class "Default")
      (node (ref "J2") (pin "P$5") (pinfunction "5_P$5") (pintype "bidirectional"))
      (node (ref "R40") (pin "2") (pinfunction "2_2") (pintype "passive"))
    )
    (net (code "127") (name "Net-(J2-6)") (class "Default")
      (node (ref "J2") (pin "P$6") (pinfunction "6_P$6") (pintype "bidirectional"))
      (node (ref "R41") (pin "2") (pinfunction "2_2") (pintype "passive"))
    )
    (net (code "128") (name "Net-(J2-7)") (class "Default")
      (node (ref "J2") (pin "P$19") (pinfunction "7_P$19") (pintype "bidirectional"))
      (node (ref "R42") (pin "2") (pinfunction "2_2") (pintype "passive"))
    )
    (net (code "129") (name "Net-(J2-8)") (class "Default")
      (node (ref "J2") (pin "P$20") (pinfunction "8_P$20") (pintype "bidirectional"))
      (node (ref "R43") (pin "2") (pinfunction "2_2") (pintype "passive"))
    )
    (net (code "130") (name "Net-(M1-1)") (class "Default")
      (node (ref "H1") (pin "5") (pinfunction "A02_5") (pintype "bidirectional"))
      (node (ref "H1") (pin "6") (pinfunction "A02_6") (pintype "bidirectional"))
      (node (ref "M1") (pin "P$1") (pinfunction "1_P$1") (pintype "bidirectional"))
    )
    (net (code "131") (name "Net-(M1-2)") (class "Default")
      (node (ref "H1") (pin "1") (pinfunction "A01_1") (pintype "bidirectional"))
      (node (ref "H1") (pin "2") (pinfunction "A01_2") (pintype "bidirectional"))
      (node (ref "M1") (pin "P$2") (pinfunction "2_P$2") (pintype "bidirectional"))
    )
    (net (code "132") (name "Net-(M2-1)") (class "Default")
      (node (ref "H1") (pin "11") (pinfunction "B01_11") (pintype "bidirectional"))
      (node (ref "H1") (pin "12") (pinfunction "B01_12") (pintype "bidirectional"))
      (node (ref "M2") (pin "P$1") (pinfunction "1_P$1") (pintype "bidirectional"))
    )
    (net (code "133") (name "Net-(M2-2)") (class "Default")
      (node (ref "H1") (pin "7") (pinfunction "B02_7") (pintype "bidirectional"))
      (node (ref "H1") (pin "8") (pinfunction "B02_8") (pintype "bidirectional"))
      (node (ref "M2") (pin "P$2") (pinfunction "2_P$2") (pintype "bidirectional"))
    )
    (net (code "134") (name "Net-(M3-1)") (class "Default")
      (node (ref "H2") (pin "1") (pinfunction "A01_1") (pintype "bidirectional"))
      (node (ref "H2") (pin "2") (pinfunction "A01_2") (pintype "bidirectional"))
      (node (ref "M3") (pin "P$1") (pinfunction "1_P$1") (pintype "bidirectional"))
    )
    (net (code "135") (name "Net-(M3-2)") (class "Default")
      (node (ref "H2") (pin "5") (pinfunction "A02_5") (pintype "bidirectional"))
      (node (ref "H2") (pin "6") (pinfunction "A02_6") (pintype "bidirectional"))
      (node (ref "M3") (pin "P$2") (pinfunction "2_P$2") (pintype "bidirectional"))
    )
    (net (code "136") (name "Net-(M4-1)") (class "Default")
      (node (ref "H2") (pin "7") (pinfunction "B02_7") (pintype "bidirectional"))
      (node (ref "H2") (pin "8") (pinfunction "B02_8") (pintype "bidirectional"))
      (node (ref "M4") (pin "P$1") (pinfunction "1_P$1") (pintype "bidirectional"))
    )
    (net (code "137") (name "Net-(M4-2)") (class "Default")
      (node (ref "H2") (pin "11") (pinfunction "B01_11") (pintype "bidirectional"))
      (node (ref "H2") (pin "12") (pinfunction "B01_12") (pintype "bidirectional"))
      (node (ref "M4") (pin "P$2") (pinfunction "2_P$2") (pintype "bidirectional"))
    )
    (net (code "138") (name "Net-(OSC1-EN)") (class "Default")
      (node (ref "OSC1") (pin "1") (pinfunction "EN_1") (pintype "bidirectional"))
      (node (ref "R90") (pin "1") (pinfunction "1_1") (pintype "passive"))
    )
    (net (code "139") (name "Net-(PROT-VDD)") (class "Default")
      (node (ref "C15") (pin "2") (pinfunction "2_2") (pintype "passive"))
      (node (ref "PROT") (pin "5") (pinfunction "VDD_5") (pintype "bidirectional"))
      (node (ref "R44") (pin "2") (pinfunction "2_2") (pintype "passive"))
    )
    (net (code "140") (name "Net-(R-PadC)") (class "Default")
      (node (ref "R") (pin "C") (pinfunction "C_C") (pintype "passive"))
      (node (ref "R21") (pin "1") (pinfunction "1_1") (pintype "passive"))
    )
    (net (code "141") (name "Net-(R76-Pad2)") (class "Default")
      (node (ref "R76") (pin "2") (pinfunction "2_2") (pintype "passive"))
      (node (ref "SIP") (pin "L15") (pinfunction "L15_L15") (pintype "bidirectional"))
    )
    (net (code "142") (name "Net-(R91-Pad1)") (class "Default")
      (node (ref "R91") (pin "1") (pinfunction "1_1") (pintype "passive"))
      (node (ref "WIFI") (pin "C") (pinfunction "C_C") (pintype "passive"))
    )
    (net (code "143") (name "Net-(SIPA-PMIC_IN_PWR_EN)") (class "Default")
      (node (ref "SIP") (pin "C6") (pinfunction "PMIC_POWER_EN_C6") (pintype "output"))
      (node (ref "SIP") (pin "D19") (pinfunction "PMIC_IN_PWR_EN_D19") (pintype "input"))
      (node (ref "TP5") (pin "TP") (pinfunction "TP_TP") (pintype "input"))
    )
    (net (code "144") (name "Net-(SIPB-JTAG_EMU0)") (class "Default")
      (node (ref "EMU1") (pin "TP") (pinfunction "TP_TP") (pintype "input"))
      (node (ref "SIP") (pin "C14") (pinfunction "JTAG_EMU0_C14") (pintype "bidirectional"))
    )
    (net (code "145") (name "Net-(SIPB-JTAG_EMU1)") (class "Default")
      (node (ref "EMU0") (pin "TP") (pinfunction "TP_TP") (pintype "input"))
      (node (ref "SIP") (pin "B14") (pinfunction "JTAG_EMU1_B14") (pintype "bidirectional"))
    )
    (net (code "146") (name "Net-(SIPB-JTAG_TCK)") (class "Default")
      (node (ref "SIP") (pin "A12") (pinfunction "JTAG_TCK_A12") (pintype "bidirectional"))
      (node (ref "TCK") (pin "TP") (pinfunction "TP_TP") (pintype "input"))
    )
    (net (code "147") (name "Net-(SIPB-JTAG_TDI)") (class "Default")
      (node (ref "SIP") (pin "B11") (pinfunction "JTAG_TDI_B11") (pintype "bidirectional"))
      (node (ref "TDI") (pin "TP") (pinfunction "TP_TP") (pintype "input"))
    )
    (net (code "148") (name "Net-(SIPB-JTAG_TDO)") (class "Default")
      (node (ref "SIP") (pin "A11") (pinfunction "JTAG_TDO_A11") (pintype "bidirectional"))
      (node (ref "TDO") (pin "TP") (pinfunction "TP_TP") (pintype "input"))
    )
    (net (code "149") (name "Net-(SIPB-JTAG_TMS)") (class "Default")
      (node (ref "SIP") (pin "C11") (pinfunction "JTAG_TMS_C11") (pintype "bidirectional"))
      (node (ref "TMS") (pin "TP") (pinfunction "TP_TP") (pintype "input"))
    )
    (net (code "150") (name "Net-(SIPB-JTAG_TRSTN)") (class "Default")
      (node (ref "R59") (pin "2") (pinfunction "2_2") (pintype "passive"))
      (node (ref "SIP") (pin "B10") (pinfunction "JTAG_TRSTN_B10") (pintype "bidirectional"))
      (node (ref "TRSTN") (pin "TP") (pinfunction "TP_TP") (pintype "input"))
    )
    (net (code "151") (name "Net-(SIPB-MMC0_CD_C15)") (class "Default")
      (node (ref "R65") (pin "1") (pinfunction "1_1") (pintype "passive"))
      (node (ref "SIP") (pin "C15") (pinfunction "MMC0_CD_C15_C15") (pintype "bidirectional"))
      (node (ref "X2") (pin "CD") (pinfunction "CD#_CD") (pintype "bidirectional"))
    )
    (net (code "152") (name "Net-(SIPB-MMC0_CLK_G17)") (class "Default")
      (node (ref "R57") (pin "1") (pinfunction "1_1") (pintype "passive"))
      (node (ref "SIP") (pin "G17") (pinfunction "MMC0_CLK_G17_G17") (pintype "bidirectional"))
      (node (ref "X2") (pin "5") (pinfunction "CLK_5") (pintype "bidirectional"))
    )
    (net (code "153") (name "Net-(SIPB-MMC0_CMD_G18)") (class "Default")
      (node (ref "R56") (pin "1") (pinfunction "1_1") (pintype "passive"))
      (node (ref "SIP") (pin "G18") (pinfunction "MMC0_CMD_G18_G18") (pintype "bidirectional"))
      (node (ref "X2") (pin "3") (pinfunction "CMD/DI_3") (pintype "bidirectional"))
    )
    (net (code "154") (name "Net-(SIPB-MMC0_DAT0_G16)") (class "Default")
      (node (ref "R55") (pin "1") (pinfunction "1_1") (pintype "passive"))
      (node (ref "SIP") (pin "G16") (pinfunction "MMC0_DAT0_G16_G16") (pintype "bidirectional"))
      (node (ref "X2") (pin "7") (pinfunction "DAT0/DO_7") (pintype "bidirectional"))
    )
    (net (code "155") (name "Net-(SIPB-MMC0_DAT1_G15)") (class "Default")
      (node (ref "R54") (pin "1") (pinfunction "1_1") (pintype "passive"))
      (node (ref "SIP") (pin "G15") (pinfunction "MMC0_DAT1_G15_G15") (pintype "bidirectional"))
      (node (ref "X2") (pin "8") (pinfunction "DAT1_8") (pintype "bidirectional"))
    )
    (net (code "156") (name "Net-(SIPB-MMC0_DAT2_F18)") (class "Default")
      (node (ref "R35") (pin "1") (pinfunction "1_1") (pintype "passive"))
      (node (ref "SIP") (pin "F18") (pinfunction "MMC0_DAT2_F18_F18") (pintype "bidirectional"))
      (node (ref "X2") (pin "1") (pinfunction "DAT2_1") (pintype "bidirectional"))
    )
    (net (code "157") (name "Net-(SIPB-MMC0_DAT3_F17)") (class "Default")
      (node (ref "R26") (pin "1") (pinfunction "1_1") (pintype "passive"))
      (node (ref "SIP") (pin "F17") (pinfunction "MMC0_DAT3_F17_F17") (pintype "bidirectional"))
      (node (ref "X2") (pin "2") (pinfunction "DAT3/CS_2") (pintype "bidirectional"))
    )
    (net (code "158") (name "Net-(SIPB-MMC1_CLK_U9)") (class "Default")
      (node (ref "R15") (pin "1") (pinfunction "1_1") (pintype "passive"))
      (node (ref "SIP") (pin "U9") (pinfunction "MMC1_CLK_U9_U9") (pintype "bidirectional"))
    )
    (net (code "159") (name "Net-(SIPB-OSC0_GND)") (class "Default")
      (node (ref "C29") (pin "2") (pinfunction "2_2") (pintype "passive"))
      (node (ref "C30") (pin "2") (pinfunction "2_2") (pintype "passive"))
      (node (ref "SIP") (pin "L20") (pinfunction "OSC0_GND_L20") (pintype "bidirectional"))
    )
    (net (code "160") (name "Net-(SIPB-OSC0_IN)") (class "Default")
      (node (ref "C30") (pin "1") (pinfunction "1_1") (pintype "passive"))
      (node (ref "R20") (pin "2") (pinfunction "2_2") (pintype "passive"))
      (node (ref "SIP") (pin "M20") (pinfunction "OSC0_IN_M20") (pintype "bidirectional"))
      (node (ref "Y1") (pin "2") (pinfunction "P$2_2") (pintype "passive"))
    )
    (net (code "161") (name "Net-(SIPB-OSC0_OUT)") (class "Default")
      (node (ref "C29") (pin "1") (pinfunction "1_1") (pintype "passive"))
      (node (ref "R20") (pin "1") (pinfunction "1_1") (pintype "passive"))
      (node (ref "SIP") (pin "K20") (pinfunction "OSC0_OUT_K20") (pintype "bidirectional"))
      (node (ref "Y1") (pin "1") (pinfunction "P$1_1") (pintype "passive"))
    )
    (net (code "162") (name "Net-(SIPB-OSC1_GND)") (class "Default")
      (node (ref "C31") (pin "2") (pinfunction "2_2") (pintype "passive"))
      (node (ref "C32") (pin "1") (pinfunction "1_1") (pintype "passive"))
      (node (ref "SIP") (pin "G20") (pinfunction "OSC1_GND_G20") (pintype "bidirectional"))
    )
    (net (code "163") (name "Net-(SIPB-OSC1_IN)") (class "Default")
      (node (ref "C31") (pin "1") (pinfunction "1_1") (pintype "passive"))
      (node (ref "R18") (pin "2") (pinfunction "2_2") (pintype "passive"))
      (node (ref "SIP") (pin "H20") (pinfunction "OSC1_IN_H20") (pintype "bidirectional"))
      (node (ref "Y2") (pin "P$2") (pinfunction "P$2_P$2") (pintype "passive"))
    )
    (net (code "164") (name "Net-(SIPB-OSC1_OUT)") (class "Default")
      (node (ref "C32") (pin "2") (pinfunction "2_2") (pintype "passive"))
      (node (ref "R18") (pin "1") (pinfunction "1_1") (pintype "passive"))
      (node (ref "SIP") (pin "F20") (pinfunction "OSC1_OUT_F20") (pintype "bidirectional"))
      (node (ref "Y2") (pin "P$1") (pinfunction "P$1_P$1") (pintype "passive"))
    )
    (net (code "165") (name "Net-(SIPC-ADC_VREFP)") (class "Default")
      (node (ref "C42") (pin "1") (pinfunction "1_1") (pintype "passive"))
      (node (ref "C43") (pin "1") (pinfunction "1_1") (pintype "passive"))
      (node (ref "R111") (pin "2") (pinfunction "2_2") (pintype "passive"))
      (node (ref "SIP") (pin "B9") (pinfunction "ADC_VREFP_B9") (pintype "bidirectional"))
    )
    (net (code "166") (name "Net-(SIPC-AIN7)") (class "Default")
      (node (ref "R109") (pin "2") (pinfunction "2_2") (pintype "passive"))
      (node (ref "R110") (pin "1") (pinfunction "1_1") (pintype "passive"))
      (node (ref "SIP") (pin "C9") (pinfunction "AIN7_C9") (pintype "bidirectional"))
    )
    (net (code "167") (name "Net-(SIPC-LCD_DATA11_U4)") (class "Default")
      (node (ref "R135") (pin "2") (pinfunction "2_2") (pintype "passive"))
      (node (ref "SIP") (pin "U4") (pinfunction "LCD_DATA11_U4_U4") (pintype "bidirectional"))
    )
    (net (code "168") (name "Net-(SIPC-USB0_VBUS)") (class "Default")
      (node (ref "R149") (pin "1") (pinfunction "1_1") (pintype "passive"))
      (node (ref "SIP") (pin "P15") (pinfunction "USB0_VBUS_P15") (pintype "bidirectional"))
    )
    (net (code "169") (name "Net-(SIPC-USB1_ID)") (class "Default")
      (node (ref "R150") (pin "1") (pinfunction "1_1") (pintype "passive"))
      (node (ref "SIP") (pin "P17") (pinfunction "USB1_ID_P17") (pintype "bidirectional"))
    )
    (net (code "170") (name "Net-(SIPC-USB1_VBUS)") (class "Default")
      (node (ref "R156") (pin "1") (pinfunction "1_1") (pintype "passive"))
      (node (ref "SIP") (pin "T18") (pinfunction "USB1_VBUS_T18") (pintype "bidirectional"))
    )
    (net (code "171") (name "Net-(SIPE-RTC_KALDO_ENN)") (class "Default")
      (node (ref "R158") (pin "1") (pinfunction "1_1") (pintype "passive"))
      (node (ref "SIP") (pin "B4") (pinfunction "RTC_KALDO_ENN_B4") (pintype "bidirectional"))
    )
    (net (code "172") (name "Net-(U5-WP)") (class "Default")
      (node (ref "R58") (pin "1") (pinfunction "1_1") (pintype "passive"))
      (node (ref "U5") (pin "5") (pinfunction "WP_5") (pintype "input"))
      (node (ref "WP") (pin "P$1") (pinfunction "TP_P$1") (pintype "bidirectional"))
    )
    (net (code "173") (name "Net-(U7-BT_AUD_CLK)") (class "Default")
      (node (ref "R124") (pin "2") (pinfunction "2_2") (pintype "passive"))
      (node (ref "U7") (pin "60") (pinfunction "BT_AUD_CLK_60") (pintype "bidirectional"))
    )
    (net (code "174") (name "Net-(U7-BT_AUD_FSYNC)") (class "Default")
      (node (ref "R123") (pin "2") (pinfunction "2_2") (pintype "passive"))
      (node (ref "U7") (pin "58") (pinfunction "BT_AUD_FSYNC_58") (pintype "bidirectional"))
    )
    (net (code "175") (name "Net-(U7-BT_AUD_IN)") (class "Default")
      (node (ref "R97") (pin "2") (pinfunction "2_2") (pintype "passive"))
      (node (ref "U7") (pin "56") (pinfunction "BT_AUD_IN_56") (pintype "bidirectional"))
    )
    (net (code "176") (name "Net-(U7-BT_AUD_OUT)") (class "Default")
      (node (ref "R100") (pin "2") (pinfunction "2_2") (pintype "passive"))
      (node (ref "U7") (pin "57") (pinfunction "BT_AUD_OUT_57") (pintype "bidirectional"))
    )
    (net (code "177") (name "Net-(U7-BT_HCI_CTS)") (class "Default")
      (node (ref "R86") (pin "2") (pinfunction "2_2") (pintype "passive"))
      (node (ref "U7") (pin "51") (pinfunction "BT_HCI_CTS_51") (pintype "bidirectional"))
    )
    (net (code "178") (name "Net-(U7-BT_HCI_RTS)") (class "Default")
      (node (ref "R85") (pin "2") (pinfunction "2_2") (pintype "passive"))
      (node (ref "U7") (pin "50") (pinfunction "BT_HCI_RTS_50") (pintype "bidirectional"))
    )
    (net (code "179") (name "Net-(U7-BT_HCI_RX)") (class "Default")
      (node (ref "R96") (pin "2") (pinfunction "2_2") (pintype "passive"))
      (node (ref "U7") (pin "53") (pinfunction "BT_HCI_RX_53") (pintype "bidirectional"))
    )
    (net (code "180") (name "Net-(U7-BT_HCI_TX)") (class "Default")
      (node (ref "R92") (pin "2") (pinfunction "2_2") (pintype "passive"))
      (node (ref "U7") (pin "52") (pinfunction "BT_HCI_TX_52") (pintype "bidirectional"))
    )
    (net (code "181") (name "Net-(U7-RF_ANT1)") (class "Default")
      (node (ref "C48") (pin "2") (pinfunction "2_2") (pintype "passive"))
      (node (ref "U7") (pin "32") (pinfunction "RF_ANT1_32") (pintype "bidirectional"))
    )
    (net (code "182") (name "Net-(U7-RF_ANT2)") (class "Default")
      (node (ref "C58") (pin "2") (pinfunction "2_2") (pintype "passive"))
      (node (ref "U7") (pin "18") (pinfunction "RF_ANT2_18") (pintype "bidirectional"))
    )
    (net (code "183") (name "Net-(U7-WLAN_IRQ)") (class "Default")
      (node (ref "R84") (pin "2") (pinfunction "2_2") (pintype "passive"))
      (node (ref "R9") (pin "2") (pinfunction "2_2") (pintype "passive"))
      (node (ref "U7") (pin "14") (pinfunction "WLAN_IRQ_14") (pintype "bidirectional"))
    )
    (net (code "184") (name "Net-(U7-WL_SDIO_CLK)") (class "Default")
      (node (ref "R78") (pin "2") (pinfunction "2_2") (pintype "passive"))
      (node (ref "U7") (pin "8") (pinfunction "WL_SDIO_CLK_8") (pintype "bidirectional"))
    )
    (net (code "185") (name "Net-(U7-WL_SDIO_CMD)") (class "Default")
      (node (ref "R79") (pin "2") (pinfunction "2_2") (pintype "passive"))
      (node (ref "U7") (pin "6") (pinfunction "WL_SDIO_CMD_6") (pintype "bidirectional"))
    )
    (net (code "186") (name "Net-(U7-WL_SDIO_D0)") (class "Default")
      (node (ref "R80") (pin "2") (pinfunction "2_2") (pintype "passive"))
      (node (ref "U7") (pin "10") (pinfunction "WL_SDIO_D0_10") (pintype "bidirectional"))
    )
    (net (code "187") (name "Net-(U7-WL_SDIO_D1)") (class "Default")
      (node (ref "R81") (pin "2") (pinfunction "2_2") (pintype "passive"))
      (node (ref "U7") (pin "11") (pinfunction "WL_SDIO_D1_11") (pintype "bidirectional"))
    )
    (net (code "188") (name "Net-(U7-WL_SDIO_D2)") (class "Default")
      (node (ref "R82") (pin "2") (pinfunction "2_2") (pintype "passive"))
      (node (ref "U7") (pin "12") (pinfunction "WL_SDIO_D2_12") (pintype "bidirectional"))
    )
    (net (code "189") (name "Net-(U7-WL_SDIO_D3)") (class "Default")
      (node (ref "R83") (pin "2") (pinfunction "2_2") (pintype "passive"))
      (node (ref "U7") (pin "13") (pinfunction "WL_SDIO_D3_13") (pintype "bidirectional"))
    )
    (net (code "190") (name "Net-(U10-OE)") (class "Default")
      (node (ref "R106") (pin "2") (pinfunction "2_2") (pintype "passive"))
      (node (ref "R93") (pin "2") (pinfunction "2_2") (pintype "passive"))
      (node (ref "U10") (pin "10") (pinfunction "OE_10") (pintype "bidirectional"))
      (node (ref "U2") (pin "1") (pinfunction "OE_1") (pintype "input"))
      (node (ref "U9") (pin "10") (pinfunction "OE_10") (pintype "bidirectional"))
    )
    (net (code "191") (name "Net-(U13-VDDI)") (class "Default")
      (node (ref "C36") (pin "1") (pinfunction "1_1") (pintype "passive"))
      (node (ref "U13") (pin "C2") (pinfunction "VDDI_C2") (pintype "bidirectional"))
    )
    (net (code "192") (name "Net-(X3-GND)") (class "Default")
      (node (ref "L4") (pin "2") (pinfunction "2_2") (pintype "passive"))
      (node (ref "X3") (pin "4") (pinfunction "GND_4") (pintype "bidirectional"))
    )
    (net (code "193") (name "Net-(X3-VBUS)") (class "Default")
      (node (ref "L5") (pin "2") (pinfunction "2_2") (pintype "passive"))
      (node (ref "X3") (pin "1") (pinfunction "VBUS_1") (pintype "bidirectional"))
    )
    (net (code "194") (name "PAUSE_BTN") (class "Default")
      (node (ref "PAU") (pin "2") (pinfunction "2_2") (pintype "passive"))
      (node (ref "SIP") (pin "T6") (pinfunction "TIMER5_T6_T6") (pintype "bidirectional"))
    )
    (net (code "195") (name "PMIC_INT") (class "Default")
      (node (ref "SIP") (pin "B18") (pinfunction "EXTINTN_B18") (pintype "bidirectional"))
      (node (ref "SIP") (pin "B19") (pinfunction "PMIC_OUT_NINT_B19") (pintype "output"))
    )
    (net (code "196") (name "PMIC_NWAKEUP") (class "Default")
      (node (ref "SIP") (pin "A19") (pinfunction "PMIC_OUT_NWAKEUP_A19") (pintype "output"))
      (node (ref "SIP") (pin "C5") (pinfunction "EXT_WAKEUP_C5") (pintype "bidirectional"))
    )
    (net (code "197") (name "PMIC_PGOOD") (class "Default")
      (node (ref "SIP") (pin "A20") (pinfunction "PMIC_OUT_PGOOD_A20") (pintype "output"))
      (node (ref "SIP") (pin "B15") (pinfunction "PWRONRSTN_B15") (pintype "bidirectional"))
      (node (ref "U6") (pin "2") (pinfunction "A_2") (pintype "input"))
    )
    (net (code "198") (name "POWER_BTN") (class "Default")
      (node (ref "POW") (pin "2") (pinfunction "2_2") (pintype "passive"))
      (node (ref "SIP") (pin "D20") (pinfunction "PMIC_IN_PB_IN_D20") (pintype "bidirectional"))
    )
    (net (code "199") (name "PRU_E_A") (class "Default")
      (node (ref "E4") (pin "3") (pinfunction "3_3") (pintype "bidirectional"))
      (node (ref "SIP") (pin "V13") (pinfunction "GPIO1_14_V13_V13") (pintype "bidirectional"))
    )
    (net (code "200") (name "PRU_E_B") (class "Default")
      (node (ref "E4") (pin "4") (pinfunction "4_4") (pintype "bidirectional"))
      (node (ref "SIP") (pin "U13") (pinfunction "GPIO1_15_U13_U13") (pintype "bidirectional"))
    )
    (net (code "201") (name "PWM_1A") (class "Default")
      (node (ref "H1") (pin "23") (pinfunction "PWMA_23") (pintype "bidirectional"))
      (node (ref "SIP") (pin "U14") (pinfunction "EHRPWM1A_U14_U14") (pintype "bidirectional"))
    )
    (net (code "202") (name "PWM_1B") (class "Default")
      (node (ref "H1") (pin "15") (pinfunction "PWMB_15") (pintype "bidirectional"))
      (node (ref "SIP") (pin "T14") (pinfunction "EHRPWM1B_T14_T14") (pintype "bidirectional"))
    )
    (net (code "203") (name "PWM_2A") (class "Default")
      (node (ref "H2") (pin "23") (pinfunction "PWMA_23") (pintype "bidirectional"))
      (node (ref "SIP") (pin "U10") (pinfunction "EHRPWM2A_U10_U10") (pintype "bidirectional"))
    )
    (net (code "204") (name "PWM_2B") (class "Default")
      (node (ref "H2") (pin "15") (pinfunction "PWMB_15") (pintype "bidirectional"))
      (node (ref "SIP") (pin "T10") (pinfunction "EHRPWM2B_T10_T10") (pintype "bidirectional"))
    )
    (net (code "205") (name "PWR_LED") (class "Default")
      (node (ref "ON") (pin "C") (pinfunction "C_C") (pintype "passive"))
      (node (ref "R24") (pin "1") (pinfunction "1_1") (pintype "passive"))
    )
    (net (code "206") (name "RESET") (class "Default")
      (node (ref "C33") (pin "1") (pinfunction "1_1") (pintype "passive"))
      (node (ref "R60") (pin "1") (pinfunction "1_1") (pintype "passive"))
      (node (ref "RST") (pin "2") (pinfunction "2_2") (pintype "passive"))
      (node (ref "SIP") (pin "A10") (pinfunction "WARMRSTN_A10") (pintype "bidirectional"))
      (node (ref "U6") (pin "4") (pinfunction "Y_4") (pintype "output"))
    )
    (net (code "207") (name "SD_BOOT") (class "Default")
      (node (ref "R77") (pin "2") (pinfunction "2_2") (pintype "passive"))
      (node (ref "SD") (pin "2") (pinfunction "2_2") (pintype "passive"))
    )
    (net (code "208") (name "SERVO_EN") (class "Default")
      (node (ref "6VREG") (pin "8") (pinfunction "EN_8") (pintype "bidirectional"))
      (node (ref "R46") (pin "2") (pinfunction "2_2") (pintype "passive"))
      (node (ref "SIP") (pin "U3") (pinfunction "LCD_DATA10_U3_U3") (pintype "bidirectional"))
    )
    (net (code "209") (name "SPI1_MISO") (class "Default")
      (node (ref "S1.1") (pin "4") (pinfunction "4_4") (pintype "bidirectional"))
      (node (ref "S1.2") (pin "4") (pinfunction "4_4") (pintype "bidirectional"))
      (node (ref "SIP") (pin "B13") (pinfunction "SPI1_D0_B13_B13") (pintype "bidirectional"))
    )
    (net (code "210") (name "SPI1_MOSI") (class "Default")
      (node (ref "S1.1") (pin "3") (pinfunction "3_3") (pintype "bidirectional"))
      (node (ref "S1.2") (pin "3") (pinfunction "3_3") (pintype "bidirectional"))
      (node (ref "SIP") (pin "D12") (pinfunction "SPI1_D1_D12_D12") (pintype "bidirectional"))
    )
    (net (code "211") (name "SPI1_SCK") (class "Default")
      (node (ref "S1.1") (pin "5") (pinfunction "5_5") (pintype "bidirectional"))
      (node (ref "S1.2") (pin "5") (pinfunction "5_5") (pintype "bidirectional"))
      (node (ref "SIP") (pin "A13") (pinfunction "SPI1_CLK_A13_A13") (pintype "bidirectional"))
    )
    (net (code "212") (name "SPI1_SS1") (class "Default")
      (node (ref "S1.1") (pin "6") (pinfunction "6_6") (pintype "bidirectional"))
      (node (ref "SIP") (pin "H18") (pinfunction "H18_H18") (pintype "bidirectional"))
    )
    (net (code "213") (name "SPI1_SS2") (class "Default")
      (node (ref "S1.2") (pin "6") (pinfunction "6_6") (pintype "bidirectional"))
      (node (ref "SIP") (pin "C18") (pinfunction "GPIO0_7_C18_C18") (pintype "bidirectional"))
    )
    (net (code "214") (name "SVO1") (class "Default")
      (node (ref "R36") (pin "1") (pinfunction "1_1") (pintype "passive"))
      (node (ref "R50") (pin "1") (pinfunction "1_1") (pintype "passive"))
      (node (ref "SIP") (pin "U5") (pinfunction "LCD_VSYNC_U5_U5") (pintype "bidirectional"))
    )
    (net (code "215") (name "SVO2") (class "Default")
      (node (ref "R37") (pin "1") (pinfunction "1_1") (pintype "passive"))
      (node (ref "R51") (pin "1") (pinfunction "1_1") (pintype "passive"))
      (node (ref "SIP") (pin "V5") (pinfunction "LCD_PCLK_V5_V5") (pintype "bidirectional"))
    )
    (net (code "216") (name "SVO3") (class "Default")
      (node (ref "R38") (pin "1") (pinfunction "1_1") (pintype "passive"))
      (node (ref "R52") (pin "1") (pinfunction "1_1") (pintype "passive"))
      (node (ref "SIP") (pin "R5") (pinfunction "LCD_HSYNC_R5_R5") (pintype "bidirectional"))
    )
    (net (code "217") (name "SVO4") (class "Default")
      (node (ref "R39") (pin "1") (pinfunction "1_1") (pintype "passive"))
      (node (ref "R53") (pin "1") (pinfunction "1_1") (pintype "passive"))
      (node (ref "SIP") (pin "R6") (pinfunction "LCD_DE_R6_R6") (pintype "bidirectional"))
    )
    (net (code "218") (name "SVO5") (class "Default")
      (node (ref "R125") (pin "2") (pinfunction "2_2") (pintype "passive"))
      (node (ref "R40") (pin "1") (pinfunction "1_1") (pintype "passive"))
      (node (ref "SIP") (pin "T3") (pinfunction "LCD_DATA6_T3_T3") (pintype "bidirectional"))
    )
    (net (code "219") (name "SVO6") (class "Default")
      (node (ref "R127") (pin "2") (pinfunction "2_2") (pintype "passive"))
      (node (ref "R41") (pin "1") (pinfunction "1_1") (pintype "passive"))
      (node (ref "SIP") (pin "T4") (pinfunction "LCD_DATA7_T4_T4") (pintype "bidirectional"))
    )
    (net (code "220") (name "SVO7") (class "Default")
      (node (ref "R120") (pin "1") (pinfunction "1_1") (pintype "passive"))
      (node (ref "R42") (pin "1") (pinfunction "1_1") (pintype "passive"))
      (node (ref "SIP") (pin "T1") (pinfunction "LCD_DATA4_T1_T1") (pintype "bidirectional"))
    )
    (net (code "221") (name "SVO8") (class "Default")
      (node (ref "R122") (pin "1") (pinfunction "1_1") (pintype "passive"))
      (node (ref "R43") (pin "1") (pinfunction "1_1") (pintype "passive"))
      (node (ref "SIP") (pin "T2") (pinfunction "LCD_DATA5_T2_T2") (pintype "bidirectional"))
    )
    (net (code "222") (name "SYS_5V") (class "Default")
      (node (ref "C62") (pin "1") (pinfunction "1_1") (pintype "passive"))
      (node (ref "R121") (pin "2") (pinfunction "2_2") (pintype "passive"))
      (node (ref "SIP") (pin "W4") (pinfunction "VOUT_SYS_5V_0_W4") (pintype "power_in"))
      (node (ref "SIP") (pin "Y4") (pinfunction "VOUT_SYS_5V_1_Y4") (pintype "power_in"))
      (node (ref "TP1") (pin "TP") (pinfunction "TP_TP") (pintype "input"))
      (node (ref "U1") (pin "3") (pinfunction "VCC_3") (pintype "power_in"))
      (node (ref "U8") (pin "3") (pinfunction "IN2_3") (pintype "input"))
    )
    (net (code "223") (name "UART0_RX") (class "Default")
      (node (ref "SIP") (pin "E15") (pinfunction "UART0_RXD_E15_E15") (pintype "bidirectional"))
      (node (ref "UT0") (pin "3") (pinfunction "3_3") (pintype "bidirectional"))
    )
    (net (code "224") (name "UART0_TX") (class "Default")
      (node (ref "SIP") (pin "E16") (pinfunction "UART0_TXD_E16_E16") (pintype "bidirectional"))
      (node (ref "UT0") (pin "4") (pinfunction "4_4") (pintype "bidirectional"))
    )
    (net (code "225") (name "UART1_RX") (class "Default")
      (node (ref "SIP") (pin "D16") (pinfunction "UART1_RXD_D16_D16") (pintype "bidirectional"))
      (node (ref "UT1") (pin "3") (pinfunction "3_3") (pintype "bidirectional"))
    )
    (net (code "226") (name "UART1_TX") (class "Default")
      (node (ref "SIP") (pin "D15") (pinfunction "UART1_TXD_D15_D15") (pintype "bidirectional"))
      (node (ref "UT1") (pin "4") (pinfunction "4_4") (pintype "bidirectional"))
    )
    (net (code "227") (name "UART2_RX") (class "Default")
      (node (ref "GPS") (pin "3") (pinfunction "3_3") (pintype "bidirectional"))
      (node (ref "SIP") (pin "A17") (pinfunction "UART2_RXD_A17_A17") (pintype "bidirectional"))
    )
    (net (code "228") (name "UART2_TX") (class "Default")
      (node (ref "GPS") (pin "4") (pinfunction "4_4") (pintype "bidirectional"))
      (node (ref "SIP") (pin "B17") (pinfunction "UART2_TXD_B17_B17") (pintype "bidirectional"))
    )
    (net (code "229") (name "UART3_CTSN") (class "Default")
      (node (ref "R89") (pin "1") (pinfunction "1_1") (pintype "passive"))
      (node (ref "SIP") (pin "M17") (pinfunction "M17_M17") (pintype "bidirectional"))
      (node (ref "U10") (pin "12") (pinfunction "B8_12") (pintype "bidirectional"))
    )
    (net (code "230") (name "UART3_RTSN") (class "Default")
      (node (ref "R108") (pin "1") (pinfunction "1_1") (pintype "passive"))
      (node (ref "SIP") (pin "M18") (pinfunction "M18_M18") (pintype "bidirectional"))
      (node (ref "U10") (pin "13") (pinfunction "B7_13") (pintype "bidirectional"))
    )
    (net (code "231") (name "UART3_RX") (class "Default")
      (node (ref "SIP") (pin "L17") (pinfunction "L17_L17") (pintype "bidirectional"))
      (node (ref "U10") (pin "14") (pinfunction "B6_14") (pintype "bidirectional"))
    )
    (net (code "232") (name "UART3_TX") (class "Default")
      (node (ref "SIP") (pin "L16") (pinfunction "L16_L16") (pintype "bidirectional"))
      (node (ref "U10") (pin "15") (pinfunction "B5_15") (pintype "bidirectional"))
    )
    (net (code "233") (name "UART4_RX") (class "Default")
      (node (ref "DSM2") (pin "P$3") (pinfunction "3_P$3") (pintype "bidirectional"))
      (node (ref "SIP") (pin "T17") (pinfunction "UART4_RXD_T17_T17") (pintype "bidirectional"))
    )
    (net (code "234") (name "UART5_RX") (class "Default")
      (node (ref "R131") (pin "2") (pinfunction "2_2") (pintype "passive"))
      (node (ref "SIP") (pin "U2") (pinfunction "LCD_DATA9_U2_U2") (pintype "bidirectional"))
      (node (ref "UT5") (pin "3") (pinfunction "3_3") (pintype "bidirectional"))
    )
    (net (code "235") (name "UART5_TX") (class "Default")
      (node (ref "R129") (pin "2") (pinfunction "2_2") (pintype "passive"))
      (node (ref "SIP") (pin "U1") (pinfunction "LCD_DATA8_U1_U1") (pintype "bidirectional"))
      (node (ref "UT5") (pin "4") (pinfunction "4_4") (pintype "bidirectional"))
    )
    (net (code "236") (name "USB0_D_N") (class "Default")
      (node (ref "SIP") (pin "N18") (pinfunction "USB0_DM_N18") (pintype "bidirectional"))
      (node (ref "U3") (pin "2") (pinfunction "D-_2") (pintype "bidirectional"))
      (node (ref "X4") (pin "D-") (pinfunction "D-_D-") (pintype "input"))
    )
    (net (code "237") (name "USB0_D_P") (class "Default")
      (node (ref "SIP") (pin "N17") (pinfunction "USB0_DP_N17") (pintype "bidirectional"))
      (node (ref "U3") (pin "1") (pinfunction "D+_1") (pintype "bidirectional"))
      (node (ref "X4") (pin "D+") (pinfunction "D+_D+") (pintype "input"))
    )
    (net (code "238") (name "USB0_ID") (class "Default")
      (node (ref "SIP") (pin "P16") (pinfunction "USB0_ID_P16") (pintype "bidirectional"))
      (node (ref "U3") (pin "3") (pinfunction "ID_3") (pintype "bidirectional"))
      (node (ref "X4") (pin "ID") (pinfunction "ID_ID") (pintype "input"))
    )
    (net (code "239") (name "USB0_VBUS") (class "Default")
      (node (ref "C54") (pin "1") (pinfunction "1_1") (pintype "passive"))
      (node (ref "R112") (pin "2") (pinfunction "2_2") (pintype "passive"))
      (node (ref "R149") (pin "2") (pinfunction "2_2") (pintype "passive"))
      (node (ref "U3") (pin "6") (pinfunction "VBUS_6") (pintype "bidirectional"))
      (node (ref "X4") (pin "VBUS") (pinfunction "VBUS_VBUS") (pintype "input"))
    )
    (net (code "240") (name "USB1_D_N") (class "Default")
      (node (ref "SIP") (pin "R18") (pinfunction "USB1_DM_R18") (pintype "bidirectional"))
      (node (ref "U4") (pin "2") (pinfunction "D-_2") (pintype "bidirectional"))
      (node (ref "X3") (pin "2") (pinfunction "D-_2") (pintype "bidirectional"))
    )
    (net (code "241") (name "USB1_D_P") (class "Default")
      (node (ref "SIP") (pin "R17") (pinfunction "USB1_DP_R17") (pintype "bidirectional"))
      (node (ref "U4") (pin "1") (pinfunction "D+_1") (pintype "bidirectional"))
      (node (ref "X3") (pin "3") (pinfunction "D+_3") (pintype "bidirectional"))
    )
    (net (code "242") (name "USB1_VBUS") (class "Default")
      (node (ref "C45") (pin "1") (pinfunction "1_1") (pintype "passive"))
      (node (ref "C46") (pin "1") (pinfunction "1_1") (pintype "passive"))
      (node (ref "C55") (pin "1") (pinfunction "1_1") (pintype "passive"))
      (node (ref "C61") (pin "2") (pinfunction "2_2") (pintype "passive"))
      (node (ref "L5") (pin "1") (pinfunction "1_1") (pintype "passive"))
      (node (ref "R119") (pin "1") (pinfunction "1_1") (pintype "passive"))
      (node (ref "R121") (pin "1") (pinfunction "1_1") (pintype "passive"))
      (node (ref "R156") (pin "2") (pinfunction "2_2") (pintype "passive"))
      (node (ref "U4") (pin "6") (pinfunction "VBUS_6") (pintype "bidirectional"))
      (node (ref "U8") (pin "4") (pinfunction "OUT_4") (pintype "output"))
    )
    (net (code "243") (name "USB_DC") (class "Default")
      (node (ref "R112") (pin "1") (pinfunction "1_1") (pintype "passive"))
      (node (ref "SIP") (pin "Y8") (pinfunction "VIN_USB_0_Y8") (pintype "power_in"))
      (node (ref "SIP") (pin "Y9") (pinfunction "VIN_USB_1_Y9") (pintype "power_in"))
    )
    (net (code "244") (name "USR_LED0") (class "Default")
      (node (ref "0") (pin "A") (pinfunction "A_A") (pintype "passive"))
      (node (ref "SIP") (pin "V15") (pinfunction "USR0_V15_V15") (pintype "bidirectional"))
    )
    (net (code "245") (name "USR_LED1") (class "Default")
      (node (ref "1") (pin "A") (pinfunction "A_A") (pintype "passive"))
      (node (ref "SIP") (pin "U15") (pinfunction "USR1_U15_U15") (pintype "bidirectional"))
    )
    (net (code "246") (name "USR_LED2") (class "Default")
      (node (ref "2") (pin "A") (pinfunction "A_A") (pintype "passive"))
      (node (ref "SIP") (pin "T15") (pinfunction "USR2_T15_T15") (pintype "bidirectional"))
    )
    (net (code "247") (name "USR_LED3") (class "Default")
      (node (ref "3") (pin "A") (pinfunction "A_A") (pintype "passive"))
      (node (ref "SIP") (pin "V16") (pinfunction "USR3_V16_V16") (pintype "bidirectional"))
    )
    (net (code "248") (name "VCC") (class "Default")
      (node (ref "12V") (pin "IN") (pinfunction "IN_IN") (pintype "bidirectional"))
      (node (ref "C12") (pin "1") (pinfunction "1_1") (pintype "passive"))
      (node (ref "C7") (pin "1") (pinfunction "1_1") (pintype "passive"))
      (node (ref "CHG") (pin "A") (pinfunction "A_A") (pintype "passive"))
      (node (ref "CHGIC") (pin "2") (pinfunction "VIN_2") (pintype "bidirectional"))
      (node (ref "D3") (pin "A") (pinfunction "A_A") (pintype "passive"))
      (node (ref "R1") (pin "1") (pinfunction "1_1") (pintype "passive"))
    )
    (net (code "249") (name "VCC_CHG") (class "Default")
      (node (ref "C4") (pin "2") (pinfunction "2_2") (pintype "passive"))
      (node (ref "CHGIC") (pin "3") (pinfunction "VCC_3") (pintype "bidirectional"))
      (node (ref "R5") (pin "2") (pinfunction "2_2") (pintype "passive"))
    )
    (net (code "250") (name "VDD_1V8") (class "Default")
      (node (ref "C47") (pin "1") (pinfunction "1_1") (pintype "passive"))
      (node (ref "C50") (pin "1") (pinfunction "1_1") (pintype "passive"))
      (node (ref "C52") (pin "1") (pinfunction "1_1") (pintype "passive"))
      (node (ref "C57") (pin "2") (pinfunction "2_2") (pintype "passive"))
      (node (ref "C60") (pin "2") (pinfunction "2_2") (pintype "passive"))
      (node (ref "OSC1") (pin "4") (pinfunction "VCC_4") (pintype "bidirectional"))
      (node (ref "R101") (pin "1") (pinfunction "1_1") (pintype "passive"))
      (node (ref "R102") (pin "1") (pinfunction "1_1") (pintype "passive"))
      (node (ref "R103") (pin "1") (pinfunction "1_1") (pintype "passive"))
      (node (ref "R105") (pin "1") (pinfunction "1_1") (pintype "passive"))
      (node (ref "R9") (pin "1") (pinfunction "1_1") (pintype "passive"))
      (node (ref "R90") (pin "2") (pinfunction "2_2") (pintype "passive"))
      (node (ref "R98") (pin "1") (pinfunction "1_1") (pintype "passive"))
      (node (ref "R99") (pin "1") (pinfunction "1_1") (pintype "passive"))
      (node (ref "SIP") (pin "D10") (pinfunction "VDD_1V84_D10") (pintype "bidirectional"))
      (node (ref "SIP") (pin "E9") (pinfunction "VDD_1V83_E9") (pintype "bidirectional"))
      (node (ref "SIP") (pin "N16") (pinfunction "VOUT_LDO3_1P8V_0_N16") (pintype "power_in"))
      (node (ref "SIP") (pin "R16") (pinfunction "VOUT_LDO3_1P8V_1_R16") (pintype "power_in"))
      (node (ref "U10") (pin "2") (pinfunction "VCCA_2") (pintype "bidirectional"))
      (node (ref "U2") (pin "5") (pinfunction "VCC_5") (pintype "power_in"))
      (node (ref "U7") (pin "38") (pinfunction "VIO_38") (pintype "bidirectional"))
      (node (ref "U9") (pin "2") (pinfunction "VCCA_2") (pintype "bidirectional"))
    )
    (net (code "251") (name "VDD_3V3AUX") (class "Default")
      (node (ref "ON") (pin "A") (pinfunction "A_A") (pintype "passive"))
      (node (ref "SIP") (pin "Y11") (pinfunction "VOUT_LDO2_3P3V_Y11") (pintype "power_in"))
    )
    (net (code "252") (name "VDD_ADC") (class "Default")
      (node (ref "ADC") (pin "2") (pinfunction "2_2") (pintype "bidirectional"))
      (node (ref "C44") (pin "1") (pinfunction "1_1") (pintype "passive"))
      (node (ref "R111") (pin "1") (pinfunction "1_1") (pintype "passive"))
      (node (ref "SIP") (pin "A4") (pinfunction "VOUT_ADC_1P8V_0_A4") (pintype "bidirectional"))
      (node (ref "SIP") (pin "A5") (pinfunction "VOUT_ADC_1P8V_1_A5") (pintype "bidirectional"))
      (node (ref "SIP") (pin "D8") (pinfunction "VDDA_ADC_D8") (pintype "bidirectional"))
    )
    (net (code "253") (name "VDD_RTC") (class "Default")
      (node (ref "SIP") (pin "E14") (pinfunction "VDD_RTC3_E14") (pintype "bidirectional"))
      (node (ref "U6") (pin "5") (pinfunction "VCC_5") (pintype "power_in"))
    )
    (net (code "254") (name "VIN_BAT_0") (class "Default")
      (node (ref "SIP") (pin "Y2") (pinfunction "VIN_BAT_0_Y2") (pintype "power_in"))
    )
    (net (code "255") (name "VIN_BAT_1") (class "Default")
      (node (ref "SIP") (pin "Y3") (pinfunction "VIN_BAT_1_Y3") (pintype "power_in"))
    )
    (net (code "256") (name "V_BATT") (class "Default")
      (node (ref "6VREG") (pin "9") (pinfunction "VIN_9") (pintype "bidirectional"))
      (node (ref "C11") (pin "+") (pinfunction "+_+") (pintype "passive"))
      (node (ref "C20") (pin "2") (pinfunction "2_2") (pintype "passive"))
      (node (ref "C25") (pin "1") (pinfunction "1_1") (pintype "passive"))
      (node (ref "C26") (pin "1") (pinfunction "1_1") (pintype "passive"))
      (node (ref "CHGIC") (pin "9") (pinfunction "BATT_9") (pintype "bidirectional"))
      (node (ref "D2") (pin "A") (pinfunction "A_A") (pintype "passive"))
      (node (ref "H1") (pin "13") (pinfunction "VM2_13") (pintype "bidirectional"))
      (node (ref "H1") (pin "14") (pinfunction "VM3_14") (pintype "bidirectional"))
      (node (ref "H1") (pin "24") (pinfunction "VM1_24") (pintype "bidirectional"))
      (node (ref "H2") (pin "13") (pinfunction "VM2_13") (pintype "bidirectional"))
      (node (ref "H2") (pin "14") (pinfunction "VM3_14") (pintype "bidirectional"))
      (node (ref "H2") (pin "24") (pinfunction "VM1_24") (pintype "bidirectional"))
      (node (ref "LIPO") (pin "P$1") (pinfunction "1_P$1") (pintype "passive"))
      (node (ref "R19") (pin "1") (pinfunction "1_1") (pintype "passive"))
      (node (ref "R28") (pin "1") (pinfunction "1_1") (pintype "passive"))
      (node (ref "R34") (pin "1") (pinfunction "1_1") (pintype "passive"))
      (node (ref "R4") (pin "1") (pinfunction "1_1") (pintype "passive"))
    )
    (net (code "257") (name "V_DIV_BAT") (class "Default")
      (node (ref "R19") (pin "2") (pinfunction "2_2") (pintype "passive"))
      (node (ref "R25") (pin "1") (pinfunction "1_1") (pintype "passive"))
      (node (ref "SIP") (pin "A8") (pinfunction "AIN6_A8") (pintype "bidirectional"))
    )
    (net (code "258") (name "V_DIV_DC") (class "Default")
      (node (ref "R1") (pin "2") (pinfunction "2_2") (pintype "passive"))
      (node (ref "R14") (pin "1") (pinfunction "1_1") (pintype "passive"))
      (node (ref "SIP") (pin "B8") (pinfunction "AIN5_B8") (pintype "bidirectional"))
    )
    (net (code "259") (name "WIFI_LED") (class "Default")
      (node (ref "SIP") (pin "A15") (pinfunction "GPIO0_19_A15_A15") (pintype "bidirectional"))
      (node (ref "WIFI") (pin "A") (pinfunction "A_A") (pintype "passive"))
    )
    (net (code "260") (name "WLAN_IRQ") (class "Default")
      (node (ref "SIP") (pin "K16") (pinfunction "K16_K16") (pintype "bidirectional"))
      (node (ref "U2") (pin "4") (pinfunction "Y_4") (pintype "output"))
    )
    (net (code "261") (name "WL_BT_OE") (class "Default")
      (node (ref "R93") (pin "1") (pinfunction "1_1") (pintype "passive"))
      (node (ref "SIP") (pin "L18") (pinfunction "L18_L18") (pintype "bidirectional"))
    )
    (net (code "262") (name "WL_EN") (class "Default")
      (node (ref "SIP") (pin "K18") (pinfunction "K18_K18") (pintype "bidirectional"))
      (node (ref "U9") (pin "20") (pinfunction "B1_20") (pintype "bidirectional"))
    )
    (net (code "263") (name "WL_EN_1V8") (class "Default")
      (node (ref "R87") (pin "1") (pinfunction "1_1") (pintype "passive"))
      (node (ref "U7") (pin "40") (pinfunction "WLAN_EN_40") (pintype "bidirectional"))
      (node (ref "U9") (pin "1") (pinfunction "A1_1") (pintype "bidirectional"))
    )
    (net (code "264") (name "WL_IRQ") (class "Default")
      (node (ref "R84") (pin "1") (pinfunction "1_1") (pintype "passive"))
      (node (ref "U2") (pin "2") (pinfunction "A_2") (pintype "input"))
    )
    (net (code "265") (name "WL_SDIO_CLK") (class "Default")
      (node (ref "R103") (pin "2") (pinfunction "2_2") (pintype "passive"))
      (node (ref "R78") (pin "1") (pinfunction "1_1") (pintype "passive"))
      (node (ref "U9") (pin "8") (pinfunction "A7_8") (pintype "bidirectional"))
    )
    (net (code "266") (name "WL_SDIO_CMD") (class "Default")
      (node (ref "R105") (pin "2") (pinfunction "2_2") (pintype "passive"))
      (node (ref "R79") (pin "1") (pinfunction "1_1") (pintype "passive"))
      (node (ref "U9") (pin "9") (pinfunction "A8_9") (pintype "bidirectional"))
    )
    (net (code "267") (name "WL_SDIO_D0") (class "Default")
      (node (ref "R80") (pin "1") (pinfunction "1_1") (pintype "passive"))
      (node (ref "R98") (pin "2") (pinfunction "2_2") (pintype "passive"))
      (node (ref "U9") (pin "7") (pinfunction "A6_7") (pintype "bidirectional"))
    )
    (net (code "268") (name "WL_SDIO_D1") (class "Default")
      (node (ref "R81") (pin "1") (pinfunction "1_1") (pintype "passive"))
      (node (ref "R99") (pin "2") (pinfunction "2_2") (pintype "passive"))
      (node (ref "U9") (pin "6") (pinfunction "A5_6") (pintype "bidirectional"))
    )
    (net (code "269") (name "WL_SDIO_D2") (class "Default")
      (node (ref "R101") (pin "2") (pinfunction "2_2") (pintype "passive"))
      (node (ref "R82") (pin "1") (pinfunction "1_1") (pintype "passive"))
      (node (ref "U9") (pin "5") (pinfunction "A4_5") (pintype "bidirectional"))
    )
    (net (code "270") (name "WL_SDIO_D3") (class "Default")
      (node (ref "R102") (pin "2") (pinfunction "2_2") (pintype "passive"))
      (node (ref "R83") (pin "1") (pinfunction "1_1") (pintype "passive"))
      (node (ref "U9") (pin "4") (pinfunction "A3_4") (pintype "bidirectional"))
    )
    (net (code "271") (name "unconnected-(12V-PadOUT_CON)") (class "Default")
      (node (ref "12V") (pin "OUT_CON") (pinfunction "OUT_CON_OUT_CON") (pintype "bidirectional"))
    )
    (net (code "272") (name "unconnected-(CHGIC-ACOK-Pad12)") (class "Default")
      (node (ref "CHGIC") (pin "12") (pinfunction "ACOK_12") (pintype "bidirectional"))
    )
    (net (code "273") (name "unconnected-(CHGIC-CELL-Pad4)") (class "Default")
      (node (ref "CHGIC") (pin "4") (pinfunction "CELL_4") (pintype "bidirectional"))
    )
    (net (code "274") (name "unconnected-(CHGIC-SEL-Pad5)") (class "Default")
      (node (ref "CHGIC") (pin "5") (pinfunction "SEL_5") (pintype "bidirectional"))
    )
    (net (code "275") (name "unconnected-(FUD1-PadP$1)") (class "Default")
      (node (ref "FUD1") (pin "P$1") (pinfunction "P$1_P$1") (pintype "no_connect"))
    )
    (net (code "276") (name "unconnected-(FUD2-PadP$1)") (class "Default")
      (node (ref "FUD2") (pin "P$1") (pinfunction "P$1_P$1") (pintype "no_connect"))
    )
    (net (code "277") (name "unconnected-(FUD3-PadP$1)") (class "Default")
      (node (ref "FUD3") (pin "P$1") (pinfunction "P$1_P$1") (pintype "no_connect"))
    )
    (net (code "278") (name "unconnected-(FUD4-PadP$1)") (class "Default")
      (node (ref "FUD4") (pin "P$1") (pinfunction "P$1_P$1") (pintype "no_connect"))
    )
    (net (code "279") (name "unconnected-(FUD5-PadP$1)") (class "Default")
      (node (ref "FUD5") (pin "P$1") (pinfunction "P$1_P$1") (pintype "no_connect"))
    )
    (net (code "280") (name "unconnected-(FUD6-PadP$1)") (class "Default")
      (node (ref "FUD6") (pin "P$1") (pinfunction "P$1_P$1") (pintype "no_connect"))
    )
    (net (code "281") (name "unconnected-(GPS-Pad1)") (class "Default")
      (node (ref "GPS") (pin "1") (pinfunction "1_1") (pintype "bidirectional"))
    )
    (net (code "282") (name "unconnected-(IMU-AUX_CL-Pad7)") (class "Default")
      (node (ref "IMU") (pin "7") (pinfunction "AUX_CL_7") (pintype "bidirectional"))
    )
    (net (code "283") (name "unconnected-(IMU-AUX_DA-Pad21)") (class "Default")
      (node (ref "IMU") (pin "21") (pinfunction "AUX_DA_21") (pintype "bidirectional"))
    )
    (net (code "284") (name "unconnected-(IMU-FSYNC-Pad11)") (class "Default")
      (node (ref "IMU") (pin "11") (pinfunction "FSYNC_11") (pintype "bidirectional"))
    )
    (net (code "285") (name "unconnected-(IMU-NC-Pad2)") (class "Default")
      (node (ref "IMU") (pin "2") (pinfunction "NC_2") (pintype "bidirectional"))
    )
    (net (code "286") (name "unconnected-(IMU-NC-Pad3)") (class "Default")
      (node (ref "IMU") (pin "3") (pinfunction "NC_3") (pintype "bidirectional"))
    )
    (net (code "287") (name "unconnected-(IMU-NC-Pad4)") (class "Default")
      (node (ref "IMU") (pin "4") (pinfunction "NC_4") (pintype "bidirectional"))
    )
    (net (code "288") (name "unconnected-(IMU-NC-Pad5)") (class "Default")
      (node (ref "IMU") (pin "5") (pinfunction "NC_5") (pintype "bidirectional"))
    )
    (net (code "289") (name "unconnected-(IMU-NC-Pad6)") (class "Default")
      (node (ref "IMU") (pin "6") (pinfunction "NC_6") (pintype "bidirectional"))
    )
    (net (code "290") (name "unconnected-(IMU-NC-Pad14)") (class "Default")
      (node (ref "IMU") (pin "14") (pinfunction "NC_14") (pintype "bidirectional"))
    )
    (net (code "291") (name "unconnected-(IMU-NC-Pad15)") (class "Default")
      (node (ref "IMU") (pin "15") (pinfunction "NC_15") (pintype "bidirectional"))
    )
    (net (code "292") (name "unconnected-(IMU-NC-Pad16)") (class "Default")
      (node (ref "IMU") (pin "16") (pinfunction "NC_16") (pintype "bidirectional"))
    )
    (net (code "293") (name "unconnected-(IMU-NC-Pad17)") (class "Default")
      (node (ref "IMU") (pin "17") (pinfunction "NC_17") (pintype "bidirectional"))
    )
    (net (code "294") (name "unconnected-(IMU-RESV-Pad19)") (class "Default")
      (node (ref "IMU") (pin "19") (pinfunction "RESV_19") (pintype "bidirectional"))
    )
    (net (code "295") (name "unconnected-(PROT-CO-Pad3)") (class "Default")
      (node (ref "PROT") (pin "3") (pinfunction "CO_3") (pintype "bidirectional"))
    )
    (net (code "296") (name "unconnected-(PROT-DP-Pad4)") (class "Default")
      (node (ref "PROT") (pin "4") (pinfunction "DP_4") (pintype "bidirectional"))
    )
    (net (code "297") (name "unconnected-(SIPA-BAT_TEMP-PadW1)") (class "Default")
      (node (ref "SIP") (pin "W1") (pinfunction "BAT_TEMP_W1") (pintype "bidirectional"))
    )
    (net (code "298") (name "unconnected-(SIPA-BAT_VOLT-PadY1)") (class "Default")
      (node (ref "SIP") (pin "Y1") (pinfunction "BAT_VOLT_Y1") (pintype "bidirectional"))
    )
    (net (code "299") (name "unconnected-(SIPA-L1_IN-PadY14)") (class "Default")
      (node (ref "SIP") (pin "Y14") (pinfunction "L1_IN_Y14") (pintype "bidirectional"))
    )
    (net (code "300") (name "unconnected-(SIPA-L1_OUT-PadY13)") (class "Default")
      (node (ref "SIP") (pin "Y13") (pinfunction "L1_OUT_Y13") (pintype "bidirectional"))
    )
    (net (code "301") (name "unconnected-(SIPA-L2_IN-PadY17)") (class "Default")
      (node (ref "SIP") (pin "Y17") (pinfunction "L2_IN_Y17") (pintype "bidirectional"))
    )
    (net (code "302") (name "unconnected-(SIPA-L2_OUT-PadY16)") (class "Default")
      (node (ref "SIP") (pin "Y16") (pinfunction "L2_OUT_Y16") (pintype "bidirectional"))
    )
    (net (code "303") (name "unconnected-(SIPA-L3_IN-PadY20)") (class "Default")
      (node (ref "SIP") (pin "Y20") (pinfunction "L3_IN_Y20") (pintype "bidirectional"))
    )
    (net (code "304") (name "unconnected-(SIPA-L3_OUT-PadY19)") (class "Default")
      (node (ref "SIP") (pin "Y19") (pinfunction "L3_OUT_Y19") (pintype "bidirectional"))
    )
    (net (code "305") (name "unconnected-(SIPC-AIN4-PadC8)") (class "Default")
      (node (ref "SIP") (pin "C8") (pinfunction "AIN4_C8") (pintype "bidirectional"))
    )
    (net (code "306") (name "unconnected-(SIPC-USB0_CE-PadM15)") (class "Default")
      (node (ref "SIP") (pin "M15") (pinfunction "USB0_CE_M15") (pintype "bidirectional"))
    )
    (net (code "307") (name "unconnected-(SIPC-USB0_DRVVBUS-PadF16)") (class "Default")
      (node (ref "SIP") (pin "F16") (pinfunction "USB0_DRVVBUS_F16") (pintype "bidirectional"))
    )
    (net (code "308") (name "unconnected-(SIPC-USB1_CE-PadP18)") (class "Default")
      (node (ref "SIP") (pin "P18") (pinfunction "USB1_CE_P18") (pintype "bidirectional"))
    )
    (net (code "309") (name "unconnected-(SIPC-USB1_DRVVBUS-PadF15)") (class "Default")
      (node (ref "SIP") (pin "F15") (pinfunction "USB1_DRVVBUS_F15") (pintype "bidirectional"))
    )
    (net (code "310") (name "unconnected-(SIPD-NC1-PadV11)") (class "Default")
      (node (ref "SIP") (pin "V11") (pinfunction "NC1_V11") (pintype "bidirectional"))
    )
    (net (code "311") (name "unconnected-(SIPD-NC2-PadU11)") (class "Default")
      (node (ref "SIP") (pin "U11") (pinfunction "NC2_U11") (pintype "bidirectional"))
    )
    (net (code "312") (name "unconnected-(SIPD-NC3-PadV10)") (class "Default")
      (node (ref "SIP") (pin "V10") (pinfunction "NC3_V10") (pintype "bidirectional"))
    )
    (net (code "313") (name "unconnected-(SIPD-NC4-PadB1)") (class "Default")
      (node (ref "SIP") (pin "B1") (pinfunction "NC4_B1") (pintype "bidirectional"))
    )
    (net (code "314") (name "unconnected-(SIPD-NC5-PadB2)") (class "Default")
      (node (ref "SIP") (pin "B2") (pinfunction "NC5_B2") (pintype "bidirectional"))
    )
    (net (code "315") (name "unconnected-(SIPD-NC6-PadB3)") (class "Default")
      (node (ref "SIP") (pin "B3") (pinfunction "NC6_B3") (pintype "bidirectional"))
    )
    (net (code "316") (name "unconnected-(SIPD-NC12-PadC1)") (class "Default")
      (node (ref "SIP") (pin "C1") (pinfunction "NC12_C1") (pintype "bidirectional"))
    )
    (net (code "317") (name "unconnected-(SIPD-NC20-PadC2)") (class "Default")
      (node (ref "SIP") (pin "C2") (pinfunction "NC20_C2") (pintype "bidirectional"))
    )
    (net (code "318") (name "unconnected-(SIPD-NC21-PadC3)") (class "Default")
      (node (ref "SIP") (pin "C3") (pinfunction "NC21_C3") (pintype "bidirectional"))
    )
    (net (code "319") (name "unconnected-(SIPD-NC22-PadC4)") (class "Default")
      (node (ref "SIP") (pin "C4") (pinfunction "NC22_C4") (pintype "bidirectional"))
    )
    (net (code "320") (name "unconnected-(SIPD-NC23-PadP2)") (class "Default")
      (node (ref "SIP") (pin "P2") (pinfunction "NC23_P2") (pintype "bidirectional"))
    )
    (net (code "321") (name "unconnected-(SIPD-NC24-PadD1)") (class "Default")
      (node (ref "SIP") (pin "D1") (pinfunction "NC24_D1") (pintype "bidirectional"))
    )
    (net (code "322") (name "unconnected-(SIPD-NC31-PadD2)") (class "Default")
      (node (ref "SIP") (pin "D2") (pinfunction "NC31_D2") (pintype "bidirectional"))
    )
    (net (code "323") (name "unconnected-(SIPD-NC32-PadD3)") (class "Default")
      (node (ref "SIP") (pin "D3") (pinfunction "NC32_D3") (pintype "bidirectional"))
    )
    (net (code "324") (name "unconnected-(SIPD-NC33-PadD4)") (class "Default")
      (node (ref "SIP") (pin "D4") (pinfunction "NC33_D4") (pintype "bidirectional"))
    )
    (net (code "325") (name "unconnected-(SIPD-NC34-PadD5)") (class "Default")
      (node (ref "SIP") (pin "D5") (pinfunction "NC34_D5") (pintype "bidirectional"))
    )
    (net (code "326") (name "unconnected-(SIPD-NC45-PadP3)") (class "Default")
      (node (ref "SIP") (pin "P3") (pinfunction "NC45_P3") (pintype "bidirectional"))
    )
    (net (code "327") (name "unconnected-(SIPD-NC46-PadE1)") (class "Default")
      (node (ref "SIP") (pin "E1") (pinfunction "NC46_E1") (pintype "bidirectional"))
    )
    (net (code "328") (name "unconnected-(SIPD-NC47-PadE2)") (class "Default")
      (node (ref "SIP") (pin "E2") (pinfunction "NC47_E2") (pintype "bidirectional"))
    )
    (net (code "329") (name "unconnected-(SIPD-NC48-PadE3)") (class "Default")
      (node (ref "SIP") (pin "E3") (pinfunction "NC48_E3") (pintype "bidirectional"))
    )
    (net (code "330") (name "unconnected-(SIPD-NC58-PadE4)") (class "Default")
      (node (ref "SIP") (pin "E4") (pinfunction "NC58_E4") (pintype "bidirectional"))
    )
    (net (code "331") (name "unconnected-(SIPD-NC59-PadF1)") (class "Default")
      (node (ref "SIP") (pin "F1") (pinfunction "NC59_F1") (pintype "bidirectional"))
    )
    (net (code "332") (name "unconnected-(SIPD-NC60-PadF2)") (class "Default")
      (node (ref "SIP") (pin "F2") (pinfunction "NC60_F2") (pintype "bidirectional"))
    )
    (net (code "333") (name "unconnected-(SIPD-NC61-PadF3)") (class "Default")
      (node (ref "SIP") (pin "F3") (pinfunction "NC61_F3") (pintype "bidirectional"))
    )
    (net (code "334") (name "unconnected-(SIPD-NC68-PadF4)") (class "Default")
      (node (ref "SIP") (pin "F4") (pinfunction "NC68_F4") (pintype "bidirectional"))
    )
    (net (code "335") (name "unconnected-(SIPD-NC69-PadG1)") (class "Default")
      (node (ref "SIP") (pin "G1") (pinfunction "NC69_G1") (pintype "bidirectional"))
    )
    (net (code "336") (name "unconnected-(SIPD-NC70-PadG2)") (class "Default")
      (node (ref "SIP") (pin "G2") (pinfunction "NC70_G2") (pintype "bidirectional"))
    )
    (net (code "337") (name "unconnected-(SIPD-NC71-PadG3)") (class "Default")
      (node (ref "SIP") (pin "G3") (pinfunction "NC71_G3") (pintype "bidirectional"))
    )
    (net (code "338") (name "unconnected-(SIPD-NC76-PadG4)") (class "Default")
      (node (ref "SIP") (pin "G4") (pinfunction "NC76_G4") (pintype "bidirectional"))
    )
    (net (code "339") (name "unconnected-(SIPD-NC77-PadH1)") (class "Default")
      (node (ref "SIP") (pin "H1") (pinfunction "NC77_H1") (pintype "bidirectional"))
    )
    (net (code "340") (name "unconnected-(SIPD-NC78-PadH2)") (class "Default")
      (node (ref "SIP") (pin "H2") (pinfunction "NC78_H2") (pintype "bidirectional"))
    )
    (net (code "341") (name "unconnected-(SIPD-NC79-PadH3)") (class "Default")
      (node (ref "SIP") (pin "H3") (pinfunction "NC79_H3") (pintype "bidirectional"))
    )
    (net (code "342") (name "unconnected-(SIPD-NC84-PadH4)") (class "Default")
      (node (ref "SIP") (pin "H4") (pinfunction "NC84_H4") (pintype "bidirectional"))
    )
    (net (code "343") (name "unconnected-(SIPD-NC85-PadJ1)") (class "Default")
      (node (ref "SIP") (pin "J1") (pinfunction "NC85_J1") (pintype "bidirectional"))
    )
    (net (code "344") (name "unconnected-(SIPD-NC86-PadJ2)") (class "Default")
      (node (ref "SIP") (pin "J2") (pinfunction "NC86_J2") (pintype "bidirectional"))
    )
    (net (code "345") (name "unconnected-(SIPD-NC87-PadJ3)") (class "Default")
      (node (ref "SIP") (pin "J3") (pinfunction "NC87_J3") (pintype "bidirectional"))
    )
    (net (code "346") (name "unconnected-(SIPD-NC94-PadJ4)") (class "Default")
      (node (ref "SIP") (pin "J4") (pinfunction "NC94_J4") (pintype "bidirectional"))
    )
    (net (code "347") (name "unconnected-(SIPD-NC95-PadK1)") (class "Default")
      (node (ref "SIP") (pin "K1") (pinfunction "NC95_K1") (pintype "bidirectional"))
    )
    (net (code "348") (name "unconnected-(SIPD-NC96-PadK2)") (class "Default")
      (node (ref "SIP") (pin "K2") (pinfunction "NC96_K2") (pintype "bidirectional"))
    )
    (net (code "349") (name "unconnected-(SIPD-NC97-PadK3)") (class "Default")
      (node (ref "SIP") (pin "K3") (pinfunction "NC97_K3") (pintype "bidirectional"))
    )
    (net (code "350") (name "unconnected-(SIPD-NC104-PadK4)") (class "Default")
      (node (ref "SIP") (pin "K4") (pinfunction "NC104_K4") (pintype "bidirectional"))
    )
    (net (code "351") (name "unconnected-(SIPD-NC105-PadL1)") (class "Default")
      (node (ref "SIP") (pin "L1") (pinfunction "NC105_L1") (pintype "bidirectional"))
    )
    (net (code "352") (name "unconnected-(SIPD-NC106-PadL2)") (class "Default")
      (node (ref "SIP") (pin "L2") (pinfunction "NC106_L2") (pintype "bidirectional"))
    )
    (net (code "353") (name "unconnected-(SIPD-NC107-PadL3)") (class "Default")
      (node (ref "SIP") (pin "L3") (pinfunction "NC107_L3") (pintype "bidirectional"))
    )
    (net (code "354") (name "unconnected-(SIPD-NC111-PadL4)") (class "Default")
      (node (ref "SIP") (pin "L4") (pinfunction "NC111_L4") (pintype "bidirectional"))
    )
    (net (code "355") (name "unconnected-(SIPD-NC112-PadM1)") (class "Default")
      (node (ref "SIP") (pin "M1") (pinfunction "NC112_M1") (pintype "bidirectional"))
    )
    (net (code "356") (name "unconnected-(SIPD-NC113-PadM2)") (class "Default")
      (node (ref "SIP") (pin "M2") (pinfunction "NC113_M2") (pintype "bidirectional"))
    )
    (net (code "357") (name "unconnected-(SIPD-NC114-PadM3)") (class "Default")
      (node (ref "SIP") (pin "M3") (pinfunction "NC114_M3") (pintype "bidirectional"))
    )
    (net (code "358") (name "unconnected-(SIPD-NC121-PadM4)") (class "Default")
      (node (ref "SIP") (pin "M4") (pinfunction "NC121_M4") (pintype "bidirectional"))
    )
    (net (code "359") (name "unconnected-(SIPD-NC122-PadP4)") (class "Default")
      (node (ref "SIP") (pin "P4") (pinfunction "NC122_P4") (pintype "bidirectional"))
    )
    (net (code "360") (name "unconnected-(SIPD-NC123-PadN1)") (class "Default")
      (node (ref "SIP") (pin "N1") (pinfunction "NC123_N1") (pintype "bidirectional"))
    )
    (net (code "361") (name "unconnected-(SIPD-NC124-PadN2)") (class "Default")
      (node (ref "SIP") (pin "N2") (pinfunction "NC124_N2") (pintype "bidirectional"))
    )
    (net (code "362") (name "unconnected-(SIPD-NC136-PadN3)") (class "Default")
      (node (ref "SIP") (pin "N3") (pinfunction "NC136_N3") (pintype "bidirectional"))
    )
    (net (code "363") (name "unconnected-(SIPD-NC137-PadN4)") (class "Default")
      (node (ref "SIP") (pin "N4") (pinfunction "NC137_N4") (pintype "bidirectional"))
    )
    (net (code "364") (name "unconnected-(SIPD-NC138-PadP1)") (class "Default")
      (node (ref "SIP") (pin "P1") (pinfunction "NC138_P1") (pintype "bidirectional"))
    )
    (net (code "365") (name "unconnected-(SIPE-CAP_VBB_MPU-PadC10)") (class "Default")
      (node (ref "SIP") (pin "C10") (pinfunction "CAP_VBB_MPU_C10") (pintype "bidirectional"))
    )
    (net (code "366") (name "unconnected-(SIPE-CAP_VDD_RTC-PadD6)") (class "Default")
      (node (ref "SIP") (pin "D6") (pinfunction "CAP_VDD_RTC_D6") (pintype "bidirectional"))
    )
    (net (code "367") (name "unconnected-(SIPE-CAP_VDD_SRAM_COR-PadD9)") (class "Default")
      (node (ref "SIP") (pin "D9") (pinfunction "CAP_VDD_SRAM_COR_D9") (pintype "bidirectional"))
    )
    (net (code "368") (name "unconnected-(SIPE-CAP_VDD_SRAM_MPU-PadD11)") (class "Default")
      (node (ref "SIP") (pin "D11") (pinfunction "CAP_VDD_SRAM_MPU_D11") (pintype "bidirectional"))
    )
    (net (code "369") (name "unconnected-(SIPE-TESTOUT-PadA3)") (class "Default")
      (node (ref "SIP") (pin "A3") (pinfunction "TESTOUT_A3") (pintype "bidirectional"))
    )
    (net (code "370") (name "unconnected-(SIPE-VDDS_DDR1-PadE5)") (class "Default")
      (node (ref "SIP") (pin "E5") (pinfunction "VDDS_DDR1_E5") (pintype "bidirectional"))
    )
    (net (code "371") (name "unconnected-(SIPE-VDDS_DDR2-PadF5)") (class "Default")
      (node (ref "SIP") (pin "F5") (pinfunction "VDDS_DDR2_F5") (pintype "bidirectional"))
    )
    (net (code "372") (name "unconnected-(SIPE-VDDS_DDR3-PadG5)") (class "Default")
      (node (ref "SIP") (pin "G5") (pinfunction "VDDS_DDR3_G5") (pintype "bidirectional"))
    )
    (net (code "373") (name "unconnected-(SIPE-VDDS_DDR4-PadH5)") (class "Default")
      (node (ref "SIP") (pin "H5") (pinfunction "VDDS_DDR4_H5") (pintype "bidirectional"))
    )
    (net (code "374") (name "unconnected-(SIPE-VDDS_DDR5-PadJ5)") (class "Default")
      (node (ref "SIP") (pin "J5") (pinfunction "VDDS_DDR5_J5") (pintype "bidirectional"))
    )
    (net (code "375") (name "unconnected-(SIPE-VDDS_DDR6-PadK5)") (class "Default")
      (node (ref "SIP") (pin "K5") (pinfunction "VDDS_DDR6_K5") (pintype "bidirectional"))
    )
    (net (code "376") (name "unconnected-(SIPE-VDDS_DDR7-PadL5)") (class "Default")
      (node (ref "SIP") (pin "L5") (pinfunction "VDDS_DDR7_L5") (pintype "bidirectional"))
    )
    (net (code "377") (name "unconnected-(SIPE-VDD_3V3A1-PadE10)") (class "Default")
      (node (ref "SIP") (pin "E10") (pinfunction "VDD_3V3A1_E10") (pintype "bidirectional"))
    )
    (net (code "378") (name "unconnected-(SIPE-VDD_3V3A2-PadE11)") (class "Default")
      (node (ref "SIP") (pin "E11") (pinfunction "VDD_3V3A2_E11") (pintype "bidirectional"))
    )
    (net (code "379") (name "unconnected-(SIPE-VDD_3V3A3-PadE12)") (class "Default")
      (node (ref "SIP") (pin "E12") (pinfunction "VDD_3V3A3_E12") (pintype "bidirectional"))
    )
    (net (code "380") (name "unconnected-(SIPE-VDD_3V3A4-PadE13)") (class "Default")
      (node (ref "SIP") (pin "E13") (pinfunction "VDD_3V3A4_E13") (pintype "bidirectional"))
    )
    (net (code "381") (name "unconnected-(SIPE-VDD_3V3A5-PadF14)") (class "Default")
      (node (ref "SIP") (pin "F14") (pinfunction "VDD_3V3A5_F14") (pintype "bidirectional"))
    )
    (net (code "382") (name "unconnected-(SIPE-VDD_3V3A6-PadG14)") (class "Default")
      (node (ref "SIP") (pin "G14") (pinfunction "VDD_3V3A6_G14") (pintype "bidirectional"))
    )
    (net (code "383") (name "unconnected-(SIPE-VDD_3V3A7-PadH14)") (class "Default")
      (node (ref "SIP") (pin "H14") (pinfunction "VDD_3V3A7_H14") (pintype "bidirectional"))
    )
    (net (code "384") (name "unconnected-(SIPE-VDD_3V3A8-PadJ14)") (class "Default")
      (node (ref "SIP") (pin "J14") (pinfunction "VDD_3V3A8_J14") (pintype "bidirectional"))
    )
    (net (code "385") (name "unconnected-(SIPE-VDD_3V3A9-PadK14)") (class "Default")
      (node (ref "SIP") (pin "K14") (pinfunction "VDD_3V3A9_K14") (pintype "bidirectional"))
    )
    (net (code "386") (name "unconnected-(SIPE-VDD_3V3A10-PadL14)") (class "Default")
      (node (ref "SIP") (pin "L14") (pinfunction "VDD_3V3A10_L14") (pintype "bidirectional"))
    )
    (net (code "387") (name "unconnected-(SIPE-VDD_3V3A11-PadN5)") (class "Default")
      (node (ref "SIP") (pin "N5") (pinfunction "VDD_3V3A11_N5") (pintype "bidirectional"))
    )
    (net (code "388") (name "unconnected-(SIPE-VDD_3V3A12-PadN15)") (class "Default")
      (node (ref "SIP") (pin "N15") (pinfunction "VDD_3V3A12_N15") (pintype "bidirectional"))
    )
    (net (code "389") (name "unconnected-(SIPE-VDD_3V3A13-PadP5)") (class "Default")
      (node (ref "SIP") (pin "P5") (pinfunction "VDD_3V3A13_P5") (pintype "bidirectional"))
    )
    (net (code "390") (name "unconnected-(SIPE-VDD_3V3A14-PadP6)") (class "Default")
      (node (ref "SIP") (pin "P6") (pinfunction "VDD_3V3A14_P6") (pintype "bidirectional"))
    )
    (net (code "391") (name "unconnected-(SIPE-VDD_3V3A15-PadP7)") (class "Default")
      (node (ref "SIP") (pin "P7") (pinfunction "VDD_3V3A15_P7") (pintype "bidirectional"))
    )
    (net (code "392") (name "unconnected-(SIPE-VDD_3V3A16-PadP8)") (class "Default")
      (node (ref "SIP") (pin "P8") (pinfunction "VDD_3V3A16_P8") (pintype "bidirectional"))
    )
    (net (code "393") (name "unconnected-(SIPE-VDD_3V3A17-PadP10)") (class "Default")
      (node (ref "SIP") (pin "P10") (pinfunction "VDD_3V3A17_P10") (pintype "bidirectional"))
    )
    (net (code "394") (name "unconnected-(SIPE-VDD_3V3A18-PadP11)") (class "Default")
      (node (ref "SIP") (pin "P11") (pinfunction "VDD_3V3A18_P11") (pintype "bidirectional"))
    )
    (net (code "395") (name "unconnected-(SIPE-VDD_3V3A19-PadP12)") (class "Default")
      (node (ref "SIP") (pin "P12") (pinfunction "VDD_3V3A19_P12") (pintype "bidirectional"))
    )
    (net (code "396") (name "unconnected-(SIPE-VDD_3V3A20-PadP13)") (class "Default")
      (node (ref "SIP") (pin "P13") (pinfunction "VDD_3V3A20_P13") (pintype "bidirectional"))
    )
    (net (code "397") (name "unconnected-(SIPE-VDD_3V3A21-PadR15)") (class "Default")
      (node (ref "SIP") (pin "R15") (pinfunction "VDD_3V3A21_R15") (pintype "bidirectional"))
    )
    (net (code "398") (name "unconnected-(SIPE-VDD_CORE1-PadF6)") (class "Default")
      (node (ref "SIP") (pin "F6") (pinfunction "VDD_CORE1_F6") (pintype "bidirectional"))
    )
    (net (code "399") (name "unconnected-(SIPE-VDD_CORE2-PadF7)") (class "Default")
      (node (ref "SIP") (pin "F7") (pinfunction "VDD_CORE2_F7") (pintype "bidirectional"))
    )
    (net (code "400") (name "unconnected-(SIPE-VDD_CORE3-PadG6)") (class "Default")
      (node (ref "SIP") (pin "G6") (pinfunction "VDD_CORE3_G6") (pintype "bidirectional"))
    )
    (net (code "401") (name "unconnected-(SIPE-VDD_CORE4-PadG7)") (class "Default")
      (node (ref "SIP") (pin "G7") (pinfunction "VDD_CORE4_G7") (pintype "bidirectional"))
    )
    (net (code "402") (name "unconnected-(SIPE-VDD_CORE5-PadG10)") (class "Default")
      (node (ref "SIP") (pin "G10") (pinfunction "VDD_CORE5_G10") (pintype "bidirectional"))
    )
    (net (code "403") (name "unconnected-(SIPE-VDD_CORE6-PadH11)") (class "Default")
      (node (ref "SIP") (pin "H11") (pinfunction "VDD_CORE6_H11") (pintype "bidirectional"))
    )
    (net (code "404") (name "unconnected-(SIPE-VDD_CORE7-PadJ12)") (class "Default")
      (node (ref "SIP") (pin "J12") (pinfunction "VDD_CORE7_J12") (pintype "bidirectional"))
    )
    (net (code "405") (name "unconnected-(SIPE-VDD_CORE8-PadK6)") (class "Default")
      (node (ref "SIP") (pin "K6") (pinfunction "VDD_CORE8_K6") (pintype "bidirectional"))
    )
    (net (code "406") (name "unconnected-(SIPE-VDD_CORE9-PadK8)") (class "Default")
      (node (ref "SIP") (pin "K8") (pinfunction "VDD_CORE9_K8") (pintype "bidirectional"))
    )
    (net (code "407") (name "unconnected-(SIPE-VDD_CORE10-PadK12)") (class "Default")
      (node (ref "SIP") (pin "K12") (pinfunction "VDD_CORE10_K12") (pintype "bidirectional"))
    )
    (net (code "408") (name "unconnected-(SIPE-VDD_CORE11-PadL6)") (class "Default")
      (node (ref "SIP") (pin "L6") (pinfunction "VDD_CORE11_L6") (pintype "bidirectional"))
    )
    (net (code "409") (name "unconnected-(SIPE-VDD_CORE12-PadL7)") (class "Default")
      (node (ref "SIP") (pin "L7") (pinfunction "VDD_CORE12_L7") (pintype "bidirectional"))
    )
    (net (code "410") (name "unconnected-(SIPE-VDD_CORE13-PadL8)") (class "Default")
      (node (ref "SIP") (pin "L8") (pinfunction "VDD_CORE13_L8") (pintype "bidirectional"))
    )
    (net (code "411") (name "unconnected-(SIPE-VDD_CORE14-PadL9)") (class "Default")
      (node (ref "SIP") (pin "L9") (pinfunction "VDD_CORE14_L9") (pintype "bidirectional"))
    )
    (net (code "412") (name "unconnected-(SIPE-VDD_CORE15-PadM11)") (class "Default")
      (node (ref "SIP") (pin "M11") (pinfunction "VDD_CORE15_M11") (pintype "bidirectional"))
    )
    (net (code "413") (name "unconnected-(SIPE-VDD_CORE16-PadM13)") (class "Default")
      (node (ref "SIP") (pin "M13") (pinfunction "VDD_CORE16_M13") (pintype "bidirectional"))
    )
    (net (code "414") (name "unconnected-(SIPE-VDD_CORE17-PadN8)") (class "Default")
      (node (ref "SIP") (pin "N8") (pinfunction "VDD_CORE17_N8") (pintype "bidirectional"))
    )
    (net (code "415") (name "unconnected-(SIPE-VDD_CORE18-PadN9)") (class "Default")
      (node (ref "SIP") (pin "N9") (pinfunction "VDD_CORE18_N9") (pintype "bidirectional"))
    )
    (net (code "416") (name "unconnected-(SIPE-VDD_CORE19-PadN12)") (class "Default")
      (node (ref "SIP") (pin "N12") (pinfunction "VDD_CORE19_N12") (pintype "bidirectional"))
    )
    (net (code "417") (name "unconnected-(SIPE-VDD_CORE20-PadN13)") (class "Default")
      (node (ref "SIP") (pin "N13") (pinfunction "VDD_CORE20_N13") (pintype "bidirectional"))
    )
    (net (code "418") (name "unconnected-(SIPE-VDD_MPU0-PadF10)") (class "Default")
      (node (ref "SIP") (pin "F10") (pinfunction "VDD_MPU0_F10") (pintype "bidirectional"))
    )
    (net (code "419") (name "unconnected-(SIPE-VDD_MPU1-PadF11)") (class "Default")
      (node (ref "SIP") (pin "F11") (pinfunction "VDD_MPU1_F11") (pintype "bidirectional"))
    )
    (net (code "420") (name "unconnected-(SIPE-VDD_MPU2-PadF12)") (class "Default")
      (node (ref "SIP") (pin "F12") (pinfunction "VDD_MPU2_F12") (pintype "bidirectional"))
    )
    (net (code "421") (name "unconnected-(SIPE-VDD_MPU3-PadF13)") (class "Default")
      (node (ref "SIP") (pin "F13") (pinfunction "VDD_MPU3_F13") (pintype "bidirectional"))
    )
    (net (code "422") (name "unconnected-(SIPE-VDD_MPU4-PadG13)") (class "Default")
      (node (ref "SIP") (pin "G13") (pinfunction "VDD_MPU4_G13") (pintype "bidirectional"))
    )
    (net (code "423") (name "unconnected-(SIPE-VDD_MPU5-PadH13)") (class "Default")
      (node (ref "SIP") (pin "H13") (pinfunction "VDD_MPU5_H13") (pintype "bidirectional"))
    )
    (net (code "424") (name "unconnected-(SIPE-VDD_MPU6-PadJ13)") (class "Default")
      (node (ref "SIP") (pin "J13") (pinfunction "VDD_MPU6_J13") (pintype "bidirectional"))
    )
    (net (code "425") (name "unconnected-(SIPE-VDD_MPU_MON-PadA2)") (class "Default")
      (node (ref "SIP") (pin "A2") (pinfunction "VDD_MPU_MON_A2") (pintype "bidirectional"))
    )
    (net (code "426") (name "unconnected-(SIPE-VDD_PLL1-PadE7)") (class "Default")
      (node (ref "SIP") (pin "E7") (pinfunction "VDD_PLL1_E7") (pintype "bidirectional"))
    )
    (net (code "427") (name "unconnected-(SIPE-VDD_PLL2-PadH15)") (class "Default")
      (node (ref "SIP") (pin "H15") (pinfunction "VDD_PLL2_H15") (pintype "bidirectional"))
    )
    (net (code "428") (name "unconnected-(SIPE-VDD_PLL3-PadR10)") (class "Default")
      (node (ref "SIP") (pin "R10") (pinfunction "VDD_PLL3_R10") (pintype "bidirectional"))
    )
    (net (code "429") (name "unconnected-(SIPE-VDD_PLL4-PadR11)") (class "Default")
      (node (ref "SIP") (pin "R11") (pinfunction "VDD_PLL4_R11") (pintype "bidirectional"))
    )
    (net (code "430") (name "unconnected-(SIPE-VDD_RTC1-PadD7)") (class "Default")
      (node (ref "SIP") (pin "D7") (pinfunction "VDD_RTC1_D7") (pintype "bidirectional"))
    )
    (net (code "431") (name "unconnected-(SIPE-VDD_RTC2-PadE6)") (class "Default")
      (node (ref "SIP") (pin "E6") (pinfunction "VDD_RTC2_E6") (pintype "bidirectional"))
    )
    (net (code "432") (name "unconnected-(SIPE-VDD_RTC4-PadF9)") (class "Default")
      (node (ref "SIP") (pin "F9") (pinfunction "VDD_RTC4_F9") (pintype "bidirectional"))
    )
    (net (code "433") (name "unconnected-(SIPE-VDD_RTC5-PadK13)") (class "Default")
      (node (ref "SIP") (pin "K13") (pinfunction "VDD_RTC5_K13") (pintype "bidirectional"))
    )
    (net (code "434") (name "unconnected-(SIPE-VDD_RTC6-PadN6)") (class "Default")
      (node (ref "SIP") (pin "N6") (pinfunction "VDD_RTC6_N6") (pintype "bidirectional"))
    )
    (net (code "435") (name "unconnected-(SIPE-VDD_RTC7-PadP9)") (class "Default")
      (node (ref "SIP") (pin "P9") (pinfunction "VDD_RTC7_P9") (pintype "bidirectional"))
    )
    (net (code "436") (name "unconnected-(SIPE-VDD_RTC8-PadP14)") (class "Default")
      (node (ref "SIP") (pin "P14") (pinfunction "VDD_RTC8_P14") (pintype "bidirectional"))
    )
    (net (code "437") (name "unconnected-(SIPE-VPP-PadM5)") (class "Default")
      (node (ref "SIP") (pin "M5") (pinfunction "VPP_M5") (pintype "bidirectional"))
    )
    (net (code "438") (name "unconnected-(U3-NC-Pad5)") (class "Default")
      (node (ref "U3") (pin "5") (pinfunction "NC_5") (pintype "bidirectional"))
    )
    (net (code "439") (name "unconnected-(U4-ID-Pad3)") (class "Default")
      (node (ref "U4") (pin "3") (pinfunction "ID_3") (pintype "bidirectional"))
    )
    (net (code "440") (name "unconnected-(U4-NC-Pad5)") (class "Default")
      (node (ref "U4") (pin "5") (pinfunction "NC_5") (pintype "bidirectional"))
    )
    (net (code "441") (name "unconnected-(U6-NC-Pad1)") (class "Default")
      (node (ref "U6") (pin "1") (pinfunction "NC_1") (pintype "passive"))
    )
    (net (code "442") (name "unconnected-(U7-BT_UART_DBG-Pad43)") (class "Default")
      (node (ref "U7") (pin "43") (pinfunction "BT_UART_DBG_43") (pintype "bidirectional"))
    )
    (net (code "443") (name "unconnected-(U7-GPIO1-Pad27)") (class "Default")
      (node (ref "U7") (pin "27") (pinfunction "GPIO1_27") (pintype "bidirectional"))
    )
    (net (code "444") (name "unconnected-(U7-GPIO2-Pad26)") (class "Default")
      (node (ref "U7") (pin "26") (pinfunction "GPIO2_26") (pintype "bidirectional"))
    )
    (net (code "445") (name "unconnected-(U7-GPIO4-Pad25)") (class "Default")
      (node (ref "U7") (pin "25") (pinfunction "GPIO4_25") (pintype "bidirectional"))
    )
    (net (code "446") (name "unconnected-(U7-GPIO9-Pad3)") (class "Default")
      (node (ref "U7") (pin "3") (pinfunction "GPIO9_3") (pintype "bidirectional"))
    )
    (net (code "447") (name "unconnected-(U7-GPIO10-Pad4)") (class "Default")
      (node (ref "U7") (pin "4") (pinfunction "GPIO10_4") (pintype "bidirectional"))
    )
    (net (code "448") (name "unconnected-(U7-GPIO11-Pad2)") (class "Default")
      (node (ref "U7") (pin "2") (pinfunction "GPIO11_2") (pintype "bidirectional"))
    )
    (net (code "449") (name "unconnected-(U7-GPIO12-Pad5)") (class "Default")
      (node (ref "U7") (pin "5") (pinfunction "GPIO12_5") (pintype "bidirectional"))
    )
    (net (code "450") (name "unconnected-(U7-RESERVED1-Pad21)") (class "Default")
      (node (ref "U7") (pin "21") (pinfunction "RESERVED1_21") (pintype "bidirectional"))
    )
    (net (code "451") (name "unconnected-(U7-RESERVED2-Pad22)") (class "Default")
      (node (ref "U7") (pin "22") (pinfunction "RESERVED2_22") (pintype "bidirectional"))
    )
    (net (code "452") (name "unconnected-(U7-RESERVED3-Pad62)") (class "Default")
      (node (ref "U7") (pin "62") (pinfunction "RESERVED3_62") (pintype "bidirectional"))
    )
    (net (code "453") (name "unconnected-(U7-WL_UART_DBG-Pad42)") (class "Default")
      (node (ref "U7") (pin "42") (pinfunction "WL_UART_DBG_42") (pintype "bidirectional"))
    )
  )
)
